# Main.net
KiCad netlist of a schematic drawn in EAGLE
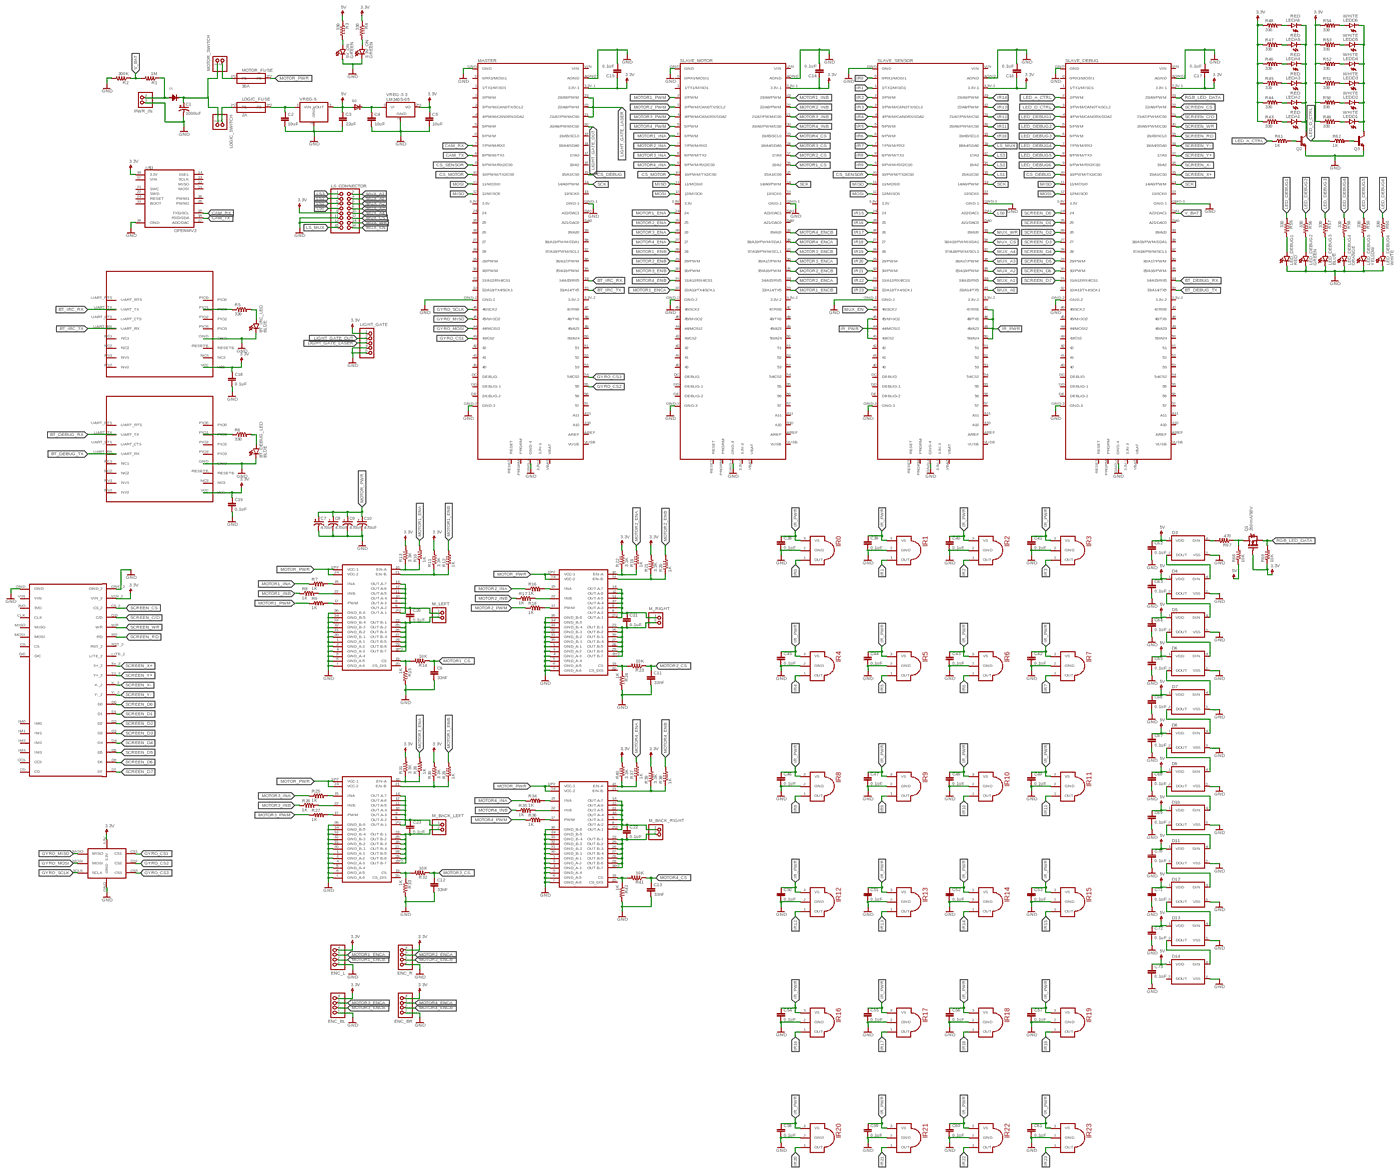
[diagram p0: schematic, sheet 1, overview]
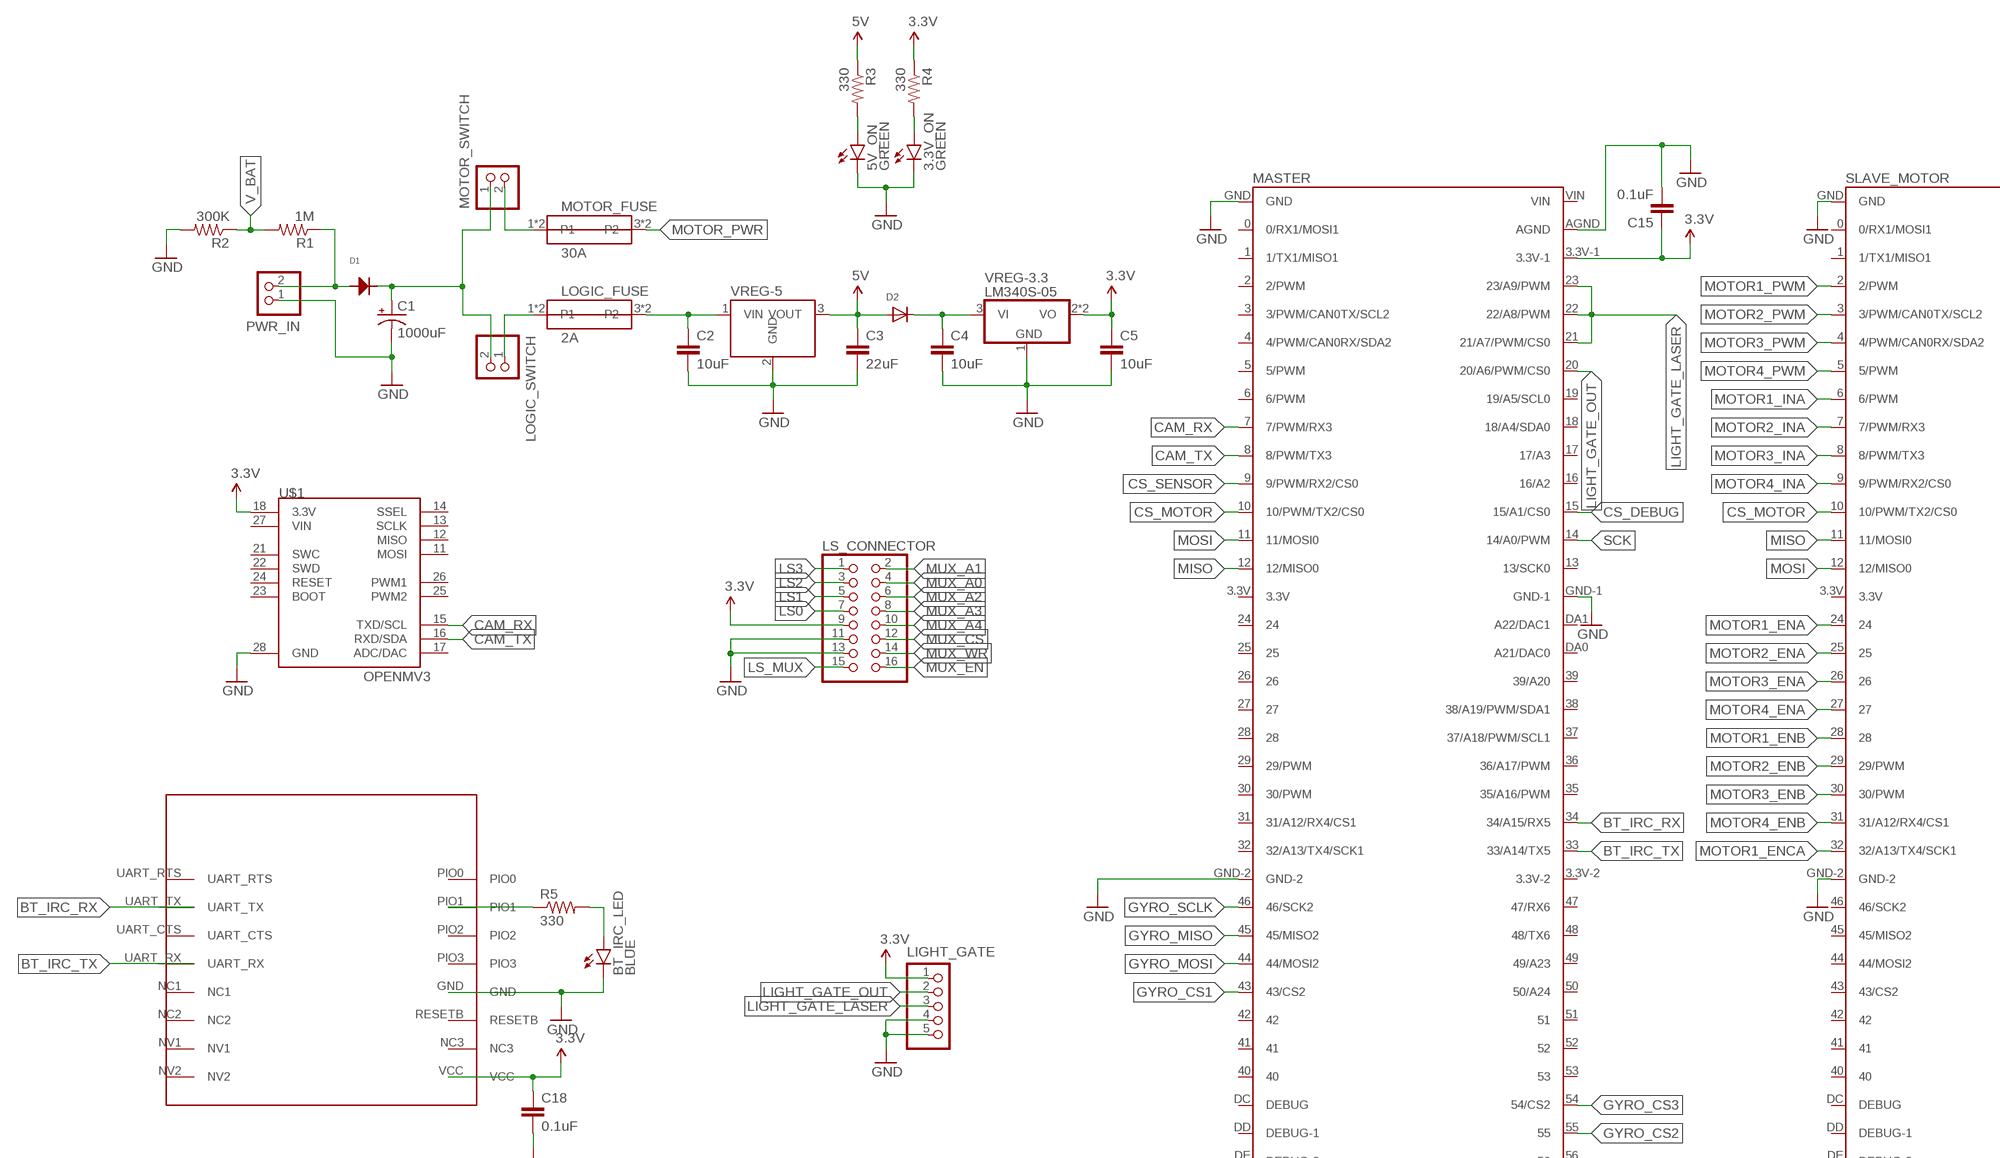
[diagram p1: schematic, sheet 1, part 1 of 4]
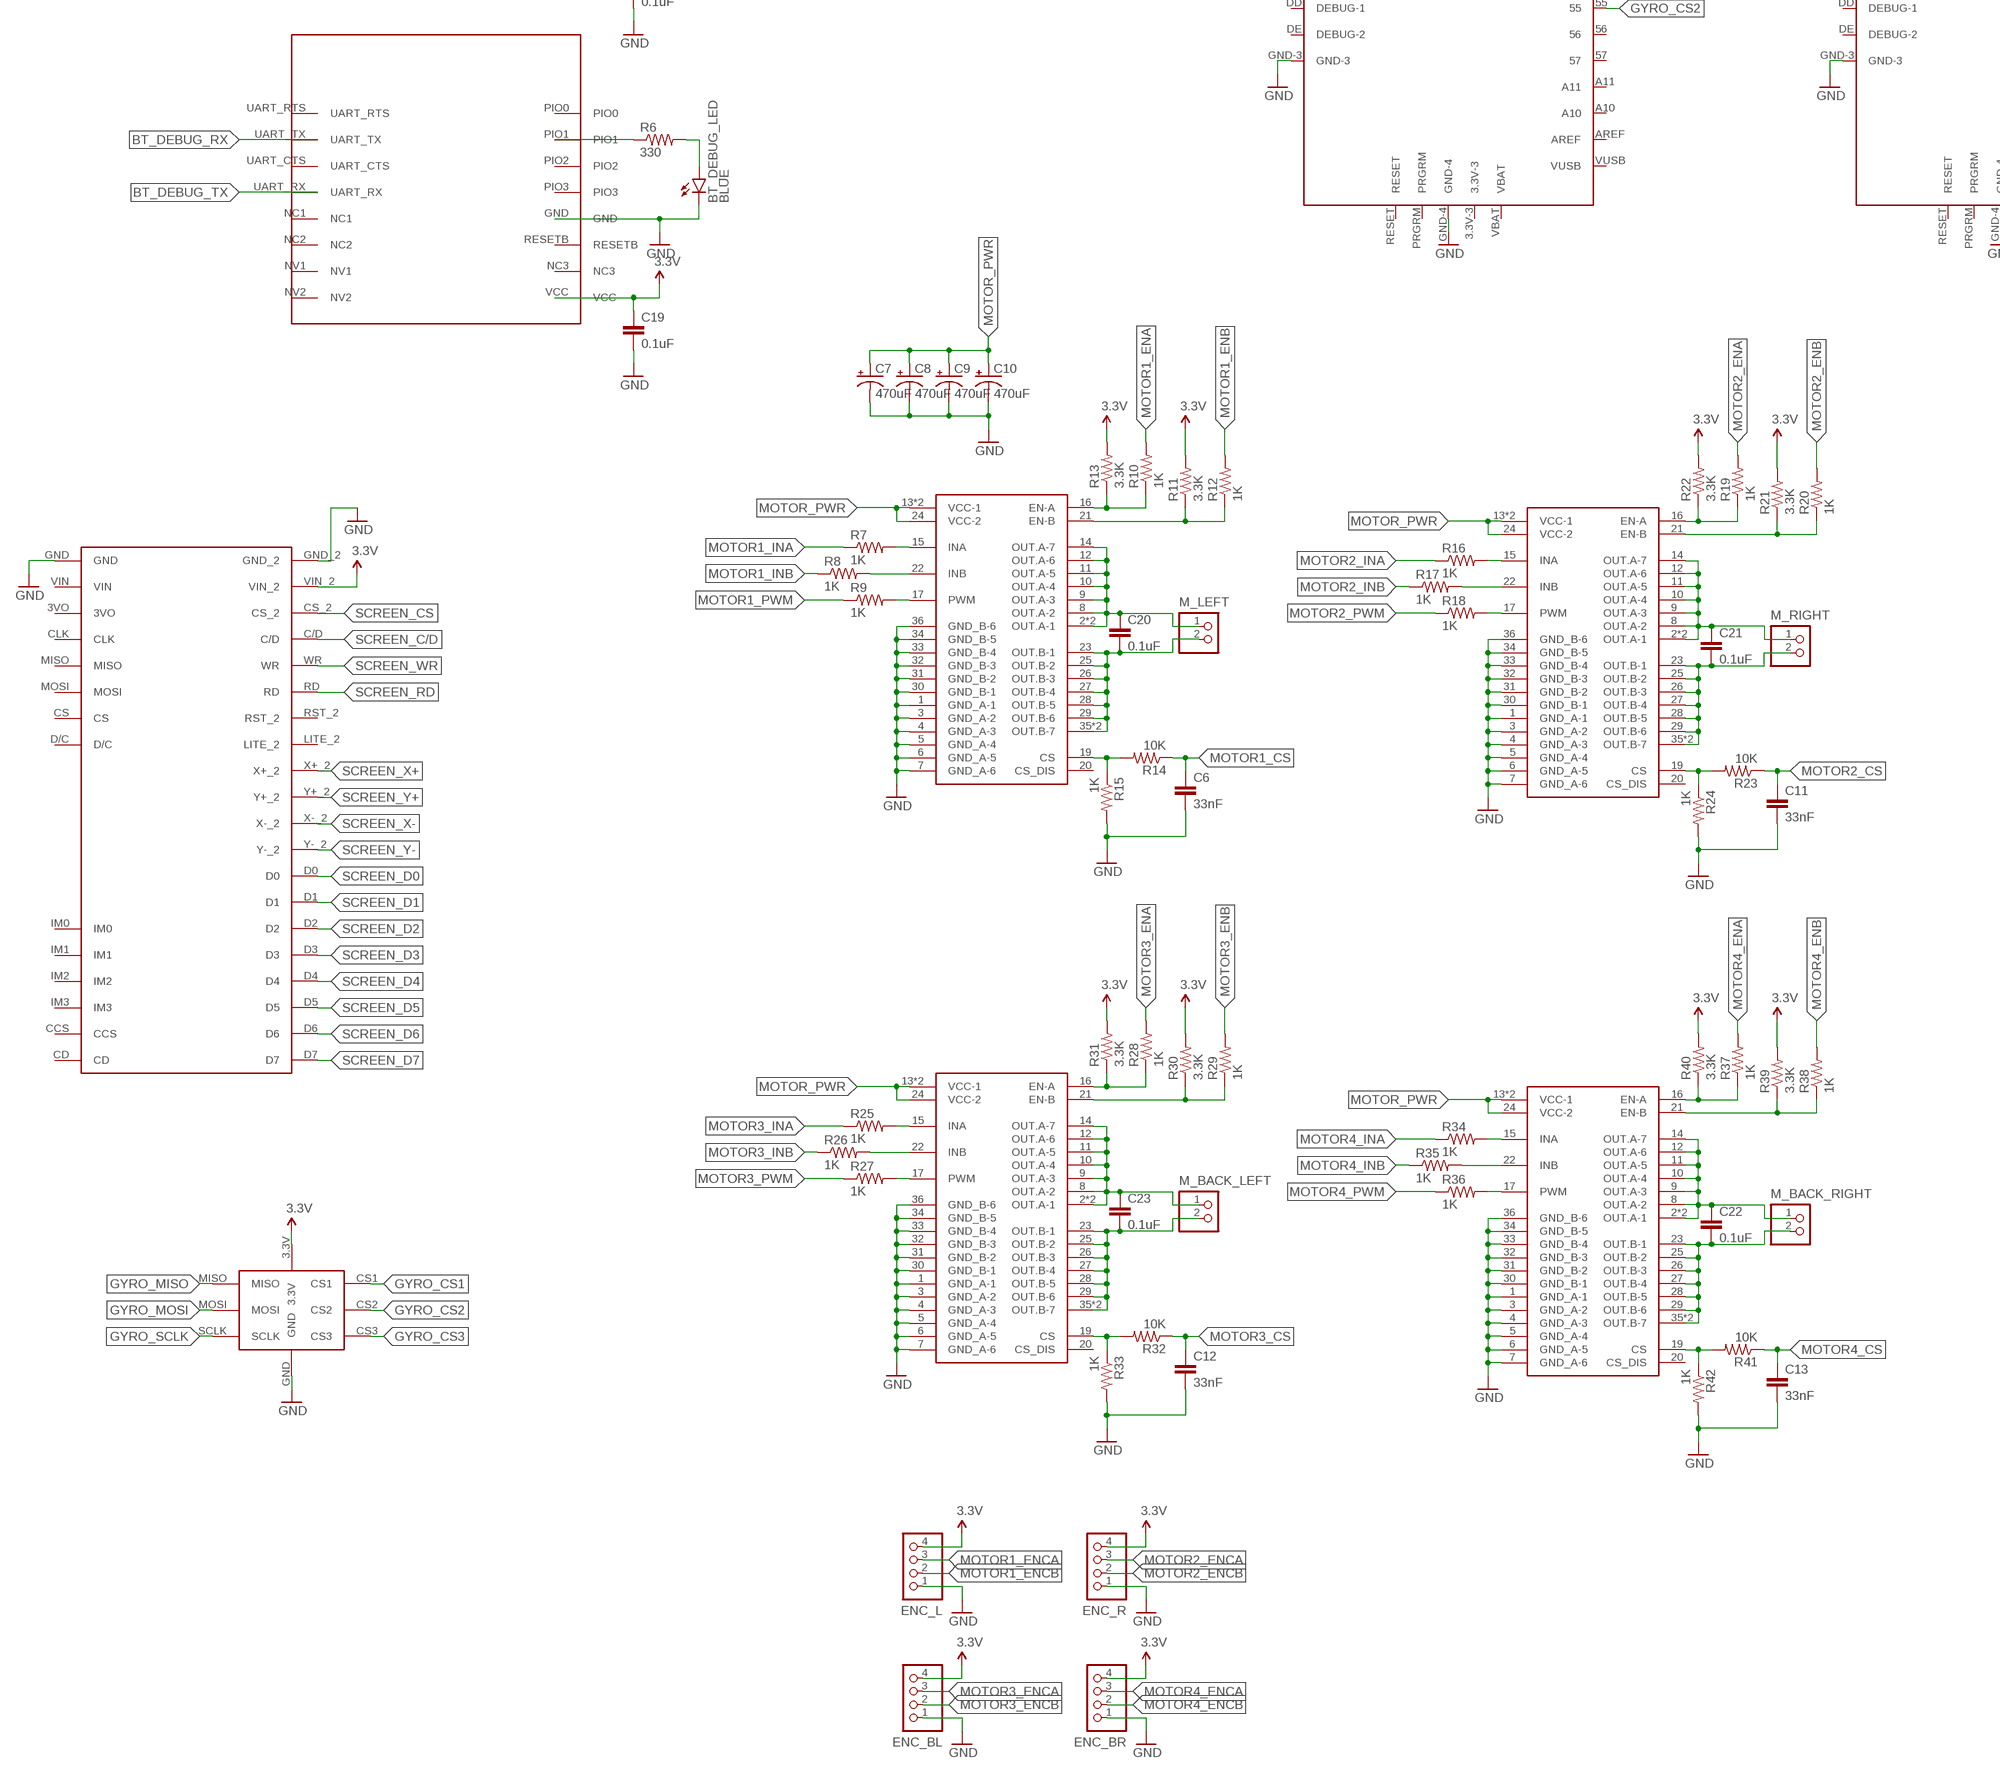
[diagram p2: schematic, sheet 1, part 2 of 4]
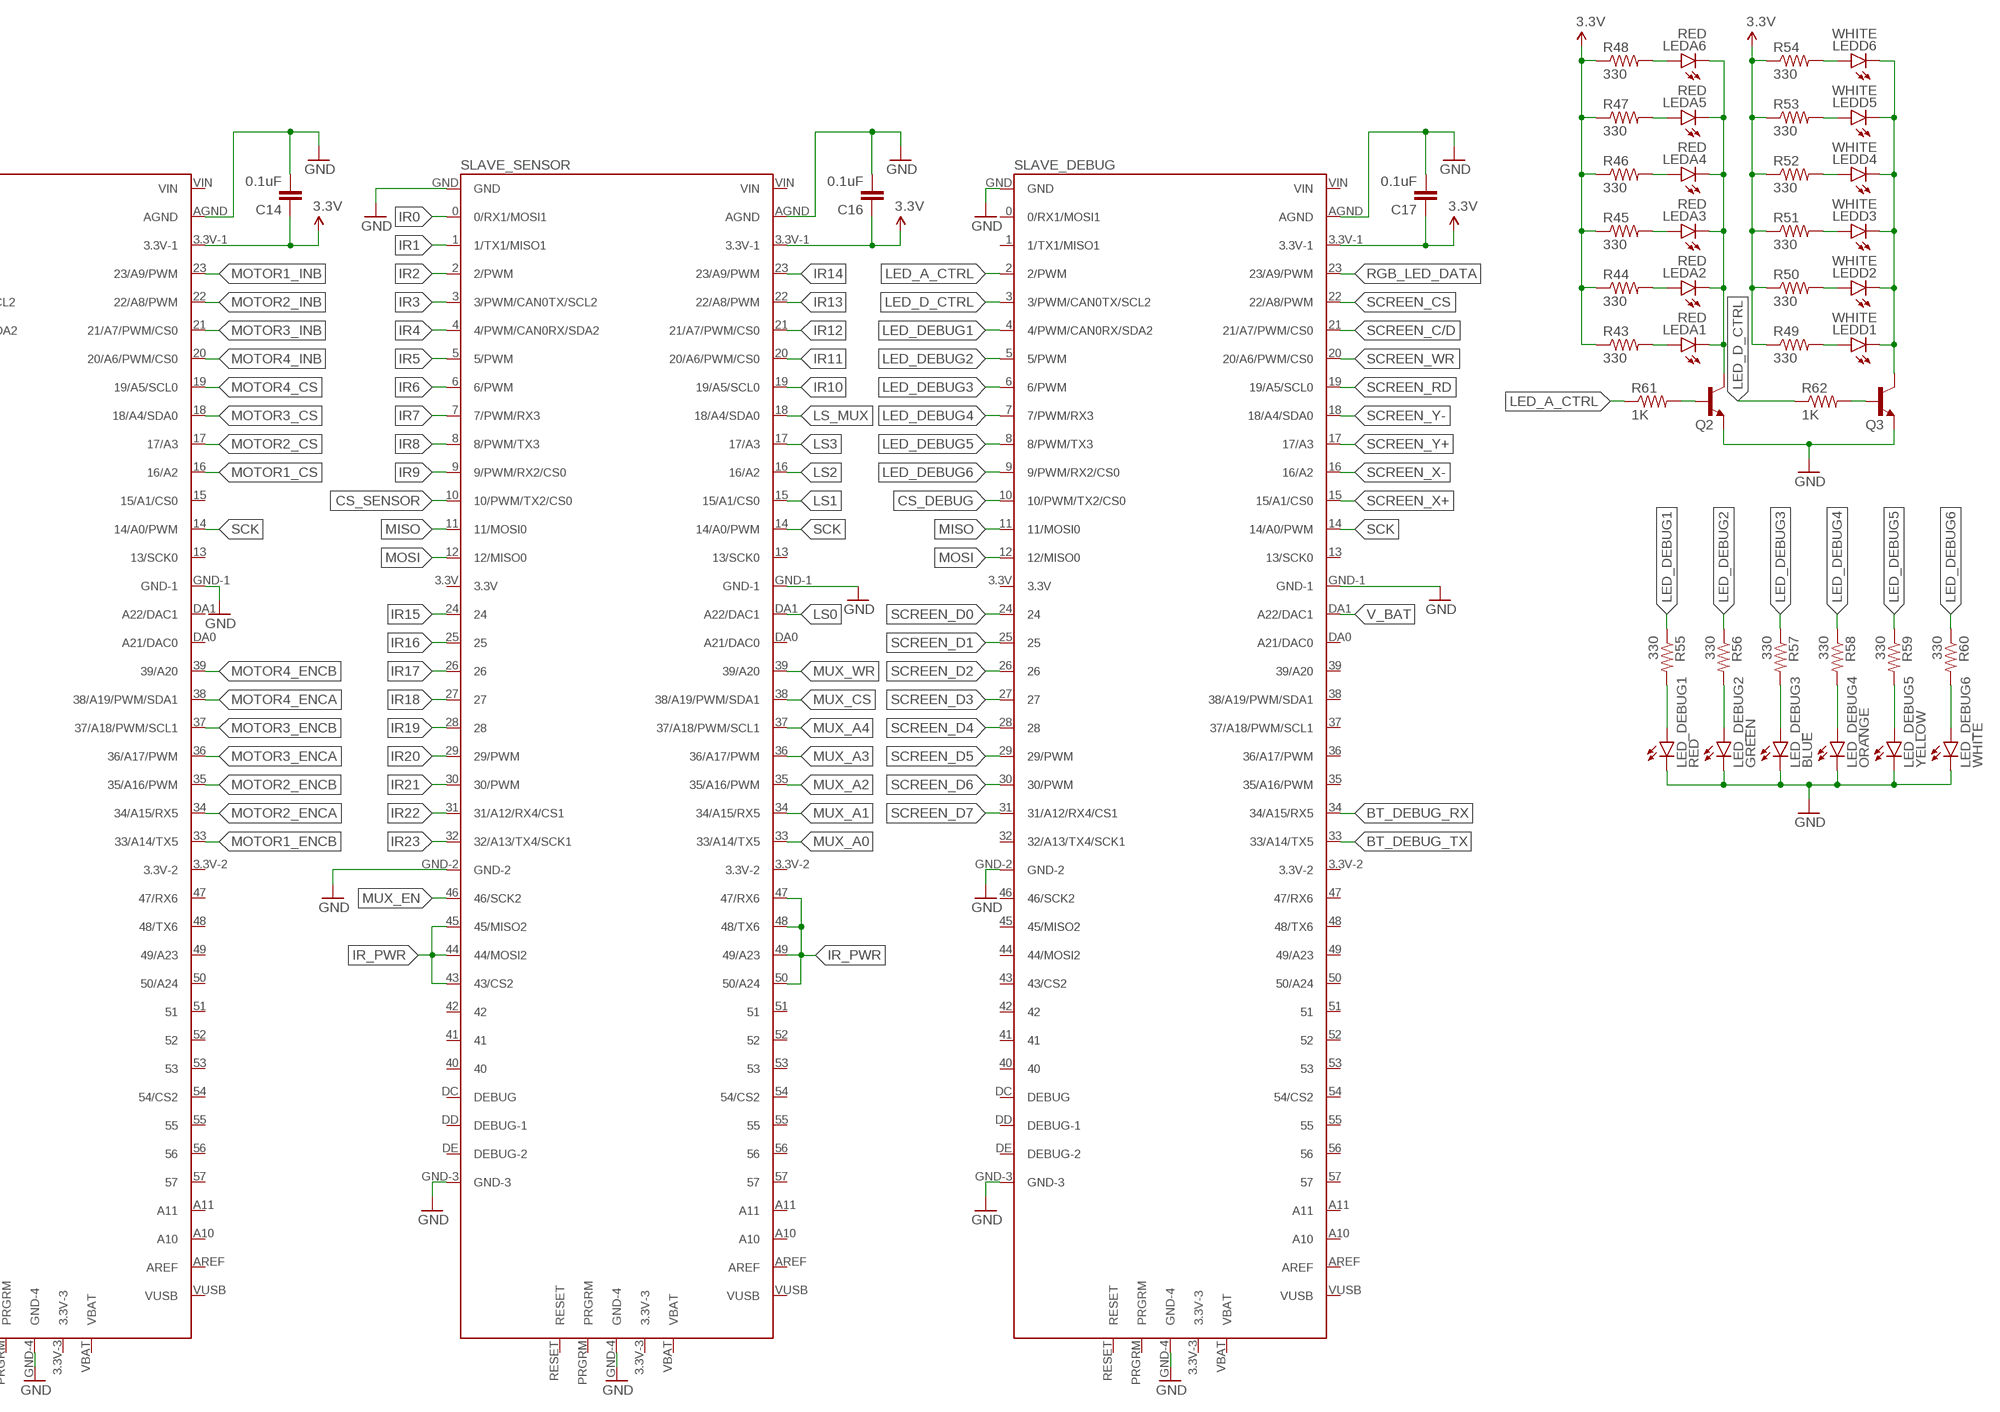
[diagram p3: schematic, sheet 1, part 3 of 4]
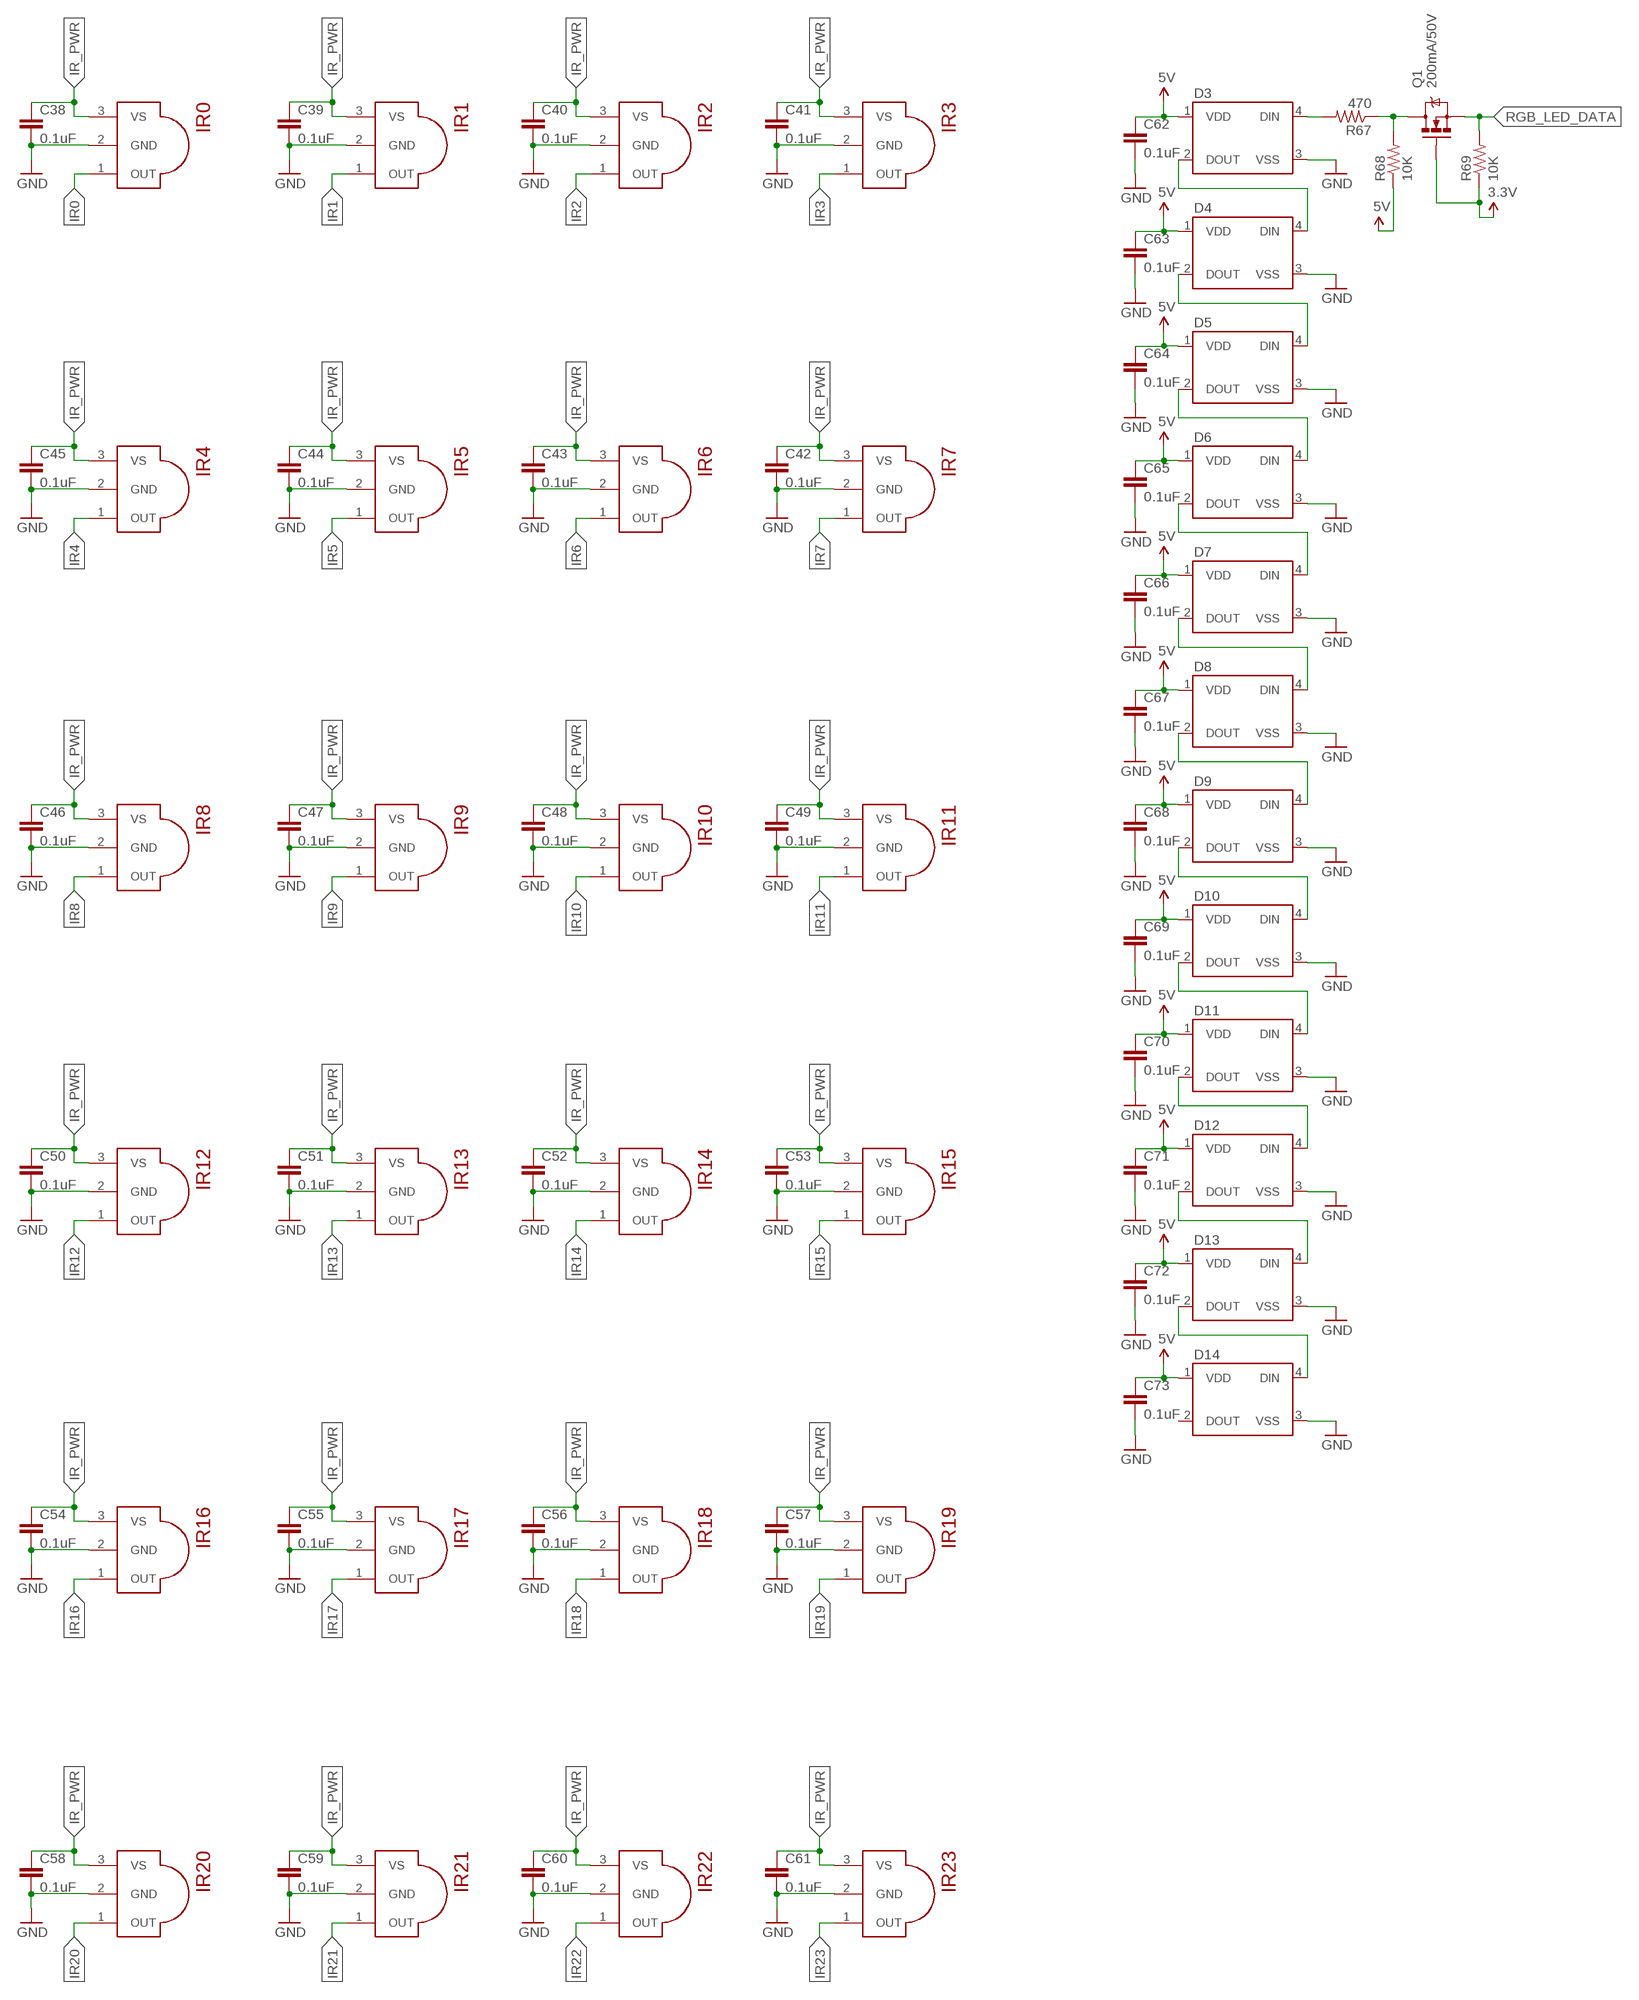
[diagram p4: schematic, sheet 1, part 4 of 4]

(export (version "E")
  (design (tool "Eeschema 10.0.6"))
  (components
    (comp (ref "3.3V_ON")
      (value "GREEN")
      (footprint "eagle-import:LED-0603")
      (libsource (lib "eagle-import") (part "LED0603"))
    )
    (comp (ref "5V_ON")
      (value "GREEN")
      (footprint "eagle-import:LED-0603")
      (libsource (lib "eagle-import") (part "LED0603"))
    )
    (comp (ref "BT_DEBUG")
      (value "HM-11")
      (footprint "eagle-import:HM-11")
      (libsource (lib "eagle-import") (part "HM-11"))
    )
    (comp (ref "BT_DEBUG_LED")
      (value "BLUE")
      (footprint "eagle-import:LED-0603")
      (libsource (lib "eagle-import") (part "LED0603"))
    )
    (comp (ref "BT_IRC")
      (value "HM-11")
      (footprint "eagle-import:HM-11")
      (libsource (lib "eagle-import") (part "HM-11"))
    )
    (comp (ref "BT_IRC_LED")
      (value "BLUE")
      (footprint "eagle-import:LED-0603")
      (libsource (lib "eagle-import") (part "LED0603"))
    )
    (comp (ref "C1")
      (value "1000uF")
      (footprint "eagle-import:CPOL-RADIAL-1000UF-25V")
      (libsource (lib "eagle-import") (part "1000UF-25V(PTH)"))
    )
    (comp (ref "C2")
      (value "10uF")
      (footprint "eagle-import:0805")
      (libsource (lib "eagle-import") (part "CAP0805"))
    )
    (comp (ref "C3")
      (value "22uF")
      (footprint "eagle-import:1206")
      (libsource (lib "eagle-import") (part "CAP1206"))
    )
    (comp (ref "C4")
      (value "10uF")
      (footprint "eagle-import:0805")
      (libsource (lib "eagle-import") (part "CAP0805"))
    )
    (comp (ref "C5")
      (value "10uF")
      (footprint "eagle-import:0805")
      (libsource (lib "eagle-import") (part "CAP0805"))
    )
    (comp (ref "C6")
      (value "33nF")
      (footprint "eagle-import:0603-CAP")
      (libsource (lib "eagle-import") (part "CAP0603-CAP"))
    )
    (comp (ref "C7")
      (value "470uF")
      (footprint "eagle-import:E3,5-8")
      (libsource (lib "eagle-import") (part "CPOL-USE3.5-8"))
    )
    (comp (ref "C8")
      (value "470uF")
      (footprint "eagle-import:E3,5-8")
      (libsource (lib "eagle-import") (part "CPOL-USE3.5-8"))
    )
    (comp (ref "C9")
      (value "470uF")
      (footprint "eagle-import:E3,5-8")
      (libsource (lib "eagle-import") (part "CPOL-USE3.5-8"))
    )
    (comp (ref "C10")
      (value "470uF")
      (footprint "eagle-import:E3,5-8")
      (libsource (lib "eagle-import") (part "CPOL-USE3.5-8"))
    )
    (comp (ref "C11")
      (value "33nF")
      (footprint "eagle-import:0603-CAP")
      (libsource (lib "eagle-import") (part "CAP0603-CAP"))
    )
    (comp (ref "C12")
      (value "33nF")
      (footprint "eagle-import:0603-CAP")
      (libsource (lib "eagle-import") (part "CAP0603-CAP"))
    )
    (comp (ref "C13")
      (value "33nF")
      (footprint "eagle-import:0603-CAP")
      (libsource (lib "eagle-import") (part "CAP0603-CAP"))
    )
    (comp (ref "C14")
      (value "0.1uF")
      (footprint "eagle-import:0603-CAP")
      (libsource (lib "eagle-import") (part "CAP0603-CAP"))
    )
    (comp (ref "C15")
      (value "0.1uF")
      (footprint "eagle-import:0603-CAP")
      (libsource (lib "eagle-import") (part "CAP0603-CAP"))
    )
    (comp (ref "C16")
      (value "0.1uF")
      (footprint "eagle-import:0603-CAP")
      (libsource (lib "eagle-import") (part "CAP0603-CAP"))
    )
    (comp (ref "C17")
      (value "0.1uF")
      (footprint "eagle-import:0603-CAP")
      (libsource (lib "eagle-import") (part "CAP0603-CAP"))
    )
    (comp (ref "C18")
      (value "0.1uF")
      (footprint "eagle-import:0603-CAP")
      (libsource (lib "eagle-import") (part "CAP0603-CAP"))
    )
    (comp (ref "C19")
      (value "0.1uF")
      (footprint "eagle-import:0603-CAP")
      (libsource (lib "eagle-import") (part "CAP0603-CAP"))
    )
    (comp (ref "C20")
      (value "0.1uF")
      (footprint "eagle-import:0603-CAP")
      (libsource (lib "eagle-import") (part "CAP0603-CAP"))
    )
    (comp (ref "C21")
      (value "0.1uF")
      (footprint "eagle-import:0603-CAP")
      (libsource (lib "eagle-import") (part "CAP0603-CAP"))
    )
    (comp (ref "C22")
      (value "0.1uF")
      (footprint "eagle-import:0603-CAP")
      (libsource (lib "eagle-import") (part "CAP0603-CAP"))
    )
    (comp (ref "C23")
      (value "0.1uF")
      (footprint "eagle-import:0603-CAP")
      (libsource (lib "eagle-import") (part "CAP0603-CAP"))
    )
    (comp (ref "C38")
      (value "0.1uF")
      (footprint "eagle-import:0603-CAP")
      (libsource (lib "eagle-import") (part "CAP0603-CAP"))
    )
    (comp (ref "C39")
      (value "0.1uF")
      (footprint "eagle-import:0603-CAP")
      (libsource (lib "eagle-import") (part "CAP0603-CAP"))
    )
    (comp (ref "C40")
      (value "0.1uF")
      (footprint "eagle-import:0603-CAP")
      (libsource (lib "eagle-import") (part "CAP0603-CAP"))
    )
    (comp (ref "C41")
      (value "0.1uF")
      (footprint "eagle-import:0603-CAP")
      (libsource (lib "eagle-import") (part "CAP0603-CAP"))
    )
    (comp (ref "C42")
      (value "0.1uF")
      (footprint "eagle-import:0603-CAP")
      (libsource (lib "eagle-import") (part "CAP0603-CAP"))
    )
    (comp (ref "C43")
      (value "0.1uF")
      (footprint "eagle-import:0603-CAP")
      (libsource (lib "eagle-import") (part "CAP0603-CAP"))
    )
    (comp (ref "C44")
      (value "0.1uF")
      (footprint "eagle-import:0603-CAP")
      (libsource (lib "eagle-import") (part "CAP0603-CAP"))
    )
    (comp (ref "C45")
      (value "0.1uF")
      (footprint "eagle-import:0603-CAP")
      (libsource (lib "eagle-import") (part "CAP0603-CAP"))
    )
    (comp (ref "C46")
      (value "0.1uF")
      (footprint "eagle-import:0603-CAP")
      (libsource (lib "eagle-import") (part "CAP0603-CAP"))
    )
    (comp (ref "C47")
      (value "0.1uF")
      (footprint "eagle-import:0603-CAP")
      (libsource (lib "eagle-import") (part "CAP0603-CAP"))
    )
    (comp (ref "C48")
      (value "0.1uF")
      (footprint "eagle-import:0603-CAP")
      (libsource (lib "eagle-import") (part "CAP0603-CAP"))
    )
    (comp (ref "C49")
      (value "0.1uF")
      (footprint "eagle-import:0603-CAP")
      (libsource (lib "eagle-import") (part "CAP0603-CAP"))
    )
    (comp (ref "C50")
      (value "0.1uF")
      (footprint "eagle-import:0603-CAP")
      (libsource (lib "eagle-import") (part "CAP0603-CAP"))
    )
    (comp (ref "C51")
      (value "0.1uF")
      (footprint "eagle-import:0603-CAP")
      (libsource (lib "eagle-import") (part "CAP0603-CAP"))
    )
    (comp (ref "C52")
      (value "0.1uF")
      (footprint "eagle-import:0603-CAP")
      (libsource (lib "eagle-import") (part "CAP0603-CAP"))
    )
    (comp (ref "C53")
      (value "0.1uF")
      (footprint "eagle-import:0603-CAP")
      (libsource (lib "eagle-import") (part "CAP0603-CAP"))
    )
    (comp (ref "C54")
      (value "0.1uF")
      (footprint "eagle-import:0603-CAP")
      (libsource (lib "eagle-import") (part "CAP0603-CAP"))
    )
    (comp (ref "C55")
      (value "0.1uF")
      (footprint "eagle-import:0603-CAP")
      (libsource (lib "eagle-import") (part "CAP0603-CAP"))
    )
    (comp (ref "C56")
      (value "0.1uF")
      (footprint "eagle-import:0603-CAP")
      (libsource (lib "eagle-import") (part "CAP0603-CAP"))
    )
    (comp (ref "C57")
      (value "0.1uF")
      (footprint "eagle-import:0603-CAP")
      (libsource (lib "eagle-import") (part "CAP0603-CAP"))
    )
    (comp (ref "C58")
      (value "0.1uF")
      (footprint "eagle-import:0603-CAP")
      (libsource (lib "eagle-import") (part "CAP0603-CAP"))
    )
    (comp (ref "C59")
      (value "0.1uF")
      (footprint "eagle-import:0603-CAP")
      (libsource (lib "eagle-import") (part "CAP0603-CAP"))
    )
    (comp (ref "C60")
      (value "0.1uF")
      (footprint "eagle-import:0603-CAP")
      (libsource (lib "eagle-import") (part "CAP0603-CAP"))
    )
    (comp (ref "C61")
      (value "0.1uF")
      (footprint "eagle-import:0603-CAP")
      (libsource (lib "eagle-import") (part "CAP0603-CAP"))
    )
    (comp (ref "C62")
      (value "0.1uF")
      (footprint "eagle-import:0603-CAP")
      (libsource (lib "eagle-import") (part "CAP0603-CAP"))
    )
    (comp (ref "C63")
      (value "0.1uF")
      (footprint "eagle-import:0603-CAP")
      (libsource (lib "eagle-import") (part "CAP0603-CAP"))
    )
    (comp (ref "C64")
      (value "0.1uF")
      (footprint "eagle-import:0603-CAP")
      (libsource (lib "eagle-import") (part "CAP0603-CAP"))
    )
    (comp (ref "C65")
      (value "0.1uF")
      (footprint "eagle-import:0603-CAP")
      (libsource (lib "eagle-import") (part "CAP0603-CAP"))
    )
    (comp (ref "C66")
      (value "0.1uF")
      (footprint "eagle-import:0603-CAP")
      (libsource (lib "eagle-import") (part "CAP0603-CAP"))
    )
    (comp (ref "C67")
      (value "0.1uF")
      (footprint "eagle-import:0603-CAP")
      (libsource (lib "eagle-import") (part "CAP0603-CAP"))
    )
    (comp (ref "C68")
      (value "0.1uF")
      (footprint "eagle-import:0603-CAP")
      (libsource (lib "eagle-import") (part "CAP0603-CAP"))
    )
    (comp (ref "C69")
      (value "0.1uF")
      (footprint "eagle-import:0603-CAP")
      (libsource (lib "eagle-import") (part "CAP0603-CAP"))
    )
    (comp (ref "C70")
      (value "0.1uF")
      (footprint "eagle-import:0603-CAP")
      (libsource (lib "eagle-import") (part "CAP0603-CAP"))
    )
    (comp (ref "C71")
      (value "0.1uF")
      (footprint "eagle-import:0603-CAP")
      (libsource (lib "eagle-import") (part "CAP0603-CAP"))
    )
    (comp (ref "C72")
      (value "0.1uF")
      (footprint "eagle-import:0603-CAP")
      (libsource (lib "eagle-import") (part "CAP0603-CAP"))
    )
    (comp (ref "C73")
      (value "0.1uF")
      (footprint "eagle-import:0603-CAP")
      (libsource (lib "eagle-import") (part "CAP0603-CAP"))
    )
    (comp (ref "D1")
      (value "DIODE_D2PAK(TO-263AB)")
      (footprint "eagle-import:D2PAK(TO-263AB)")
      (libsource (lib "eagle-import") (part "DIODE_D2PAK(TO-263AB)"))
    )
    (comp (ref "D2")
      (value "DIODE_SOD-123FL")
      (footprint "eagle-import:SOD-123FL")
      (libsource (lib "eagle-import") (part "DIODE_SOD-123FL"))
    )
    (comp (ref "D3")
      (value "WS2812B")
      (footprint "eagle-import:WS2812B")
      (libsource (lib "eagle-import") (part "WS2812B"))
    )
    (comp (ref "D4")
      (value "WS2812B")
      (footprint "eagle-import:WS2812B")
      (libsource (lib "eagle-import") (part "WS2812B"))
    )
    (comp (ref "D5")
      (value "WS2812B")
      (footprint "eagle-import:WS2812B")
      (libsource (lib "eagle-import") (part "WS2812B"))
    )
    (comp (ref "D6")
      (value "WS2812B")
      (footprint "eagle-import:WS2812B")
      (libsource (lib "eagle-import") (part "WS2812B"))
    )
    (comp (ref "D7")
      (value "WS2812B")
      (footprint "eagle-import:WS2812B")
      (libsource (lib "eagle-import") (part "WS2812B"))
    )
    (comp (ref "D8")
      (value "WS2812B")
      (footprint "eagle-import:WS2812B")
      (libsource (lib "eagle-import") (part "WS2812B"))
    )
    (comp (ref "D9")
      (value "WS2812B")
      (footprint "eagle-import:WS2812B")
      (libsource (lib "eagle-import") (part "WS2812B"))
    )
    (comp (ref "D10")
      (value "WS2812B")
      (footprint "eagle-import:WS2812B")
      (libsource (lib "eagle-import") (part "WS2812B"))
    )
    (comp (ref "D11")
      (value "WS2812B")
      (footprint "eagle-import:WS2812B")
      (libsource (lib "eagle-import") (part "WS2812B"))
    )
    (comp (ref "D12")
      (value "WS2812B")
      (footprint "eagle-import:WS2812B")
      (libsource (lib "eagle-import") (part "WS2812B"))
    )
    (comp (ref "D13")
      (value "WS2812B")
      (footprint "eagle-import:WS2812B")
      (libsource (lib "eagle-import") (part "WS2812B"))
    )
    (comp (ref "D14")
      (value "WS2812B")
      (footprint "eagle-import:WS2812B")
      (libsource (lib "eagle-import") (part "WS2812B"))
    )
    (comp (ref "ENC_BL")
      (value "B4B-PH-K-S")
      (footprint "eagle-import:B4B-PH-K-S")
      (libsource (lib "eagle-import") (part "B4B-PH-K-S"))
    )
    (comp (ref "ENC_BR")
      (value "B4B-PH-K-S")
      (footprint "eagle-import:B4B-PH-K-S")
      (libsource (lib "eagle-import") (part "B4B-PH-K-S"))
    )
    (comp (ref "ENC_L")
      (value "B4B-PH-K-S")
      (footprint "eagle-import:B4B-PH-K-S")
      (libsource (lib "eagle-import") (part "B4B-PH-K-S"))
    )
    (comp (ref "ENC_R")
      (value "B4B-PH-K-S")
      (footprint "eagle-import:B4B-PH-K-S")
      (libsource (lib "eagle-import") (part "B4B-PH-K-S"))
    )
    (comp (ref "IR0")
      (value "TSSP58038")
      (footprint "eagle-import:TSSP58038")
      (libsource (lib "eagle-import") (part "TSSP58038"))
    )
    (comp (ref "IR1")
      (value "TSSP58038")
      (footprint "eagle-import:TSSP58038")
      (libsource (lib "eagle-import") (part "TSSP58038"))
    )
    (comp (ref "IR2")
      (value "TSSP58038")
      (footprint "eagle-import:TSSP58038")
      (libsource (lib "eagle-import") (part "TSSP58038"))
    )
    (comp (ref "IR3")
      (value "TSSP58038")
      (footprint "eagle-import:TSSP58038")
      (libsource (lib "eagle-import") (part "TSSP58038"))
    )
    (comp (ref "IR4")
      (value "TSSP58038")
      (footprint "eagle-import:TSSP58038")
      (libsource (lib "eagle-import") (part "TSSP58038"))
    )
    (comp (ref "IR5")
      (value "TSSP58038")
      (footprint "eagle-import:TSSP58038")
      (libsource (lib "eagle-import") (part "TSSP58038"))
    )
    (comp (ref "IR6")
      (value "TSSP58038")
      (footprint "eagle-import:TSSP58038")
      (libsource (lib "eagle-import") (part "TSSP58038"))
    )
    (comp (ref "IR7")
      (value "TSSP58038")
      (footprint "eagle-import:TSSP58038")
      (libsource (lib "eagle-import") (part "TSSP58038"))
    )
    (comp (ref "IR8")
      (value "TSSP58038")
      (footprint "eagle-import:TSSP58038")
      (libsource (lib "eagle-import") (part "TSSP58038"))
    )
    (comp (ref "IR9")
      (value "TSSP58038")
      (footprint "eagle-import:TSSP58038")
      (libsource (lib "eagle-import") (part "TSSP58038"))
    )
    (comp (ref "IR10")
      (value "TSSP58038")
      (footprint "eagle-import:TSSP58038")
      (libsource (lib "eagle-import") (part "TSSP58038"))
    )
    (comp (ref "IR11")
      (value "TSSP58038")
      (footprint "eagle-import:TSSP58038")
      (libsource (lib "eagle-import") (part "TSSP58038"))
    )
    (comp (ref "IR12")
      (value "TSSP58038")
      (footprint "eagle-import:TSSP58038")
      (libsource (lib "eagle-import") (part "TSSP58038"))
    )
    (comp (ref "IR13")
      (value "TSSP58038")
      (footprint "eagle-import:TSSP58038")
      (libsource (lib "eagle-import") (part "TSSP58038"))
    )
    (comp (ref "IR14")
      (value "TSSP58038")
      (footprint "eagle-import:TSSP58038")
      (libsource (lib "eagle-import") (part "TSSP58038"))
    )
    (comp (ref "IR15")
      (value "TSSP58038")
      (footprint "eagle-import:TSSP58038")
      (libsource (lib "eagle-import") (part "TSSP58038"))
    )
    (comp (ref "IR16")
      (value "TSSP58038")
      (footprint "eagle-import:TSSP58038")
      (libsource (lib "eagle-import") (part "TSSP58038"))
    )
    (comp (ref "IR17")
      (value "TSSP58038")
      (footprint "eagle-import:TSSP58038")
      (libsource (lib "eagle-import") (part "TSSP58038"))
    )
    (comp (ref "IR18")
      (value "TSSP58038")
      (footprint "eagle-import:TSSP58038")
      (libsource (lib "eagle-import") (part "TSSP58038"))
    )
    (comp (ref "IR19")
      (value "TSSP58038")
      (footprint "eagle-import:TSSP58038")
      (libsource (lib "eagle-import") (part "TSSP58038"))
    )
    (comp (ref "IR20")
      (value "TSSP58038")
      (footprint "eagle-import:TSSP58038")
      (libsource (lib "eagle-import") (part "TSSP58038"))
    )
    (comp (ref "IR21")
      (value "TSSP58038")
      (footprint "eagle-import:TSSP58038")
      (libsource (lib "eagle-import") (part "TSSP58038"))
    )
    (comp (ref "IR22")
      (value "TSSP58038")
      (footprint "eagle-import:TSSP58038")
      (libsource (lib "eagle-import") (part "TSSP58038"))
    )
    (comp (ref "IR23")
      (value "TSSP58038")
      (footprint "eagle-import:TSSP58038")
      (libsource (lib "eagle-import") (part "TSSP58038"))
    )
    (comp (ref "LEDA1")
      (value "RED")
      (footprint "eagle-import:LED-0603")
      (libsource (lib "eagle-import") (part "LED0603"))
    )
    (comp (ref "LEDA2")
      (value "RED")
      (footprint "eagle-import:LED-0603")
      (libsource (lib "eagle-import") (part "LED0603"))
    )
    (comp (ref "LEDA3")
      (value "RED")
      (footprint "eagle-import:LED-0603")
      (libsource (lib "eagle-import") (part "LED0603"))
    )
    (comp (ref "LEDA4")
      (value "RED")
      (footprint "eagle-import:LED-0603")
      (libsource (lib "eagle-import") (part "LED0603"))
    )
    (comp (ref "LEDA5")
      (value "RED")
      (footprint "eagle-import:LED-0603")
      (libsource (lib "eagle-import") (part "LED0603"))
    )
    (comp (ref "LEDA6")
      (value "RED")
      (footprint "eagle-import:LED-0603")
      (libsource (lib "eagle-import") (part "LED0603"))
    )
    (comp (ref "LEDD1")
      (value "WHITE")
      (footprint "eagle-import:LED-0603")
      (libsource (lib "eagle-import") (part "LED0603"))
    )
    (comp (ref "LEDD2")
      (value "WHITE")
      (footprint "eagle-import:LED-0603")
      (libsource (lib "eagle-import") (part "LED0603"))
    )
    (comp (ref "LEDD3")
      (value "WHITE")
      (footprint "eagle-import:LED-0603")
      (libsource (lib "eagle-import") (part "LED0603"))
    )
    (comp (ref "LEDD4")
      (value "WHITE")
      (footprint "eagle-import:LED-0603")
      (libsource (lib "eagle-import") (part "LED0603"))
    )
    (comp (ref "LEDD5")
      (value "WHITE")
      (footprint "eagle-import:LED-0603")
      (libsource (lib "eagle-import") (part "LED0603"))
    )
    (comp (ref "LEDD6")
      (value "WHITE")
      (footprint "eagle-import:LED-0603")
      (libsource (lib "eagle-import") (part "LED0603"))
    )
    (comp (ref "LED_DEBUG1")
      (value "RED")
      (footprint "eagle-import:LED-0603")
      (libsource (lib "eagle-import") (part "LED0603"))
    )
    (comp (ref "LED_DEBUG2")
      (value "GREEN")
      (footprint "eagle-import:LED-0603")
      (libsource (lib "eagle-import") (part "LED0603"))
    )
    (comp (ref "LED_DEBUG3")
      (value "BLUE")
      (footprint "eagle-import:LED-0603")
      (libsource (lib "eagle-import") (part "LED0603"))
    )
    (comp (ref "LED_DEBUG4")
      (value "ORANGE")
      (footprint "eagle-import:LED-0603")
      (libsource (lib "eagle-import") (part "LED0603"))
    )
    (comp (ref "LED_DEBUG5")
      (value "YELLOW")
      (footprint "eagle-import:LED-0603")
      (libsource (lib "eagle-import") (part "LED0603"))
    )
    (comp (ref "LED_DEBUG6")
      (value "WHITE")
      (footprint "eagle-import:LED-0603")
      (libsource (lib "eagle-import") (part "LED0603"))
    )
    (comp (ref "LIGHT_GATE")
      (value "B5B-PH-K-S")
      (footprint "eagle-import:B5B-PH-K-S")
      (libsource (lib "eagle-import") (part "B5B-PH-K-S"))
    )
    (comp (ref "LOGIC_FUSE")
      (value "2A")
      (footprint "eagle-import:3568-FUSEHOLDER")
      (libsource (lib "eagle-import") (part "3568-FUSEHOLDER"))
    )
    (comp (ref "LOGIC_SWITCH")
      (value "B2P-VH")
      (footprint "eagle-import:B2P-VH")
      (libsource (lib "eagle-import") (part "B2P-VH"))
    )
    (comp (ref "LS_CONNECTOR")
      (value "PINHD-2X8SMT")
      (footprint "eagle-import:2X08_SMT")
      (libsource (lib "eagle-import") (part "PINHD-2X8SMT"))
    )
    (comp (ref "MASTER")
      (value "TEENSY-3.5")
      (footprint "eagle-import:TEENSY-3.5")
      (libsource (lib "eagle-import") (part "TEENSY-3.5"))
    )
    (comp (ref "MOTOR_FUSE")
      (value "30A")
      (footprint "eagle-import:3568-FUSEHOLDER")
      (libsource (lib "eagle-import") (part "3568-FUSEHOLDER"))
    )
    (comp (ref "MOTOR_SWITCH")
      (value "B2P-VH")
      (footprint "eagle-import:B2P-VH")
      (libsource (lib "eagle-import") (part "B2P-VH"))
    )
    (comp (ref "M_BACK_LEFT")
      (value "B2P-VH")
      (footprint "eagle-import:B2P-VH")
      (libsource (lib "eagle-import") (part "B2P-VH"))
    )
    (comp (ref "M_BACK_RIGHT")
      (value "B2P-VH")
      (footprint "eagle-import:B2P-VH")
      (libsource (lib "eagle-import") (part "B2P-VH"))
    )
    (comp (ref "M_LEFT")
      (value "B2P-VH")
      (footprint "eagle-import:B2P-VH")
      (libsource (lib "eagle-import") (part "B2P-VH"))
    )
    (comp (ref "M_RIGHT")
      (value "B2P-VH")
      (footprint "eagle-import:B2P-VH")
      (libsource (lib "eagle-import") (part "B2P-VH"))
    )
    (comp (ref "P1")
      (value "SOP50P1030X247-36N")
      (footprint "eagle-import:SOP50P1030X247-36N")
      (fields (field (name "MANUFACTURER") "STMicroelectronics"))
      (libsource (lib "eagle-import") (part "SOP50P1030X247-36N"))
    )
    (comp (ref "P2")
      (value "SOP50P1030X247-36N")
      (footprint "eagle-import:SOP50P1030X247-36N")
      (fields (field (name "MANUFACTURER") "STMicroelectronics"))
      (libsource (lib "eagle-import") (part "SOP50P1030X247-36N"))
    )
    (comp (ref "P3")
      (value "SOP50P1030X247-36N")
      (footprint "eagle-import:SOP50P1030X247-36N")
      (fields (field (name "MANUFACTURER") "STMicroelectronics"))
      (libsource (lib "eagle-import") (part "SOP50P1030X247-36N"))
    )
    (comp (ref "P4")
      (value "SOP50P1030X247-36N")
      (footprint "eagle-import:SOP50P1030X247-36N")
      (fields (field (name "MANUFACTURER") "STMicroelectronics"))
      (libsource (lib "eagle-import") (part "SOP50P1030X247-36N"))
    )
    (comp (ref "PWR_IN")
      (value "B2P-VH")
      (footprint "eagle-import:B2P-VH")
      (libsource (lib "eagle-import") (part "B2P-VH"))
    )
    (comp (ref "Q1")
      (value "200mA/50V")
      (footprint "eagle-import:SOT23-3")
      (libsource (lib "eagle-import") (part "MOSFET-NCHANNELBSS138"))
    )
    (comp (ref "Q2")
      (value "TRANSISTOR_NPNSOT23-3")
      (footprint "eagle-import:SOT23-3")
      (libsource (lib "eagle-import") (part "TRANSISTOR_NPNSOT23-3"))
    )
    (comp (ref "Q3")
      (value "TRANSISTOR_NPNSOT23-3")
      (footprint "eagle-import:SOT23-3")
      (libsource (lib "eagle-import") (part "TRANSISTOR_NPNSOT23-3"))
    )
    (comp (ref "R1")
      (value "1M")
      (footprint "eagle-import:0603-RES")
      (libsource (lib "eagle-import") (part "RESISTOR0603-RES"))
    )
    (comp (ref "R2")
      (value "300K")
      (footprint "eagle-import:0603-RES")
      (libsource (lib "eagle-import") (part "RESISTOR0603-RES"))
    )
    (comp (ref "R3")
      (value "330")
      (footprint "eagle-import:0603-RES")
      (libsource (lib "eagle-import") (part "RESISTOR0603-RES"))
    )
    (comp (ref "R4")
      (value "330")
      (footprint "eagle-import:0603-RES")
      (libsource (lib "eagle-import") (part "RESISTOR0603-RES"))
    )
    (comp (ref "R5")
      (value "330")
      (footprint "eagle-import:0603-RES")
      (libsource (lib "eagle-import") (part "RESISTOR0603-RES"))
    )
    (comp (ref "R6")
      (value "330")
      (footprint "eagle-import:0603-RES")
      (libsource (lib "eagle-import") (part "RESISTOR0603-RES"))
    )
    (comp (ref "R7")
      (value "1K")
      (footprint "eagle-import:0603-RES")
      (libsource (lib "eagle-import") (part "RESISTOR0603-RES"))
    )
    (comp (ref "R8")
      (value "1K")
      (footprint "eagle-import:0603-RES")
      (libsource (lib "eagle-import") (part "RESISTOR0603-RES"))
    )
    (comp (ref "R9")
      (value "1K")
      (footprint "eagle-import:0603-RES")
      (libsource (lib "eagle-import") (part "RESISTOR0603-RES"))
    )
    (comp (ref "R10")
      (value "1K")
      (footprint "eagle-import:0603-RES")
      (libsource (lib "eagle-import") (part "RESISTOR0603-RES"))
    )
    (comp (ref "R11")
      (value "3.3K")
      (footprint "eagle-import:0603-RES")
      (libsource (lib "eagle-import") (part "RESISTOR0603-RES"))
    )
    (comp (ref "R12")
      (value "1K")
      (footprint "eagle-import:0603-RES")
      (libsource (lib "eagle-import") (part "RESISTOR0603-RES"))
    )
    (comp (ref "R13")
      (value "3.3K")
      (footprint "eagle-import:0603-RES")
      (libsource (lib "eagle-import") (part "RESISTOR0603-RES"))
    )
    (comp (ref "R14")
      (value "10K")
      (footprint "eagle-import:0603-RES")
      (libsource (lib "eagle-import") (part "RESISTOR0603-RES"))
    )
    (comp (ref "R15")
      (value "1K")
      (footprint "eagle-import:0603-RES")
      (libsource (lib "eagle-import") (part "RESISTOR0603-RES"))
    )
    (comp (ref "R16")
      (value "1K")
      (footprint "eagle-import:0603-RES")
      (libsource (lib "eagle-import") (part "RESISTOR0603-RES"))
    )
    (comp (ref "R17")
      (value "1K")
      (footprint "eagle-import:0603-RES")
      (libsource (lib "eagle-import") (part "RESISTOR0603-RES"))
    )
    (comp (ref "R18")
      (value "1K")
      (footprint "eagle-import:0603-RES")
      (libsource (lib "eagle-import") (part "RESISTOR0603-RES"))
    )
    (comp (ref "R19")
      (value "1K")
      (footprint "eagle-import:0603-RES")
      (libsource (lib "eagle-import") (part "RESISTOR0603-RES"))
    )
    (comp (ref "R20")
      (value "1K")
      (footprint "eagle-import:0603-RES")
      (libsource (lib "eagle-import") (part "RESISTOR0603-RES"))
    )
    (comp (ref "R21")
      (value "3.3K")
      (footprint "eagle-import:0603-RES")
      (libsource (lib "eagle-import") (part "RESISTOR0603-RES"))
    )
    (comp (ref "R22")
      (value "3.3K")
      (footprint "eagle-import:0603-RES")
      (libsource (lib "eagle-import") (part "RESISTOR0603-RES"))
    )
    (comp (ref "R23")
      (value "10K")
      (footprint "eagle-import:0603-RES")
      (libsource (lib "eagle-import") (part "RESISTOR0603-RES"))
    )
    (comp (ref "R24")
      (value "1K")
      (footprint "eagle-import:0603-RES")
      (libsource (lib "eagle-import") (part "RESISTOR0603-RES"))
    )
    (comp (ref "R25")
      (value "1K")
      (footprint "eagle-import:0603-RES")
      (libsource (lib "eagle-import") (part "RESISTOR0603-RES"))
    )
    (comp (ref "R26")
      (value "1K")
      (footprint "eagle-import:0603-RES")
      (libsource (lib "eagle-import") (part "RESISTOR0603-RES"))
    )
    (comp (ref "R27")
      (value "1K")
      (footprint "eagle-import:0603-RES")
      (libsource (lib "eagle-import") (part "RESISTOR0603-RES"))
    )
    (comp (ref "R28")
      (value "1K")
      (footprint "eagle-import:0603-RES")
      (libsource (lib "eagle-import") (part "RESISTOR0603-RES"))
    )
    (comp (ref "R29")
      (value "1K")
      (footprint "eagle-import:0603-RES")
      (libsource (lib "eagle-import") (part "RESISTOR0603-RES"))
    )
    (comp (ref "R30")
      (value "3.3K")
      (footprint "eagle-import:0603-RES")
      (libsource (lib "eagle-import") (part "RESISTOR0603-RES"))
    )
    (comp (ref "R31")
      (value "3.3K")
      (footprint "eagle-import:0603-RES")
      (libsource (lib "eagle-import") (part "RESISTOR0603-RES"))
    )
    (comp (ref "R32")
      (value "10K")
      (footprint "eagle-import:0603-RES")
      (libsource (lib "eagle-import") (part "RESISTOR0603-RES"))
    )
    (comp (ref "R33")
      (value "1K")
      (footprint "eagle-import:0603-RES")
      (libsource (lib "eagle-import") (part "RESISTOR0603-RES"))
    )
    (comp (ref "R34")
      (value "1K")
      (footprint "eagle-import:0603-RES")
      (libsource (lib "eagle-import") (part "RESISTOR0603-RES"))
    )
    (comp (ref "R35")
      (value "1K")
      (footprint "eagle-import:0603-RES")
      (libsource (lib "eagle-import") (part "RESISTOR0603-RES"))
    )
    (comp (ref "R36")
      (value "1K")
      (footprint "eagle-import:0603-RES")
      (libsource (lib "eagle-import") (part "RESISTOR0603-RES"))
    )
    (comp (ref "R37")
      (value "1K")
      (footprint "eagle-import:0603-RES")
      (libsource (lib "eagle-import") (part "RESISTOR0603-RES"))
    )
    (comp (ref "R38")
      (value "1K")
      (footprint "eagle-import:0603-RES")
      (libsource (lib "eagle-import") (part "RESISTOR0603-RES"))
    )
    (comp (ref "R39")
      (value "3.3K")
      (footprint "eagle-import:0603-RES")
      (libsource (lib "eagle-import") (part "RESISTOR0603-RES"))
    )
    (comp (ref "R40")
      (value "3.3K")
      (footprint "eagle-import:0603-RES")
      (libsource (lib "eagle-import") (part "RESISTOR0603-RES"))
    )
    (comp (ref "R41")
      (value "10K")
      (footprint "eagle-import:0603-RES")
      (libsource (lib "eagle-import") (part "RESISTOR0603-RES"))
    )
    (comp (ref "R42")
      (value "1K")
      (footprint "eagle-import:0603-RES")
      (libsource (lib "eagle-import") (part "RESISTOR0603-RES"))
    )
    (comp (ref "R43")
      (value "330")
      (footprint "eagle-import:0603-RES")
      (libsource (lib "eagle-import") (part "RESISTOR0603-RES"))
    )
    (comp (ref "R44")
      (value "330")
      (footprint "eagle-import:0603-RES")
      (libsource (lib "eagle-import") (part "RESISTOR0603-RES"))
    )
    (comp (ref "R45")
      (value "330")
      (footprint "eagle-import:0603-RES")
      (libsource (lib "eagle-import") (part "RESISTOR0603-RES"))
    )
    (comp (ref "R46")
      (value "330")
      (footprint "eagle-import:0603-RES")
      (libsource (lib "eagle-import") (part "RESISTOR0603-RES"))
    )
    (comp (ref "R47")
      (value "330")
      (footprint "eagle-import:0603-RES")
      (libsource (lib "eagle-import") (part "RESISTOR0603-RES"))
    )
    (comp (ref "R48")
      (value "330")
      (footprint "eagle-import:0603-RES")
      (libsource (lib "eagle-import") (part "RESISTOR0603-RES"))
    )
    (comp (ref "R49")
      (value "330")
      (footprint "eagle-import:0603-RES")
      (libsource (lib "eagle-import") (part "RESISTOR0603-RES"))
    )
    (comp (ref "R50")
      (value "330")
      (footprint "eagle-import:0603-RES")
      (libsource (lib "eagle-import") (part "RESISTOR0603-RES"))
    )
    (comp (ref "R51")
      (value "330")
      (footprint "eagle-import:0603-RES")
      (libsource (lib "eagle-import") (part "RESISTOR0603-RES"))
    )
    (comp (ref "R52")
      (value "330")
      (footprint "eagle-import:0603-RES")
      (libsource (lib "eagle-import") (part "RESISTOR0603-RES"))
    )
    (comp (ref "R53")
      (value "330")
      (footprint "eagle-import:0603-RES")
      (libsource (lib "eagle-import") (part "RESISTOR0603-RES"))
    )
    (comp (ref "R54")
      (value "330")
      (footprint "eagle-import:0603-RES")
      (libsource (lib "eagle-import") (part "RESISTOR0603-RES"))
    )
    (comp (ref "R55")
      (value "330")
      (footprint "eagle-import:0603-RES")
      (libsource (lib "eagle-import") (part "RESISTOR0603-RES"))
    )
    (comp (ref "R56")
      (value "330")
      (footprint "eagle-import:0603-RES")
      (libsource (lib "eagle-import") (part "RESISTOR0603-RES"))
    )
    (comp (ref "R57")
      (value "330")
      (footprint "eagle-import:0603-RES")
      (libsource (lib "eagle-import") (part "RESISTOR0603-RES"))
    )
    (comp (ref "R58")
      (value "330")
      (footprint "eagle-import:0603-RES")
      (libsource (lib "eagle-import") (part "RESISTOR0603-RES"))
    )
    (comp (ref "R59")
      (value "330")
      (footprint "eagle-import:0603-RES")
      (libsource (lib "eagle-import") (part "RESISTOR0603-RES"))
    )
    (comp (ref "R60")
      (value "330")
      (footprint "eagle-import:0603-RES")
      (libsource (lib "eagle-import") (part "RESISTOR0603-RES"))
    )
    (comp (ref "R61")
      (value "1K")
      (footprint "eagle-import:0603-RES")
      (libsource (lib "eagle-import") (part "RESISTOR0603-RES"))
    )
    (comp (ref "R62")
      (value "1K")
      (footprint "eagle-import:0603-RES")
      (libsource (lib "eagle-import") (part "RESISTOR0603-RES"))
    )
    (comp (ref "R67")
      (value "470")
      (footprint "eagle-import:0603-RES")
      (libsource (lib "eagle-import") (part "RESISTOR0603-RES"))
    )
    (comp (ref "R68")
      (value "10K")
      (footprint "eagle-import:0603-RES")
      (libsource (lib "eagle-import") (part "RESISTOR0603-RES"))
    )
    (comp (ref "R69")
      (value "10K")
      (footprint "eagle-import:0603-RES")
      (libsource (lib "eagle-import") (part "RESISTOR0603-RES"))
    )
    (comp (ref "SCREEN")
      (value "ADAFRUIT-2.4-TFT")
      (footprint "eagle-import:ADAFRUIT-2.4-TFT")
      (libsource (lib "eagle-import") (part "ADAFRUIT-2.4-TFT"))
    )
    (comp (ref "SLAVE_DEBUG")
      (value "TEENSY-3.5")
      (footprint "eagle-import:TEENSY-3.5")
      (libsource (lib "eagle-import") (part "TEENSY-3.5"))
    )
    (comp (ref "SLAVE_MOTOR")
      (value "TEENSY-3.5")
      (footprint "eagle-import:TEENSY-3.5")
      (libsource (lib "eagle-import") (part "TEENSY-3.5"))
    )
    (comp (ref "SLAVE_SENSOR")
      (value "TEENSY-3.5")
      (footprint "eagle-import:TEENSY-3.5")
      (libsource (lib "eagle-import") (part "TEENSY-3.5"))
    )
    (comp (ref "U$1")
      (value "OPENMV3")
      (footprint "eagle-import:OPENMV3")
      (libsource (lib "eagle-import") (part "OPENMV3"))
    )
    (comp (ref "U$2")
      (value "GYRO")
      (footprint "eagle-import:GYRO")
      (libsource (lib "eagle-import") (part "GYRO"))
    )
    (comp (ref "VREG-3.3")
      (value "LM340S-05")
      (footprint "eagle-import:TO263-3")
      (libsource (lib "eagle-import") (part "LM340?-S05"))
    )
    (comp (ref "VREG-5")
      (value "V78-2000")
      (footprint "eagle-import:V78-2000")
      (libsource (lib "eagle-import") (part "V78-2000"))
    )
  )
  (nets
    (net (code "1") (name "/VIN") (class "Default")
      (node (ref "U$1") (pin "27") (pinfunction "VIN_27") (pintype "power_in"))
    )
    (net (code "2") (name "3.3V") (class "Default")
      (node (ref "BT_DEBUG") (pin "VCC") (pinfunction "VCC_VCC") (pintype "bidirectional"))
      (node (ref "BT_IRC") (pin "VCC") (pinfunction "VCC_VCC") (pintype "bidirectional"))
      (node (ref "C14") (pin "1") (pinfunction "1_1") (pintype "passive"))
      (node (ref "C15") (pin "1") (pinfunction "1_1") (pintype "passive"))
      (node (ref "C16") (pin "1") (pinfunction "1_1") (pintype "passive"))
      (node (ref "C17") (pin "1") (pinfunction "1_1") (pintype "passive"))
      (node (ref "C18") (pin "1") (pinfunction "1_1") (pintype "passive"))
      (node (ref "C19") (pin "1") (pinfunction "1_1") (pintype "passive"))
      (node (ref "C5") (pin "1") (pinfunction "1_1") (pintype "passive"))
      (node (ref "ENC_BL") (pin "4") (pinfunction "4_4") (pintype "passive"))
      (node (ref "ENC_BR") (pin "4") (pinfunction "4_4") (pintype "passive"))
      (node (ref "ENC_L") (pin "4") (pinfunction "4_4") (pintype "passive"))
      (node (ref "ENC_R") (pin "4") (pinfunction "4_4") (pintype "passive"))
      (node (ref "LIGHT_GATE") (pin "1") (pinfunction "1_1") (pintype "passive"))
      (node (ref "LS_CONNECTOR") (pin "9") (pinfunction "9_9") (pintype "passive"))
      (node (ref "MASTER") (pin "3.3V-1") (pinfunction "3.3V-1_3.3V-1") (pintype "bidirectional"))
      (node (ref "Q1") (pin "1") (pinfunction "G_1") (pintype "passive"))
      (node (ref "R11") (pin "2") (pinfunction "2_2") (pintype "passive"))
      (node (ref "R13") (pin "2") (pinfunction "2_2") (pintype "passive"))
      (node (ref "R21") (pin "2") (pinfunction "2_2") (pintype "passive"))
      (node (ref "R22") (pin "2") (pinfunction "2_2") (pintype "passive"))
      (node (ref "R30") (pin "2") (pinfunction "2_2") (pintype "passive"))
      (node (ref "R31") (pin "2") (pinfunction "2_2") (pintype "passive"))
      (node (ref "R39") (pin "2") (pinfunction "2_2") (pintype "passive"))
      (node (ref "R4") (pin "1") (pinfunction "1_1") (pintype "passive"))
      (node (ref "R40") (pin "2") (pinfunction "2_2") (pintype "passive"))
      (node (ref "R43") (pin "1") (pinfunction "1_1") (pintype "passive"))
      (node (ref "R44") (pin "1") (pinfunction "1_1") (pintype "passive"))
      (node (ref "R45") (pin "1") (pinfunction "1_1") (pintype "passive"))
      (node (ref "R46") (pin "1") (pinfunction "1_1") (pintype "passive"))
      (node (ref "R47") (pin "1") (pinfunction "1_1") (pintype "passive"))
      (node (ref "R48") (pin "1") (pinfunction "1_1") (pintype "passive"))
      (node (ref "R49") (pin "1") (pinfunction "1_1") (pintype "passive"))
      (node (ref "R50") (pin "1") (pinfunction "1_1") (pintype "passive"))
      (node (ref "R51") (pin "1") (pinfunction "1_1") (pintype "passive"))
      (node (ref "R52") (pin "1") (pinfunction "1_1") (pintype "passive"))
      (node (ref "R53") (pin "1") (pinfunction "1_1") (pintype "passive"))
      (node (ref "R54") (pin "1") (pinfunction "1_1") (pintype "passive"))
      (node (ref "R69") (pin "1") (pinfunction "1_1") (pintype "passive"))
      (node (ref "SCREEN") (pin "VIN_2") (pinfunction "VIN_2_VIN_2") (pintype "bidirectional"))
      (node (ref "SLAVE_DEBUG") (pin "3.3V-1") (pinfunction "3.3V-1_3.3V-1") (pintype "bidirectional"))
      (node (ref "SLAVE_MOTOR") (pin "3.3V-1") (pinfunction "3.3V-1_3.3V-1") (pintype "bidirectional"))
      (node (ref "SLAVE_SENSOR") (pin "3.3V-1") (pinfunction "3.3V-1_3.3V-1") (pintype "bidirectional"))
      (node (ref "U$1") (pin "18") (pinfunction "3.3V_18") (pintype "power_in"))
      (node (ref "U$2") (pin "3.3V") (pinfunction "3.3V_3.3V") (pintype "bidirectional"))
      (node (ref "VREG-3.3") (pin "2") (pinfunction "VO_2") (pintype "passive"))
      (node (ref "VREG-3.3") (pin "TAB") (pinfunction "VO_TAB") (pintype "passive"))
    )
    (net (code "3") (name "5V") (class "Default")
      (node (ref "C3") (pin "1") (pinfunction "1_1") (pintype "passive"))
      (node (ref "C62") (pin "1") (pinfunction "1_1") (pintype "passive"))
      (node (ref "C63") (pin "1") (pinfunction "1_1") (pintype "passive"))
      (node (ref "C64") (pin "1") (pinfunction "1_1") (pintype "passive"))
      (node (ref "C65") (pin "1") (pinfunction "1_1") (pintype "passive"))
      (node (ref "C66") (pin "1") (pinfunction "1_1") (pintype "passive"))
      (node (ref "C67") (pin "1") (pinfunction "1_1") (pintype "passive"))
      (node (ref "C68") (pin "1") (pinfunction "1_1") (pintype "passive"))
      (node (ref "C69") (pin "1") (pinfunction "1_1") (pintype "passive"))
      (node (ref "C70") (pin "1") (pinfunction "1_1") (pintype "passive"))
      (node (ref "C71") (pin "1") (pinfunction "1_1") (pintype "passive"))
      (node (ref "C72") (pin "1") (pinfunction "1_1") (pintype "passive"))
      (node (ref "C73") (pin "1") (pinfunction "1_1") (pintype "passive"))
      (node (ref "D10") (pin "1") (pinfunction "VDD_1") (pintype "power_in"))
      (node (ref "D11") (pin "1") (pinfunction "VDD_1") (pintype "power_in"))
      (node (ref "D12") (pin "1") (pinfunction "VDD_1") (pintype "power_in"))
      (node (ref "D13") (pin "1") (pinfunction "VDD_1") (pintype "power_in"))
      (node (ref "D14") (pin "1") (pinfunction "VDD_1") (pintype "power_in"))
      (node (ref "D2") (pin "A") (pinfunction "A_A") (pintype "passive"))
      (node (ref "D3") (pin "1") (pinfunction "VDD_1") (pintype "power_in"))
      (node (ref "D4") (pin "1") (pinfunction "VDD_1") (pintype "power_in"))
      (node (ref "D5") (pin "1") (pinfunction "VDD_1") (pintype "power_in"))
      (node (ref "D6") (pin "1") (pinfunction "VDD_1") (pintype "power_in"))
      (node (ref "D7") (pin "1") (pinfunction "VDD_1") (pintype "power_in"))
      (node (ref "D8") (pin "1") (pinfunction "VDD_1") (pintype "power_in"))
      (node (ref "D9") (pin "1") (pinfunction "VDD_1") (pintype "power_in"))
      (node (ref "R3") (pin "1") (pinfunction "1_1") (pintype "passive"))
      (node (ref "R68") (pin "1") (pinfunction "1_1") (pintype "passive"))
      (node (ref "VREG-5") (pin "3") (pinfunction "VOUT_3") (pintype "bidirectional"))
    )
    (net (code "4") (name "BT_DEBUG_RX") (class "Default")
      (node (ref "BT_DEBUG") (pin "UART_TX") (pinfunction "UART_TX_UART_TX") (pintype "bidirectional"))
      (node (ref "SLAVE_DEBUG") (pin "34") (pinfunction "34/A15/RX5_34") (pintype "bidirectional"))
    )
    (net (code "5") (name "BT_DEBUG_TX") (class "Default")
      (node (ref "BT_DEBUG") (pin "UART_RX") (pinfunction "UART_RX_UART_RX") (pintype "bidirectional"))
      (node (ref "SLAVE_DEBUG") (pin "33") (pinfunction "33/A14/TX5_33") (pintype "bidirectional"))
    )
    (net (code "6") (name "BT_IRC_RX") (class "Default")
      (node (ref "BT_IRC") (pin "UART_TX") (pinfunction "UART_TX_UART_TX") (pintype "bidirectional"))
      (node (ref "MASTER") (pin "34") (pinfunction "34/A15/RX5_34") (pintype "bidirectional"))
    )
    (net (code "7") (name "BT_IRC_TX") (class "Default")
      (node (ref "BT_IRC") (pin "UART_RX") (pinfunction "UART_RX_UART_RX") (pintype "bidirectional"))
      (node (ref "MASTER") (pin "33") (pinfunction "33/A14/TX5_33") (pintype "bidirectional"))
    )
    (net (code "8") (name "CAM_RX") (class "Default")
      (node (ref "MASTER") (pin "7") (pinfunction "7/PWM/RX3_7") (pintype "bidirectional"))
      (node (ref "U$1") (pin "15") (pinfunction "TXD/SCL_15") (pintype "bidirectional"))
    )
    (net (code "9") (name "CAM_TX") (class "Default")
      (node (ref "MASTER") (pin "8") (pinfunction "8/PWM/TX3_8") (pintype "bidirectional"))
      (node (ref "U$1") (pin "16") (pinfunction "RXD/SDA_16") (pintype "bidirectional"))
    )
    (net (code "10") (name "CS_DEBUG") (class "Default")
      (node (ref "MASTER") (pin "15") (pinfunction "15/A1/CS0_15") (pintype "bidirectional"))
      (node (ref "SLAVE_DEBUG") (pin "10") (pinfunction "10/PWM/TX2/CS0_10") (pintype "bidirectional"))
    )
    (net (code "11") (name "CS_MOTOR") (class "Default")
      (node (ref "MASTER") (pin "10") (pinfunction "10/PWM/TX2/CS0_10") (pintype "bidirectional"))
      (node (ref "SLAVE_MOTOR") (pin "10") (pinfunction "10/PWM/TX2/CS0_10") (pintype "bidirectional"))
    )
    (net (code "12") (name "CS_SENSOR") (class "Default")
      (node (ref "MASTER") (pin "9") (pinfunction "9/PWM/RX2/CS0_9") (pintype "bidirectional"))
      (node (ref "SLAVE_SENSOR") (pin "10") (pinfunction "10/PWM/TX2/CS0_10") (pintype "bidirectional"))
    )
    (net (code "13") (name "GND") (class "Default")
      (node (ref "3.3V_ON") (pin "C") (pinfunction "C_C") (pintype "passive"))
      (node (ref "5V_ON") (pin "C") (pinfunction "C_C") (pintype "passive"))
      (node (ref "BT_DEBUG") (pin "GND") (pinfunction "GND_GND") (pintype "bidirectional"))
      (node (ref "BT_DEBUG_LED") (pin "C") (pinfunction "C_C") (pintype "passive"))
      (node (ref "BT_IRC") (pin "GND") (pinfunction "GND_GND") (pintype "bidirectional"))
      (node (ref "BT_IRC_LED") (pin "C") (pinfunction "C_C") (pintype "passive"))
      (node (ref "C1") (pin "-") (pinfunction "-_-") (pintype "passive"))
      (node (ref "C10") (pin "-") (pinfunction "-_-") (pintype "passive"))
      (node (ref "C11") (pin "2") (pinfunction "2_2") (pintype "passive"))
      (node (ref "C12") (pin "2") (pinfunction "2_2") (pintype "passive"))
      (node (ref "C13") (pin "2") (pinfunction "2_2") (pintype "passive"))
      (node (ref "C14") (pin "2") (pinfunction "2_2") (pintype "passive"))
      (node (ref "C15") (pin "2") (pinfunction "2_2") (pintype "passive"))
      (node (ref "C16") (pin "2") (pinfunction "2_2") (pintype "passive"))
      (node (ref "C17") (pin "2") (pinfunction "2_2") (pintype "passive"))
      (node (ref "C18") (pin "2") (pinfunction "2_2") (pintype "passive"))
      (node (ref "C19") (pin "2") (pinfunction "2_2") (pintype "passive"))
      (node (ref "C2") (pin "2") (pinfunction "2_2") (pintype "passive"))
      (node (ref "C3") (pin "2") (pinfunction "2_2") (pintype "passive"))
      (node (ref "C38") (pin "2") (pinfunction "2_2") (pintype "passive"))
      (node (ref "C39") (pin "2") (pinfunction "2_2") (pintype "passive"))
      (node (ref "C4") (pin "2") (pinfunction "2_2") (pintype "passive"))
      (node (ref "C40") (pin "2") (pinfunction "2_2") (pintype "passive"))
      (node (ref "C41") (pin "2") (pinfunction "2_2") (pintype "passive"))
      (node (ref "C42") (pin "2") (pinfunction "2_2") (pintype "passive"))
      (node (ref "C43") (pin "2") (pinfunction "2_2") (pintype "passive"))
      (node (ref "C44") (pin "2") (pinfunction "2_2") (pintype "passive"))
      (node (ref "C45") (pin "2") (pinfunction "2_2") (pintype "passive"))
      (node (ref "C46") (pin "2") (pinfunction "2_2") (pintype "passive"))
      (node (ref "C47") (pin "2") (pinfunction "2_2") (pintype "passive"))
      (node (ref "C48") (pin "2") (pinfunction "2_2") (pintype "passive"))
      (node (ref "C49") (pin "2") (pinfunction "2_2") (pintype "passive"))
      (node (ref "C5") (pin "2") (pinfunction "2_2") (pintype "passive"))
      (node (ref "C50") (pin "2") (pinfunction "2_2") (pintype "passive"))
      (node (ref "C51") (pin "2") (pinfunction "2_2") (pintype "passive"))
      (node (ref "C52") (pin "2") (pinfunction "2_2") (pintype "passive"))
      (node (ref "C53") (pin "2") (pinfunction "2_2") (pintype "passive"))
      (node (ref "C54") (pin "2") (pinfunction "2_2") (pintype "passive"))
      (node (ref "C55") (pin "2") (pinfunction "2_2") (pintype "passive"))
      (node (ref "C56") (pin "2") (pinfunction "2_2") (pintype "passive"))
      (node (ref "C57") (pin "2") (pinfunction "2_2") (pintype "passive"))
      (node (ref "C58") (pin "2") (pinfunction "2_2") (pintype "passive"))
      (node (ref "C59") (pin "2") (pinfunction "2_2") (pintype "passive"))
      (node (ref "C6") (pin "2") (pinfunction "2_2") (pintype "passive"))
      (node (ref "C60") (pin "2") (pinfunction "2_2") (pintype "passive"))
      (node (ref "C61") (pin "2") (pinfunction "2_2") (pintype "passive"))
      (node (ref "C62") (pin "2") (pinfunction "2_2") (pintype "passive"))
      (node (ref "C63") (pin "2") (pinfunction "2_2") (pintype "passive"))
      (node (ref "C64") (pin "2") (pinfunction "2_2") (pintype "passive"))
      (node (ref "C65") (pin "2") (pinfunction "2_2") (pintype "passive"))
      (node (ref "C66") (pin "2") (pinfunction "2_2") (pintype "passive"))
      (node (ref "C67") (pin "2") (pinfunction "2_2") (pintype "passive"))
      (node (ref "C68") (pin "2") (pinfunction "2_2") (pintype "passive"))
      (node (ref "C69") (pin "2") (pinfunction "2_2") (pintype "passive"))
      (node (ref "C7") (pin "-") (pinfunction "-_-") (pintype "passive"))
      (node (ref "C70") (pin "2") (pinfunction "2_2") (pintype "passive"))
      (node (ref "C71") (pin "2") (pinfunction "2_2") (pintype "passive"))
      (node (ref "C72") (pin "2") (pinfunction "2_2") (pintype "passive"))
      (node (ref "C73") (pin "2") (pinfunction "2_2") (pintype "passive"))
      (node (ref "C8") (pin "-") (pinfunction "-_-") (pintype "passive"))
      (node (ref "C9") (pin "-") (pinfunction "-_-") (pintype "passive"))
      (node (ref "D10") (pin "3") (pinfunction "VSS_3") (pintype "power_in"))
      (node (ref "D11") (pin "3") (pinfunction "VSS_3") (pintype "power_in"))
      (node (ref "D12") (pin "3") (pinfunction "VSS_3") (pintype "power_in"))
      (node (ref "D13") (pin "3") (pinfunction "VSS_3") (pintype "power_in"))
      (node (ref "D14") (pin "3") (pinfunction "VSS_3") (pintype "power_in"))
      (node (ref "D3") (pin "3") (pinfunction "VSS_3") (pintype "power_in"))
      (node (ref "D4") (pin "3") (pinfunction "VSS_3") (pintype "power_in"))
      (node (ref "D5") (pin "3") (pinfunction "VSS_3") (pintype "power_in"))
      (node (ref "D6") (pin "3") (pinfunction "VSS_3") (pintype "power_in"))
      (node (ref "D7") (pin "3") (pinfunction "VSS_3") (pintype "power_in"))
      (node (ref "D8") (pin "3") (pinfunction "VSS_3") (pintype "power_in"))
      (node (ref "D9") (pin "3") (pinfunction "VSS_3") (pintype "power_in"))
      (node (ref "ENC_BL") (pin "1") (pinfunction "1_1") (pintype "passive"))
      (node (ref "ENC_BR") (pin "1") (pinfunction "1_1") (pintype "passive"))
      (node (ref "ENC_L") (pin "1") (pinfunction "1_1") (pintype "passive"))
      (node (ref "ENC_R") (pin "1") (pinfunction "1_1") (pintype "passive"))
      (node (ref "IR0") (pin "2") (pinfunction "GND_2") (pintype "bidirectional"))
      (node (ref "IR1") (pin "2") (pinfunction "GND_2") (pintype "bidirectional"))
      (node (ref "IR10") (pin "2") (pinfunction "GND_2") (pintype "bidirectional"))
      (node (ref "IR11") (pin "2") (pinfunction "GND_2") (pintype "bidirectional"))
      (node (ref "IR12") (pin "2") (pinfunction "GND_2") (pintype "bidirectional"))
      (node (ref "IR13") (pin "2") (pinfunction "GND_2") (pintype "bidirectional"))
      (node (ref "IR14") (pin "2") (pinfunction "GND_2") (pintype "bidirectional"))
      (node (ref "IR15") (pin "2") (pinfunction "GND_2") (pintype "bidirectional"))
      (node (ref "IR16") (pin "2") (pinfunction "GND_2") (pintype "bidirectional"))
      (node (ref "IR17") (pin "2") (pinfunction "GND_2") (pintype "bidirectional"))
      (node (ref "IR18") (pin "2") (pinfunction "GND_2") (pintype "bidirectional"))
      (node (ref "IR19") (pin "2") (pinfunction "GND_2") (pintype "bidirectional"))
      (node (ref "IR2") (pin "2") (pinfunction "GND_2") (pintype "bidirectional"))
      (node (ref "IR20") (pin "2") (pinfunction "GND_2") (pintype "bidirectional"))
      (node (ref "IR21") (pin "2") (pinfunction "GND_2") (pintype "bidirectional"))
      (node (ref "IR22") (pin "2") (pinfunction "GND_2") (pintype "bidirectional"))
      (node (ref "IR23") (pin "2") (pinfunction "GND_2") (pintype "bidirectional"))
      (node (ref "IR3") (pin "2") (pinfunction "GND_2") (pintype "bidirectional"))
      (node (ref "IR4") (pin "2") (pinfunction "GND_2") (pintype "bidirectional"))
      (node (ref "IR5") (pin "2") (pinfunction "GND_2") (pintype "bidirectional"))
      (node (ref "IR6") (pin "2") (pinfunction "GND_2") (pintype "bidirectional"))
      (node (ref "IR7") (pin "2") (pinfunction "GND_2") (pintype "bidirectional"))
      (node (ref "IR8") (pin "2") (pinfunction "GND_2") (pintype "bidirectional"))
      (node (ref "IR9") (pin "2") (pinfunction "GND_2") (pintype "bidirectional"))
      (node (ref "LED_DEBUG1") (pin "C") (pinfunction "C_C") (pintype "passive"))
      (node (ref "LED_DEBUG2") (pin "C") (pinfunction "C_C") (pintype "passive"))
      (node (ref "LED_DEBUG3") (pin "C") (pinfunction "C_C") (pintype "passive"))
      (node (ref "LED_DEBUG4") (pin "C") (pinfunction "C_C") (pintype "passive"))
      (node (ref "LED_DEBUG5") (pin "C") (pinfunction "C_C") (pintype "passive"))
      (node (ref "LED_DEBUG6") (pin "C") (pinfunction "C_C") (pintype "passive"))
      (node (ref "LIGHT_GATE") (pin "4") (pinfunction "4_4") (pintype "passive"))
      (node (ref "LIGHT_GATE") (pin "5") (pinfunction "5_5") (pintype "passive"))
      (node (ref "LS_CONNECTOR") (pin "11") (pinfunction "11_11") (pintype "passive"))
      (node (ref "LS_CONNECTOR") (pin "13") (pinfunction "13_13") (pintype "passive"))
      (node (ref "MASTER") (pin "AGND") (pinfunction "AGND_AGND") (pintype "bidirectional"))
      (node (ref "MASTER") (pin "GND") (pinfunction "GND_GND") (pintype "bidirectional"))
      (node (ref "MASTER") (pin "GND-1") (pinfunction "GND-1_GND-1") (pintype "bidirectional"))
      (node (ref "MASTER") (pin "GND-2") (pinfunction "GND-2_GND-2") (pintype "bidirectional"))
      (node (ref "MASTER") (pin "GND-3") (pinfunction "GND-3_GND-3") (pintype "bidirectional"))
      (node (ref "MASTER") (pin "GND-4") (pinfunction "GND-4_GND-4") (pintype "bidirectional"))
      (node (ref "P1") (pin "1") (pinfunction "GND_A-1_1") (pintype "bidirectional"))
      (node (ref "P1") (pin "3") (pinfunction "GND_A-2_3") (pintype "bidirectional"))
      (node (ref "P1") (pin "30") (pinfunction "GND_B-1_30") (pintype "bidirectional"))
      (node (ref "P1") (pin "31") (pinfunction "GND_B-2_31") (pintype "bidirectional"))
      (node (ref "P1") (pin "32") (pinfunction "GND_B-3_32") (pintype "bidirectional"))
      (node (ref "P1") (pin "33") (pinfunction "GND_B-4_33") (pintype "bidirectional"))
      (node (ref "P1") (pin "34") (pinfunction "GND_B-5_34") (pintype "bidirectional"))
      (node (ref "P1") (pin "36") (pinfunction "GND_B-6_36") (pintype "bidirectional"))
      (node (ref "P1") (pin "4") (pinfunction "GND_A-3_4") (pintype "bidirectional"))
      (node (ref "P1") (pin "5") (pinfunction "GND_A-4_5") (pintype "bidirectional"))
      (node (ref "P1") (pin "6") (pinfunction "GND_A-5_6") (pintype "bidirectional"))
      (node (ref "P1") (pin "7") (pinfunction "GND_A-6_7") (pintype "bidirectional"))
      (node (ref "P2") (pin "1") (pinfunction "GND_A-1_1") (pintype "bidirectional"))
      (node (ref "P2") (pin "3") (pinfunction "GND_A-2_3") (pintype "bidirectional"))
      (node (ref "P2") (pin "30") (pinfunction "GND_B-1_30") (pintype "bidirectional"))
      (node (ref "P2") (pin "31") (pinfunction "GND_B-2_31") (pintype "bidirectional"))
      (node (ref "P2") (pin "32") (pinfunction "GND_B-3_32") (pintype "bidirectional"))
      (node (ref "P2") (pin "33") (pinfunction "GND_B-4_33") (pintype "bidirectional"))
      (node (ref "P2") (pin "34") (pinfunction "GND_B-5_34") (pintype "bidirectional"))
      (node (ref "P2") (pin "36") (pinfunction "GND_B-6_36") (pintype "bidirectional"))
      (node (ref "P2") (pin "4") (pinfunction "GND_A-3_4") (pintype "bidirectional"))
      (node (ref "P2") (pin "5") (pinfunction "GND_A-4_5") (pintype "bidirectional"))
      (node (ref "P2") (pin "6") (pinfunction "GND_A-5_6") (pintype "bidirectional"))
      (node (ref "P2") (pin "7") (pinfunction "GND_A-6_7") (pintype "bidirectional"))
      (node (ref "P3") (pin "1") (pinfunction "GND_A-1_1") (pintype "bidirectional"))
      (node (ref "P3") (pin "3") (pinfunction "GND_A-2_3") (pintype "bidirectional"))
      (node (ref "P3") (pin "30") (pinfunction "GND_B-1_30") (pintype "bidirectional"))
      (node (ref "P3") (pin "31") (pinfunction "GND_B-2_31") (pintype "bidirectional"))
      (node (ref "P3") (pin "32") (pinfunction "GND_B-3_32") (pintype "bidirectional"))
      (node (ref "P3") (pin "33") (pinfunction "GND_B-4_33") (pintype "bidirectional"))
      (node (ref "P3") (pin "34") (pinfunction "GND_B-5_34") (pintype "bidirectional"))
      (node (ref "P3") (pin "36") (pinfunction "GND_B-6_36") (pintype "bidirectional"))
      (node (ref "P3") (pin "4") (pinfunction "GND_A-3_4") (pintype "bidirectional"))
      (node (ref "P3") (pin "5") (pinfunction "GND_A-4_5") (pintype "bidirectional"))
      (node (ref "P3") (pin "6") (pinfunction "GND_A-5_6") (pintype "bidirectional"))
      (node (ref "P3") (pin "7") (pinfunction "GND_A-6_7") (pintype "bidirectional"))
      (node (ref "P4") (pin "1") (pinfunction "GND_A-1_1") (pintype "bidirectional"))
      (node (ref "P4") (pin "3") (pinfunction "GND_A-2_3") (pintype "bidirectional"))
      (node (ref "P4") (pin "30") (pinfunction "GND_B-1_30") (pintype "bidirectional"))
      (node (ref "P4") (pin "31") (pinfunction "GND_B-2_31") (pintype "bidirectional"))
      (node (ref "P4") (pin "32") (pinfunction "GND_B-3_32") (pintype "bidirectional"))
      (node (ref "P4") (pin "33") (pinfunction "GND_B-4_33") (pintype "bidirectional"))
      (node (ref "P4") (pin "34") (pinfunction "GND_B-5_34") (pintype "bidirectional"))
      (node (ref "P4") (pin "36") (pinfunction "GND_B-6_36") (pintype "bidirectional"))
      (node (ref "P4") (pin "4") (pinfunction "GND_A-3_4") (pintype "bidirectional"))
      (node (ref "P4") (pin "5") (pinfunction "GND_A-4_5") (pintype "bidirectional"))
      (node (ref "P4") (pin "6") (pinfunction "GND_A-5_6") (pintype "bidirectional"))
      (node (ref "P4") (pin "7") (pinfunction "GND_A-6_7") (pintype "bidirectional"))
      (node (ref "PWR_IN") (pin "1") (pinfunction "1_1") (pintype "passive"))
      (node (ref "Q2") (pin "2") (pinfunction "E_2") (pintype "passive"))
      (node (ref "Q3") (pin "2") (pinfunction "E_2") (pintype "passive"))
      (node (ref "R15") (pin "2") (pinfunction "2_2") (pintype "passive"))
      (node (ref "R2") (pin "2") (pinfunction "2_2") (pintype "passive"))
      (node (ref "R24") (pin "2") (pinfunction "2_2") (pintype "passive"))
      (node (ref "R33") (pin "2") (pinfunction "2_2") (pintype "passive"))
      (node (ref "R42") (pin "2") (pinfunction "2_2") (pintype "passive"))
      (node (ref "SCREEN") (pin "GND") (pinfunction "GND_GND") (pintype "bidirectional"))
      (node (ref "SCREEN") (pin "GND_2") (pinfunction "GND_2_GND_2") (pintype "bidirectional"))
      (node (ref "SLAVE_DEBUG") (pin "AGND") (pinfunction "AGND_AGND") (pintype "bidirectional"))
      (node (ref "SLAVE_DEBUG") (pin "GND") (pinfunction "GND_GND") (pintype "bidirectional"))
      (node (ref "SLAVE_DEBUG") (pin "GND-1") (pinfunction "GND-1_GND-1") (pintype "bidirectional"))
      (node (ref "SLAVE_DEBUG") (pin "GND-2") (pinfunction "GND-2_GND-2") (pintype "bidirectional"))
      (node (ref "SLAVE_DEBUG") (pin "GND-3") (pinfunction "GND-3_GND-3") (pintype "bidirectional"))
      (node (ref "SLAVE_DEBUG") (pin "GND-4") (pinfunction "GND-4_GND-4") (pintype "bidirectional"))
      (node (ref "SLAVE_MOTOR") (pin "AGND") (pinfunction "AGND_AGND") (pintype "bidirectional"))
      (node (ref "SLAVE_MOTOR") (pin "GND") (pinfunction "GND_GND") (pintype "bidirectional"))
      (node (ref "SLAVE_MOTOR") (pin "GND-1") (pinfunction "GND-1_GND-1") (pintype "bidirectional"))
      (node (ref "SLAVE_MOTOR") (pin "GND-2") (pinfunction "GND-2_GND-2") (pintype "bidirectional"))
      (node (ref "SLAVE_MOTOR") (pin "GND-3") (pinfunction "GND-3_GND-3") (pintype "bidirectional"))
      (node (ref "SLAVE_MOTOR") (pin "GND-4") (pinfunction "GND-4_GND-4") (pintype "bidirectional"))
      (node (ref "SLAVE_SENSOR") (pin "AGND") (pinfunction "AGND_AGND") (pintype "bidirectional"))
      (node (ref "SLAVE_SENSOR") (pin "GND") (pinfunction "GND_GND") (pintype "bidirectional"))
      (node (ref "SLAVE_SENSOR") (pin "GND-1") (pinfunction "GND-1_GND-1") (pintype "bidirectional"))
      (node (ref "SLAVE_SENSOR") (pin "GND-2") (pinfunction "GND-2_GND-2") (pintype "bidirectional"))
      (node (ref "SLAVE_SENSOR") (pin "GND-3") (pinfunction "GND-3_GND-3") (pintype "bidirectional"))
      (node (ref "SLAVE_SENSOR") (pin "GND-4") (pinfunction "GND-4_GND-4") (pintype "bidirectional"))
      (node (ref "U$1") (pin "28") (pinfunction "GND_28") (pintype "power_in"))
      (node (ref "U$2") (pin "GND") (pinfunction "GND_GND") (pintype "bidirectional"))
      (node (ref "VREG-3.3") (pin "1") (pinfunction "GND_1") (pintype "passive"))
      (node (ref "VREG-5") (pin "2") (pinfunction "GND_2") (pintype "bidirectional"))
    )
    (net (code "14") (name "GYRO_CS1") (class "Default")
      (node (ref "MASTER") (pin "43") (pinfunction "43/CS2_43") (pintype "bidirectional"))
      (node (ref "U$2") (pin "CS1") (pinfunction "CS1_CS1") (pintype "bidirectional"))
    )
    (net (code "15") (name "GYRO_CS2") (class "Default")
      (node (ref "MASTER") (pin "55") (pinfunction "55_55") (pintype "bidirectional"))
      (node (ref "U$2") (pin "CS2") (pinfunction "CS2_CS2") (pintype "bidirectional"))
    )
    (net (code "16") (name "GYRO_CS3") (class "Default")
      (node (ref "MASTER") (pin "54") (pinfunction "54/CS2_54") (pintype "bidirectional"))
      (node (ref "U$2") (pin "CS3") (pinfunction "CS3_CS3") (pintype "bidirectional"))
    )
    (net (code "17") (name "GYRO_MISO") (class "Default")
      (node (ref "MASTER") (pin "45") (pinfunction "45/MISO2_45") (pintype "bidirectional"))
      (node (ref "U$2") (pin "MISO") (pinfunction "MISO_MISO") (pintype "bidirectional"))
    )
    (net (code "18") (name "GYRO_MOSI") (class "Default")
      (node (ref "MASTER") (pin "44") (pinfunction "44/MOSI2_44") (pintype "bidirectional"))
      (node (ref "U$2") (pin "MOSI") (pinfunction "MOSI_MOSI") (pintype "bidirectional"))
    )
    (net (code "19") (name "GYRO_SCLK") (class "Default")
      (node (ref "MASTER") (pin "46") (pinfunction "46/SCK2_46") (pintype "bidirectional"))
      (node (ref "U$2") (pin "SCLK") (pinfunction "SCLK_SCLK") (pintype "bidirectional"))
    )
    (net (code "20") (name "IR0") (class "Default")
      (node (ref "IR0") (pin "1") (pinfunction "OUT_1") (pintype "bidirectional"))
      (node (ref "SLAVE_SENSOR") (pin "0") (pinfunction "0/RX1/MOSI1_0") (pintype "bidirectional"))
    )
    (net (code "21") (name "IR1") (class "Default")
      (node (ref "IR1") (pin "1") (pinfunction "OUT_1") (pintype "bidirectional"))
      (node (ref "SLAVE_SENSOR") (pin "1") (pinfunction "1/TX1/MISO1_1") (pintype "bidirectional"))
    )
    (net (code "22") (name "IR2") (class "Default")
      (node (ref "IR2") (pin "1") (pinfunction "OUT_1") (pintype "bidirectional"))
      (node (ref "SLAVE_SENSOR") (pin "2") (pinfunction "2/PWM_2") (pintype "bidirectional"))
    )
    (net (code "23") (name "IR3") (class "Default")
      (node (ref "IR3") (pin "1") (pinfunction "OUT_1") (pintype "bidirectional"))
      (node (ref "SLAVE_SENSOR") (pin "3") (pinfunction "3/PWM/CAN0TX/SCL2_3") (pintype "bidirectional"))
    )
    (net (code "24") (name "IR4") (class "Default")
      (node (ref "IR4") (pin "1") (pinfunction "OUT_1") (pintype "bidirectional"))
      (node (ref "SLAVE_SENSOR") (pin "4") (pinfunction "4/PWM/CAN0RX/SDA2_4") (pintype "bidirectional"))
    )
    (net (code "25") (name "IR5") (class "Default")
      (node (ref "IR5") (pin "1") (pinfunction "OUT_1") (pintype "bidirectional"))
      (node (ref "SLAVE_SENSOR") (pin "5") (pinfunction "5/PWM_5") (pintype "bidirectional"))
    )
    (net (code "26") (name "IR6") (class "Default")
      (node (ref "IR6") (pin "1") (pinfunction "OUT_1") (pintype "bidirectional"))
      (node (ref "SLAVE_SENSOR") (pin "6") (pinfunction "6/PWM_6") (pintype "bidirectional"))
    )
    (net (code "27") (name "IR7") (class "Default")
      (node (ref "IR7") (pin "1") (pinfunction "OUT_1") (pintype "bidirectional"))
      (node (ref "SLAVE_SENSOR") (pin "7") (pinfunction "7/PWM/RX3_7") (pintype "bidirectional"))
    )
    (net (code "28") (name "IR8") (class "Default")
      (node (ref "IR8") (pin "1") (pinfunction "OUT_1") (pintype "bidirectional"))
      (node (ref "SLAVE_SENSOR") (pin "8") (pinfunction "8/PWM/TX3_8") (pintype "bidirectional"))
    )
    (net (code "29") (name "IR9") (class "Default")
      (node (ref "IR9") (pin "1") (pinfunction "OUT_1") (pintype "bidirectional"))
      (node (ref "SLAVE_SENSOR") (pin "9") (pinfunction "9/PWM/RX2/CS0_9") (pintype "bidirectional"))
    )
    (net (code "30") (name "IR10") (class "Default")
      (node (ref "IR10") (pin "1") (pinfunction "OUT_1") (pintype "bidirectional"))
      (node (ref "SLAVE_SENSOR") (pin "19") (pinfunction "19/A5/SCL0_19") (pintype "bidirectional"))
    )
    (net (code "31") (name "IR11") (class "Default")
      (node (ref "IR11") (pin "1") (pinfunction "OUT_1") (pintype "bidirectional"))
      (node (ref "SLAVE_SENSOR") (pin "20") (pinfunction "20/A6/PWM/CS0_20") (pintype "bidirectional"))
    )
    (net (code "32") (name "IR12") (class "Default")
      (node (ref "IR12") (pin "1") (pinfunction "OUT_1") (pintype "bidirectional"))
      (node (ref "SLAVE_SENSOR") (pin "21") (pinfunction "21/A7/PWM/CS0_21") (pintype "bidirectional"))
    )
    (net (code "33") (name "IR13") (class "Default")
      (node (ref "IR13") (pin "1") (pinfunction "OUT_1") (pintype "bidirectional"))
      (node (ref "SLAVE_SENSOR") (pin "22") (pinfunction "22/A8/PWM_22") (pintype "bidirectional"))
    )
    (net (code "34") (name "IR14") (class "Default")
      (node (ref "IR14") (pin "1") (pinfunction "OUT_1") (pintype "bidirectional"))
      (node (ref "SLAVE_SENSOR") (pin "23") (pinfunction "23/A9/PWM_23") (pintype "bidirectional"))
    )
    (net (code "35") (name "IR15") (class "Default")
      (node (ref "IR15") (pin "1") (pinfunction "OUT_1") (pintype "bidirectional"))
      (node (ref "SLAVE_SENSOR") (pin "24") (pinfunction "24_24") (pintype "bidirectional"))
    )
    (net (code "36") (name "IR16") (class "Default")
      (node (ref "IR16") (pin "1") (pinfunction "OUT_1") (pintype "bidirectional"))
      (node (ref "SLAVE_SENSOR") (pin "25") (pinfunction "25_25") (pintype "bidirectional"))
    )
    (net (code "37") (name "IR17") (class "Default")
      (node (ref "IR17") (pin "1") (pinfunction "OUT_1") (pintype "bidirectional"))
      (node (ref "SLAVE_SENSOR") (pin "26") (pinfunction "26_26") (pintype "bidirectional"))
    )
    (net (code "38") (name "IR18") (class "Default")
      (node (ref "IR18") (pin "1") (pinfunction "OUT_1") (pintype "bidirectional"))
      (node (ref "SLAVE_SENSOR") (pin "27") (pinfunction "27_27") (pintype "bidirectional"))
    )
    (net (code "39") (name "IR19") (class "Default")
      (node (ref "IR19") (pin "1") (pinfunction "OUT_1") (pintype "bidirectional"))
      (node (ref "SLAVE_SENSOR") (pin "28") (pinfunction "28_28") (pintype "bidirectional"))
    )
    (net (code "40") (name "IR20") (class "Default")
      (node (ref "IR20") (pin "1") (pinfunction "OUT_1") (pintype "bidirectional"))
      (node (ref "SLAVE_SENSOR") (pin "29") (pinfunction "29/PWM_29") (pintype "bidirectional"))
    )
    (net (code "41") (name "IR21") (class "Default")
      (node (ref "IR21") (pin "1") (pinfunction "OUT_1") (pintype "bidirectional"))
      (node (ref "SLAVE_SENSOR") (pin "30") (pinfunction "30/PWM_30") (pintype "bidirectional"))
    )
    (net (code "42") (name "IR22") (class "Default")
      (node (ref "IR22") (pin "1") (pinfunction "OUT_1") (pintype "bidirectional"))
      (node (ref "SLAVE_SENSOR") (pin "31") (pinfunction "31/A12/RX4/CS1_31") (pintype "bidirectional"))
    )
    (net (code "43") (name "IR23") (class "Default")
      (node (ref "IR23") (pin "1") (pinfunction "OUT_1") (pintype "bidirectional"))
      (node (ref "SLAVE_SENSOR") (pin "32") (pinfunction "32/A13/TX4/SCK1_32") (pintype "bidirectional"))
    )
    (net (code "44") (name "IR_PWR") (class "Default")
      (node (ref "C38") (pin "1") (pinfunction "1_1") (pintype "passive"))
      (node (ref "C39") (pin "1") (pinfunction "1_1") (pintype "passive"))
      (node (ref "C40") (pin "1") (pinfunction "1_1") (pintype "passive"))
      (node (ref "C41") (pin "1") (pinfunction "1_1") (pintype "passive"))
      (node (ref "C42") (pin "1") (pinfunction "1_1") (pintype "passive"))
      (node (ref "C43") (pin "1") (pinfunction "1_1") (pintype "passive"))
      (node (ref "C44") (pin "1") (pinfunction "1_1") (pintype "passive"))
      (node (ref "C45") (pin "1") (pinfunction "1_1") (pintype "passive"))
      (node (ref "C46") (pin "1") (pinfunction "1_1") (pintype "passive"))
      (node (ref "C47") (pin "1") (pinfunction "1_1") (pintype "passive"))
      (node (ref "C48") (pin "1") (pinfunction "1_1") (pintype "passive"))
      (node (ref "C49") (pin "1") (pinfunction "1_1") (pintype "passive"))
      (node (ref "C50") (pin "1") (pinfunction "1_1") (pintype "passive"))
      (node (ref "C51") (pin "1") (pinfunction "1_1") (pintype "passive"))
      (node (ref "C52") (pin "1") (pinfunction "1_1") (pintype "passive"))
      (node (ref "C53") (pin "1") (pinfunction "1_1") (pintype "passive"))
      (node (ref "C54") (pin "1") (pinfunction "1_1") (pintype "passive"))
      (node (ref "C55") (pin "1") (pinfunction "1_1") (pintype "passive"))
      (node (ref "C56") (pin "1") (pinfunction "1_1") (pintype "passive"))
      (node (ref "C57") (pin "1") (pinfunction "1_1") (pintype "passive"))
      (node (ref "C58") (pin "1") (pinfunction "1_1") (pintype "passive"))
      (node (ref "C59") (pin "1") (pinfunction "1_1") (pintype "passive"))
      (node (ref "C60") (pin "1") (pinfunction "1_1") (pintype "passive"))
      (node (ref "C61") (pin "1") (pinfunction "1_1") (pintype "passive"))
      (node (ref "IR0") (pin "3") (pinfunction "VS_3") (pintype "bidirectional"))
      (node (ref "IR1") (pin "3") (pinfunction "VS_3") (pintype "bidirectional"))
      (node (ref "IR10") (pin "3") (pinfunction "VS_3") (pintype "bidirectional"))
      (node (ref "IR11") (pin "3") (pinfunction "VS_3") (pintype "bidirectional"))
      (node (ref "IR12") (pin "3") (pinfunction "VS_3") (pintype "bidirectional"))
      (node (ref "IR13") (pin "3") (pinfunction "VS_3") (pintype "bidirectional"))
      (node (ref "IR14") (pin "3") (pinfunction "VS_3") (pintype "bidirectional"))
      (node (ref "IR15") (pin "3") (pinfunction "VS_3") (pintype "bidirectional"))
      (node (ref "IR16") (pin "3") (pinfunction "VS_3") (pintype "bidirectional"))
      (node (ref "IR17") (pin "3") (pinfunction "VS_3") (pintype "bidirectional"))
      (node (ref "IR18") (pin "3") (pinfunction "VS_3") (pintype "bidirectional"))
      (node (ref "IR19") (pin "3") (pinfunction "VS_3") (pintype "bidirectional"))
      (node (ref "IR2") (pin "3") (pinfunction "VS_3") (pintype "bidirectional"))
      (node (ref "IR20") (pin "3") (pinfunction "VS_3") (pintype "bidirectional"))
      (node (ref "IR21") (pin "3") (pinfunction "VS_3") (pintype "bidirectional"))
      (node (ref "IR22") (pin "3") (pinfunction "VS_3") (pintype "bidirectional"))
      (node (ref "IR23") (pin "3") (pinfunction "VS_3") (pintype "bidirectional"))
      (node (ref "IR3") (pin "3") (pinfunction "VS_3") (pintype "bidirectional"))
      (node (ref "IR4") (pin "3") (pinfunction "VS_3") (pintype "bidirectional"))
      (node (ref "IR5") (pin "3") (pinfunction "VS_3") (pintype "bidirectional"))
      (node (ref "IR6") (pin "3") (pinfunction "VS_3") (pintype "bidirectional"))
      (node (ref "IR7") (pin "3") (pinfunction "VS_3") (pintype "bidirectional"))
      (node (ref "IR8") (pin "3") (pinfunction "VS_3") (pintype "bidirectional"))
      (node (ref "IR9") (pin "3") (pinfunction "VS_3") (pintype "bidirectional"))
      (node (ref "SLAVE_SENSOR") (pin "43") (pinfunction "43/CS2_43") (pintype "bidirectional"))
      (node (ref "SLAVE_SENSOR") (pin "44") (pinfunction "44/MOSI2_44") (pintype "bidirectional"))
      (node (ref "SLAVE_SENSOR") (pin "45") (pinfunction "45/MISO2_45") (pintype "bidirectional"))
      (node (ref "SLAVE_SENSOR") (pin "47") (pinfunction "47/RX6_47") (pintype "bidirectional"))
      (node (ref "SLAVE_SENSOR") (pin "48") (pinfunction "48/TX6_48") (pintype "bidirectional"))
      (node (ref "SLAVE_SENSOR") (pin "49") (pinfunction "49/A23_49") (pintype "bidirectional"))
      (node (ref "SLAVE_SENSOR") (pin "50") (pinfunction "50/A24_50") (pintype "bidirectional"))
    )
    (net (code "45") (name "LED_A_CTRL") (class "Default")
      (node (ref "R61") (pin "1") (pinfunction "1_1") (pintype "passive"))
      (node (ref "SLAVE_DEBUG") (pin "2") (pinfunction "2/PWM_2") (pintype "bidirectional"))
    )
    (net (code "46") (name "LED_DEBUG1") (class "Default")
      (node (ref "R55") (pin "1") (pinfunction "1_1") (pintype "passive"))
      (node (ref "SLAVE_DEBUG") (pin "4") (pinfunction "4/PWM/CAN0RX/SDA2_4") (pintype "bidirectional"))
    )
    (net (code "47") (name "LED_DEBUG2") (class "Default")
      (node (ref "R56") (pin "1") (pinfunction "1_1") (pintype "passive"))
      (node (ref "SLAVE_DEBUG") (pin "5") (pinfunction "5/PWM_5") (pintype "bidirectional"))
    )
    (net (code "48") (name "LED_DEBUG3") (class "Default")
      (node (ref "R57") (pin "1") (pinfunction "1_1") (pintype "passive"))
      (node (ref "SLAVE_DEBUG") (pin "6") (pinfunction "6/PWM_6") (pintype "bidirectional"))
    )
    (net (code "49") (name "LED_DEBUG4") (class "Default")
      (node (ref "R58") (pin "1") (pinfunction "1_1") (pintype "passive"))
      (node (ref "SLAVE_DEBUG") (pin "7") (pinfunction "7/PWM/RX3_7") (pintype "bidirectional"))
    )
    (net (code "50") (name "LED_DEBUG5") (class "Default")
      (node (ref "R59") (pin "1") (pinfunction "1_1") (pintype "passive"))
      (node (ref "SLAVE_DEBUG") (pin "8") (pinfunction "8/PWM/TX3_8") (pintype "bidirectional"))
    )
    (net (code "51") (name "LED_DEBUG6") (class "Default")
      (node (ref "R60") (pin "1") (pinfunction "1_1") (pintype "passive"))
      (node (ref "SLAVE_DEBUG") (pin "9") (pinfunction "9/PWM/RX2/CS0_9") (pintype "bidirectional"))
    )
    (net (code "52") (name "LED_D_CTRL") (class "Default")
      (node (ref "R62") (pin "1") (pinfunction "1_1") (pintype "passive"))
      (node (ref "SLAVE_DEBUG") (pin "3") (pinfunction "3/PWM/CAN0TX/SCL2_3") (pintype "bidirectional"))
    )
    (net (code "53") (name "LIGHT_GATE_LASER") (class "Default")
      (node (ref "LIGHT_GATE") (pin "3") (pinfunction "3_3") (pintype "passive"))
      (node (ref "MASTER") (pin "21") (pinfunction "21/A7/PWM/CS0_21") (pintype "bidirectional"))
      (node (ref "MASTER") (pin "22") (pinfunction "22/A8/PWM_22") (pintype "bidirectional"))
      (node (ref "MASTER") (pin "23") (pinfunction "23/A9/PWM_23") (pintype "bidirectional"))
    )
    (net (code "54") (name "LIGHT_GATE_OUT") (class "Default")
      (node (ref "LIGHT_GATE") (pin "2") (pinfunction "2_2") (pintype "passive"))
      (node (ref "MASTER") (pin "20") (pinfunction "20/A6/PWM/CS0_20") (pintype "bidirectional"))
    )
    (net (code "55") (name "LS0") (class "Default")
      (node (ref "LS_CONNECTOR") (pin "7") (pinfunction "7_7") (pintype "passive"))
      (node (ref "SLAVE_SENSOR") (pin "DA1") (pinfunction "A22/DAC1_DA1") (pintype "bidirectional"))
    )
    (net (code "56") (name "LS1") (class "Default")
      (node (ref "LS_CONNECTOR") (pin "5") (pinfunction "5_5") (pintype "passive"))
      (node (ref "SLAVE_SENSOR") (pin "15") (pinfunction "15/A1/CS0_15") (pintype "bidirectional"))
    )
    (net (code "57") (name "LS2") (class "Default")
      (node (ref "LS_CONNECTOR") (pin "3") (pinfunction "3_3") (pintype "passive"))
      (node (ref "SLAVE_SENSOR") (pin "16") (pinfunction "16/A2_16") (pintype "bidirectional"))
    )
    (net (code "58") (name "LS3") (class "Default")
      (node (ref "LS_CONNECTOR") (pin "1") (pinfunction "1_1") (pintype "passive"))
      (node (ref "SLAVE_SENSOR") (pin "17") (pinfunction "17/A3_17") (pintype "bidirectional"))
    )
    (net (code "59") (name "LS_MUX") (class "Default")
      (node (ref "LS_CONNECTOR") (pin "15") (pinfunction "15_15") (pintype "passive"))
      (node (ref "SLAVE_SENSOR") (pin "18") (pinfunction "18/A4/SDA0_18") (pintype "bidirectional"))
    )
    (net (code "60") (name "MISO") (class "Default")
      (node (ref "MASTER") (pin "12") (pinfunction "12/MISO0_12") (pintype "bidirectional"))
      (node (ref "SLAVE_DEBUG") (pin "11") (pinfunction "11/MOSI0_11") (pintype "bidirectional"))
      (node (ref "SLAVE_MOTOR") (pin "11") (pinfunction "11/MOSI0_11") (pintype "bidirectional"))
      (node (ref "SLAVE_SENSOR") (pin "11") (pinfunction "11/MOSI0_11") (pintype "bidirectional"))
    )
    (net (code "61") (name "MOSI") (class "Default")
      (node (ref "MASTER") (pin "11") (pinfunction "11/MOSI0_11") (pintype "bidirectional"))
      (node (ref "SLAVE_DEBUG") (pin "12") (pinfunction "12/MISO0_12") (pintype "bidirectional"))
      (node (ref "SLAVE_MOTOR") (pin "12") (pinfunction "12/MISO0_12") (pintype "bidirectional"))
      (node (ref "SLAVE_SENSOR") (pin "12") (pinfunction "12/MISO0_12") (pintype "bidirectional"))
    )
    (net (code "62") (name "MOTOR1_CS") (class "Default")
      (node (ref "C6") (pin "1") (pinfunction "1_1") (pintype "passive"))
      (node (ref "R14") (pin "1") (pinfunction "1_1") (pintype "passive"))
      (node (ref "SLAVE_MOTOR") (pin "16") (pinfunction "16/A2_16") (pintype "bidirectional"))
    )
    (net (code "63") (name "MOTOR1_ENA") (class "Default")
      (node (ref "R10") (pin "2") (pinfunction "2_2") (pintype "passive"))
      (node (ref "SLAVE_MOTOR") (pin "24") (pinfunction "24_24") (pintype "bidirectional"))
    )
    (net (code "64") (name "MOTOR1_ENB") (class "Default")
      (node (ref "R12") (pin "2") (pinfunction "2_2") (pintype "passive"))
      (node (ref "SLAVE_MOTOR") (pin "28") (pinfunction "28_28") (pintype "bidirectional"))
    )
    (net (code "65") (name "MOTOR1_ENCA") (class "Default")
      (node (ref "ENC_L") (pin "3") (pinfunction "3_3") (pintype "passive"))
      (node (ref "SLAVE_MOTOR") (pin "32") (pinfunction "32/A13/TX4/SCK1_32") (pintype "bidirectional"))
    )
    (net (code "66") (name "MOTOR1_ENCB") (class "Default")
      (node (ref "ENC_L") (pin "2") (pinfunction "2_2") (pintype "passive"))
      (node (ref "SLAVE_MOTOR") (pin "33") (pinfunction "33/A14/TX5_33") (pintype "bidirectional"))
    )
    (net (code "67") (name "MOTOR1_INA") (class "Default")
      (node (ref "R7") (pin "1") (pinfunction "1_1") (pintype "passive"))
      (node (ref "SLAVE_MOTOR") (pin "6") (pinfunction "6/PWM_6") (pintype "bidirectional"))
    )
    (net (code "68") (name "MOTOR1_INB") (class "Default")
      (node (ref "R8") (pin "1") (pinfunction "1_1") (pintype "passive"))
      (node (ref "SLAVE_MOTOR") (pin "23") (pinfunction "23/A9/PWM_23") (pintype "bidirectional"))
    )
    (net (code "69") (name "MOTOR1_PWM") (class "Default")
      (node (ref "R9") (pin "1") (pinfunction "1_1") (pintype "passive"))
      (node (ref "SLAVE_MOTOR") (pin "2") (pinfunction "2/PWM_2") (pintype "bidirectional"))
    )
    (net (code "70") (name "MOTOR2_CS") (class "Default")
      (node (ref "C11") (pin "1") (pinfunction "1_1") (pintype "passive"))
      (node (ref "R23") (pin "1") (pinfunction "1_1") (pintype "passive"))
      (node (ref "SLAVE_MOTOR") (pin "17") (pinfunction "17/A3_17") (pintype "bidirectional"))
    )
    (net (code "71") (name "MOTOR2_ENA") (class "Default")
      (node (ref "R19") (pin "2") (pinfunction "2_2") (pintype "passive"))
      (node (ref "SLAVE_MOTOR") (pin "25") (pinfunction "25_25") (pintype "bidirectional"))
    )
    (net (code "72") (name "MOTOR2_ENB") (class "Default")
      (node (ref "R20") (pin "2") (pinfunction "2_2") (pintype "passive"))
      (node (ref "SLAVE_MOTOR") (pin "29") (pinfunction "29/PWM_29") (pintype "bidirectional"))
    )
    (net (code "73") (name "MOTOR2_ENCA") (class "Default")
      (node (ref "ENC_R") (pin "3") (pinfunction "3_3") (pintype "passive"))
      (node (ref "SLAVE_MOTOR") (pin "34") (pinfunction "34/A15/RX5_34") (pintype "bidirectional"))
    )
    (net (code "74") (name "MOTOR2_ENCB") (class "Default")
      (node (ref "ENC_R") (pin "2") (pinfunction "2_2") (pintype "passive"))
      (node (ref "SLAVE_MOTOR") (pin "35") (pinfunction "35/A16/PWM_35") (pintype "bidirectional"))
    )
    (net (code "75") (name "MOTOR2_INA") (class "Default")
      (node (ref "R16") (pin "1") (pinfunction "1_1") (pintype "passive"))
      (node (ref "SLAVE_MOTOR") (pin "7") (pinfunction "7/PWM/RX3_7") (pintype "bidirectional"))
    )
    (net (code "76") (name "MOTOR2_INB") (class "Default")
      (node (ref "R17") (pin "1") (pinfunction "1_1") (pintype "passive"))
      (node (ref "SLAVE_MOTOR") (pin "22") (pinfunction "22/A8/PWM_22") (pintype "bidirectional"))
    )
    (net (code "77") (name "MOTOR2_PWM") (class "Default")
      (node (ref "R18") (pin "1") (pinfunction "1_1") (pintype "passive"))
      (node (ref "SLAVE_MOTOR") (pin "3") (pinfunction "3/PWM/CAN0TX/SCL2_3") (pintype "bidirectional"))
    )
    (net (code "78") (name "MOTOR3_CS") (class "Default")
      (node (ref "C12") (pin "1") (pinfunction "1_1") (pintype "passive"))
      (node (ref "R32") (pin "1") (pinfunction "1_1") (pintype "passive"))
      (node (ref "SLAVE_MOTOR") (pin "18") (pinfunction "18/A4/SDA0_18") (pintype "bidirectional"))
    )
    (net (code "79") (name "MOTOR3_ENA") (class "Default")
      (node (ref "R28") (pin "2") (pinfunction "2_2") (pintype "passive"))
      (node (ref "SLAVE_MOTOR") (pin "26") (pinfunction "26_26") (pintype "bidirectional"))
    )
    (net (code "80") (name "MOTOR3_ENB") (class "Default")
      (node (ref "R29") (pin "2") (pinfunction "2_2") (pintype "passive"))
      (node (ref "SLAVE_MOTOR") (pin "30") (pinfunction "30/PWM_30") (pintype "bidirectional"))
    )
    (net (code "81") (name "MOTOR3_ENCA") (class "Default")
      (node (ref "ENC_BL") (pin "3") (pinfunction "3_3") (pintype "passive"))
      (node (ref "SLAVE_MOTOR") (pin "36") (pinfunction "36/A17/PWM_36") (pintype "bidirectional"))
    )
    (net (code "82") (name "MOTOR3_ENCB") (class "Default")
      (node (ref "ENC_BL") (pin "2") (pinfunction "2_2") (pintype "passive"))
      (node (ref "SLAVE_MOTOR") (pin "37") (pinfunction "37/A18/PWM/SCL1_37") (pintype "bidirectional"))
    )
    (net (code "83") (name "MOTOR3_INA") (class "Default")
      (node (ref "R25") (pin "1") (pinfunction "1_1") (pintype "passive"))
      (node (ref "SLAVE_MOTOR") (pin "8") (pinfunction "8/PWM/TX3_8") (pintype "bidirectional"))
    )
    (net (code "84") (name "MOTOR3_INB") (class "Default")
      (node (ref "R26") (pin "1") (pinfunction "1_1") (pintype "passive"))
      (node (ref "SLAVE_MOTOR") (pin "21") (pinfunction "21/A7/PWM/CS0_21") (pintype "bidirectional"))
    )
    (net (code "85") (name "MOTOR3_PWM") (class "Default")
      (node (ref "R27") (pin "1") (pinfunction "1_1") (pintype "passive"))
      (node (ref "SLAVE_MOTOR") (pin "4") (pinfunction "4/PWM/CAN0RX/SDA2_4") (pintype "bidirectional"))
    )
    (net (code "86") (name "MOTOR4_CS") (class "Default")
      (node (ref "C13") (pin "1") (pinfunction "1_1") (pintype "passive"))
      (node (ref "R41") (pin "1") (pinfunction "1_1") (pintype "passive"))
      (node (ref "SLAVE_MOTOR") (pin "19") (pinfunction "19/A5/SCL0_19") (pintype "bidirectional"))
    )
    (net (code "87") (name "MOTOR4_ENA") (class "Default")
      (node (ref "R37") (pin "2") (pinfunction "2_2") (pintype "passive"))
      (node (ref "SLAVE_MOTOR") (pin "27") (pinfunction "27_27") (pintype "bidirectional"))
    )
    (net (code "88") (name "MOTOR4_ENB") (class "Default")
      (node (ref "R38") (pin "2") (pinfunction "2_2") (pintype "passive"))
      (node (ref "SLAVE_MOTOR") (pin "31") (pinfunction "31/A12/RX4/CS1_31") (pintype "bidirectional"))
    )
    (net (code "89") (name "MOTOR4_ENCA") (class "Default")
      (node (ref "ENC_BR") (pin "3") (pinfunction "3_3") (pintype "passive"))
      (node (ref "SLAVE_MOTOR") (pin "38") (pinfunction "38/A19/PWM/SDA1_38") (pintype "bidirectional"))
    )
    (net (code "90") (name "MOTOR4_ENCB") (class "Default")
      (node (ref "ENC_BR") (pin "2") (pinfunction "2_2") (pintype "passive"))
      (node (ref "SLAVE_MOTOR") (pin "39") (pinfunction "39/A20_39") (pintype "bidirectional"))
    )
    (net (code "91") (name "MOTOR4_INA") (class "Default")
      (node (ref "R34") (pin "1") (pinfunction "1_1") (pintype "passive"))
      (node (ref "SLAVE_MOTOR") (pin "9") (pinfunction "9/PWM/RX2/CS0_9") (pintype "bidirectional"))
    )
    (net (code "92") (name "MOTOR4_INB") (class "Default")
      (node (ref "R35") (pin "1") (pinfunction "1_1") (pintype "passive"))
      (node (ref "SLAVE_MOTOR") (pin "20") (pinfunction "20/A6/PWM/CS0_20") (pintype "bidirectional"))
    )
    (net (code "93") (name "MOTOR4_PWM") (class "Default")
      (node (ref "R36") (pin "1") (pinfunction "1_1") (pintype "passive"))
      (node (ref "SLAVE_MOTOR") (pin "5") (pinfunction "5/PWM_5") (pintype "bidirectional"))
    )
    (net (code "94") (name "MOTOR_PWR") (class "Default")
      (node (ref "C10") (pin "+") (pinfunction "+_+") (pintype "passive"))
      (node (ref "C7") (pin "+") (pinfunction "+_+") (pintype "passive"))
      (node (ref "C8") (pin "+") (pinfunction "+_+") (pintype "passive"))
      (node (ref "C9") (pin "+") (pinfunction "+_+") (pintype "passive"))
      (node (ref "MOTOR_FUSE") (pin "3") (pinfunction "P2_3") (pintype "bidirectional"))
      (node (ref "MOTOR_FUSE") (pin "4") (pinfunction "P2_4") (pintype "bidirectional"))
      (node (ref "P1") (pin "13") (pinfunction "VCC-1_13") (pintype "bidirectional"))
      (node (ref "P1") (pin "24") (pinfunction "VCC-2_24") (pintype "bidirectional"))
      (node (ref "P1") (pin "SLUG1") (pinfunction "VCC-1_SLUG1") (pintype "bidirectional"))
      (node (ref "P2") (pin "13") (pinfunction "VCC-1_13") (pintype "bidirectional"))
      (node (ref "P2") (pin "24") (pinfunction "VCC-2_24") (pintype "bidirectional"))
      (node (ref "P2") (pin "SLUG1") (pinfunction "VCC-1_SLUG1") (pintype "bidirectional"))
      (node (ref "P3") (pin "13") (pinfunction "VCC-1_13") (pintype "bidirectional"))
      (node (ref "P3") (pin "24") (pinfunction "VCC-2_24") (pintype "bidirectional"))
      (node (ref "P3") (pin "SLUG1") (pinfunction "VCC-1_SLUG1") (pintype "bidirectional"))
      (node (ref "P4") (pin "13") (pinfunction "VCC-1_13") (pintype "bidirectional"))
      (node (ref "P4") (pin "24") (pinfunction "VCC-2_24") (pintype "bidirectional"))
      (node (ref "P4") (pin "SLUG1") (pinfunction "VCC-1_SLUG1") (pintype "bidirectional"))
    )
    (net (code "95") (name "MUX_A0") (class "Default")
      (node (ref "LS_CONNECTOR") (pin "4") (pinfunction "4_4") (pintype "passive"))
      (node (ref "SLAVE_SENSOR") (pin "33") (pinfunction "33/A14/TX5_33") (pintype "bidirectional"))
    )
    (net (code "96") (name "MUX_A1") (class "Default")
      (node (ref "LS_CONNECTOR") (pin "2") (pinfunction "2_2") (pintype "passive"))
      (node (ref "SLAVE_SENSOR") (pin "34") (pinfunction "34/A15/RX5_34") (pintype "bidirectional"))
    )
    (net (code "97") (name "MUX_A2") (class "Default")
      (node (ref "LS_CONNECTOR") (pin "6") (pinfunction "6_6") (pintype "passive"))
      (node (ref "SLAVE_SENSOR") (pin "35") (pinfunction "35/A16/PWM_35") (pintype "bidirectional"))
    )
    (net (code "98") (name "MUX_A3") (class "Default")
      (node (ref "LS_CONNECTOR") (pin "8") (pinfunction "8_8") (pintype "passive"))
      (node (ref "SLAVE_SENSOR") (pin "36") (pinfunction "36/A17/PWM_36") (pintype "bidirectional"))
    )
    (net (code "99") (name "MUX_A4") (class "Default")
      (node (ref "LS_CONNECTOR") (pin "10") (pinfunction "10_10") (pintype "passive"))
      (node (ref "SLAVE_SENSOR") (pin "37") (pinfunction "37/A18/PWM/SCL1_37") (pintype "bidirectional"))
    )
    (net (code "100") (name "MUX_CS") (class "Default")
      (node (ref "LS_CONNECTOR") (pin "12") (pinfunction "12_12") (pintype "passive"))
      (node (ref "SLAVE_SENSOR") (pin "38") (pinfunction "38/A19/PWM/SDA1_38") (pintype "bidirectional"))
    )
    (net (code "101") (name "MUX_EN") (class "Default")
      (node (ref "LS_CONNECTOR") (pin "16") (pinfunction "16_16") (pintype "passive"))
      (node (ref "SLAVE_SENSOR") (pin "46") (pinfunction "46/SCK2_46") (pintype "bidirectional"))
    )
    (net (code "102") (name "MUX_WR") (class "Default")
      (node (ref "LS_CONNECTOR") (pin "14") (pinfunction "14_14") (pintype "passive"))
      (node (ref "SLAVE_SENSOR") (pin "39") (pinfunction "39/A20_39") (pintype "bidirectional"))
    )
    (net (code "103") (name "Net-(3.3V_ON-PadA)") (class "Default")
      (node (ref "3.3V_ON") (pin "A") (pinfunction "A_A") (pintype "passive"))
      (node (ref "R4") (pin "2") (pinfunction "2_2") (pintype "passive"))
    )
    (net (code "104") (name "Net-(5V_ON-PadA)") (class "Default")
      (node (ref "5V_ON") (pin "A") (pinfunction "A_A") (pintype "passive"))
      (node (ref "R3") (pin "2") (pinfunction "2_2") (pintype "passive"))
    )
    (net (code "105") (name "Net-(BT_DEBUG-PadPIO1)") (class "Default")
      (node (ref "BT_DEBUG") (pin "PIO1") (pinfunction "PIO1_PIO1") (pintype "bidirectional"))
      (node (ref "R6") (pin "1") (pinfunction "1_1") (pintype "passive"))
    )
    (net (code "106") (name "Net-(BT_DEBUG_LED-PadA)") (class "Default")
      (node (ref "BT_DEBUG_LED") (pin "A") (pinfunction "A_A") (pintype "passive"))
      (node (ref "R6") (pin "2") (pinfunction "2_2") (pintype "passive"))
    )
    (net (code "107") (name "Net-(BT_IRC-PadPIO1)") (class "Default")
      (node (ref "BT_IRC") (pin "PIO1") (pinfunction "PIO1_PIO1") (pintype "bidirectional"))
      (node (ref "R5") (pin "1") (pinfunction "1_1") (pintype "passive"))
    )
    (net (code "108") (name "Net-(BT_IRC_LED-PadA)") (class "Default")
      (node (ref "BT_IRC_LED") (pin "A") (pinfunction "A_A") (pintype "passive"))
      (node (ref "R5") (pin "2") (pinfunction "2_2") (pintype "passive"))
    )
    (net (code "109") (name "Net-(D1-ANODE-PadA)") (class "Default")
      (node (ref "D1") (pin "A") (pinfunction "ANODE_A") (pintype "bidirectional"))
      (node (ref "D1") (pin "NOP") (pinfunction "ANODE_NOP") (pintype "bidirectional"))
      (node (ref "PWR_IN") (pin "2") (pinfunction "2_2") (pintype "passive"))
      (node (ref "R1") (pin "1") (pinfunction "1_1") (pintype "passive"))
    )
    (net (code "110") (name "Net-(D1-CATHODE)") (class "Default")
      (node (ref "C1") (pin "+") (pinfunction "+_+") (pintype "passive"))
      (node (ref "D1") (pin "C") (pinfunction "CATHODE_C") (pintype "bidirectional"))
      (node (ref "LOGIC_SWITCH") (pin "2") (pinfunction "2_2") (pintype "passive"))
      (node (ref "MOTOR_SWITCH") (pin "1") (pinfunction "1_1") (pintype "passive"))
    )
    (net (code "111") (name "Net-(D3-DIN)") (class "Default")
      (node (ref "D3") (pin "4") (pinfunction "DIN_4") (pintype "input"))
      (node (ref "R67") (pin "2") (pinfunction "2_2") (pintype "passive"))
    )
    (net (code "112") (name "Net-(D3-DOUT)") (class "Default")
      (node (ref "D3") (pin "2") (pinfunction "DOUT_2") (pintype "output"))
      (node (ref "D4") (pin "4") (pinfunction "DIN_4") (pintype "input"))
    )
    (net (code "113") (name "Net-(D4-DOUT)") (class "Default")
      (node (ref "D4") (pin "2") (pinfunction "DOUT_2") (pintype "output"))
      (node (ref "D5") (pin "4") (pinfunction "DIN_4") (pintype "input"))
    )
    (net (code "114") (name "Net-(D5-DOUT)") (class "Default")
      (node (ref "D5") (pin "2") (pinfunction "DOUT_2") (pintype "output"))
      (node (ref "D6") (pin "4") (pinfunction "DIN_4") (pintype "input"))
    )
    (net (code "115") (name "Net-(D6-DOUT)") (class "Default")
      (node (ref "D6") (pin "2") (pinfunction "DOUT_2") (pintype "output"))
      (node (ref "D7") (pin "4") (pinfunction "DIN_4") (pintype "input"))
    )
    (net (code "116") (name "Net-(D7-DOUT)") (class "Default")
      (node (ref "D7") (pin "2") (pinfunction "DOUT_2") (pintype "output"))
      (node (ref "D8") (pin "4") (pinfunction "DIN_4") (pintype "input"))
    )
    (net (code "117") (name "Net-(D8-DOUT)") (class "Default")
      (node (ref "D8") (pin "2") (pinfunction "DOUT_2") (pintype "output"))
      (node (ref "D9") (pin "4") (pinfunction "DIN_4") (pintype "input"))
    )
    (net (code "118") (name "Net-(D10-DIN)") (class "Default")
      (node (ref "D10") (pin "4") (pinfunction "DIN_4") (pintype "input"))
      (node (ref "D9") (pin "2") (pinfunction "DOUT_2") (pintype "output"))
    )
    (net (code "119") (name "Net-(D10-DOUT)") (class "Default")
      (node (ref "D10") (pin "2") (pinfunction "DOUT_2") (pintype "output"))
      (node (ref "D11") (pin "4") (pinfunction "DIN_4") (pintype "input"))
    )
    (net (code "120") (name "Net-(D11-DOUT)") (class "Default")
      (node (ref "D11") (pin "2") (pinfunction "DOUT_2") (pintype "output"))
      (node (ref "D12") (pin "4") (pinfunction "DIN_4") (pintype "input"))
    )
    (net (code "121") (name "Net-(D12-DOUT)") (class "Default")
      (node (ref "D12") (pin "2") (pinfunction "DOUT_2") (pintype "output"))
      (node (ref "D13") (pin "4") (pinfunction "DIN_4") (pintype "input"))
    )
    (net (code "122") (name "Net-(D13-DOUT)") (class "Default")
      (node (ref "D13") (pin "2") (pinfunction "DOUT_2") (pintype "output"))
      (node (ref "D14") (pin "4") (pinfunction "DIN_4") (pintype "input"))
    )
    (net (code "123") (name "Net-(LEDA1-PadA)") (class "Default")
      (node (ref "LEDA1") (pin "A") (pinfunction "A_A") (pintype "passive"))
      (node (ref "R43") (pin "2") (pinfunction "2_2") (pintype "passive"))
    )
    (net (code "124") (name "Net-(LEDA2-PadA)") (class "Default")
      (node (ref "LEDA2") (pin "A") (pinfunction "A_A") (pintype "passive"))
      (node (ref "R44") (pin "2") (pinfunction "2_2") (pintype "passive"))
    )
    (net (code "125") (name "Net-(LEDA3-PadA)") (class "Default")
      (node (ref "LEDA3") (pin "A") (pinfunction "A_A") (pintype "passive"))
      (node (ref "R45") (pin "2") (pinfunction "2_2") (pintype "passive"))
    )
    (net (code "126") (name "Net-(LEDA4-PadA)") (class "Default")
      (node (ref "LEDA4") (pin "A") (pinfunction "A_A") (pintype "passive"))
      (node (ref "R46") (pin "2") (pinfunction "2_2") (pintype "passive"))
    )
    (net (code "127") (name "Net-(LEDA5-PadA)") (class "Default")
      (node (ref "LEDA5") (pin "A") (pinfunction "A_A") (pintype "passive"))
      (node (ref "R47") (pin "2") (pinfunction "2_2") (pintype "passive"))
    )
    (net (code "128") (name "Net-(LEDA6-PadA)") (class "Default")
      (node (ref "LEDA6") (pin "A") (pinfunction "A_A") (pintype "passive"))
      (node (ref "R48") (pin "2") (pinfunction "2_2") (pintype "passive"))
    )
    (net (code "129") (name "Net-(LEDD1-PadA)") (class "Default")
      (node (ref "LEDD1") (pin "A") (pinfunction "A_A") (pintype "passive"))
      (node (ref "R49") (pin "2") (pinfunction "2_2") (pintype "passive"))
    )
    (net (code "130") (name "Net-(LEDD2-PadA)") (class "Default")
      (node (ref "LEDD2") (pin "A") (pinfunction "A_A") (pintype "passive"))
      (node (ref "R50") (pin "2") (pinfunction "2_2") (pintype "passive"))
    )
    (net (code "131") (name "Net-(LEDD3-PadA)") (class "Default")
      (node (ref "LEDD3") (pin "A") (pinfunction "A_A") (pintype "passive"))
      (node (ref "R51") (pin "2") (pinfunction "2_2") (pintype "passive"))
    )
    (net (code "132") (name "Net-(LEDD4-PadA)") (class "Default")
      (node (ref "LEDD4") (pin "A") (pinfunction "A_A") (pintype "passive"))
      (node (ref "R52") (pin "2") (pinfunction "2_2") (pintype "passive"))
    )
    (net (code "133") (name "Net-(LEDD5-PadA)") (class "Default")
      (node (ref "LEDD5") (pin "A") (pinfunction "A_A") (pintype "passive"))
      (node (ref "R53") (pin "2") (pinfunction "2_2") (pintype "passive"))
    )
    (net (code "134") (name "Net-(LEDD6-PadA)") (class "Default")
      (node (ref "LEDD6") (pin "A") (pinfunction "A_A") (pintype "passive"))
      (node (ref "R54") (pin "2") (pinfunction "2_2") (pintype "passive"))
    )
    (net (code "135") (name "Net-(LED_DEBUG1-PadA)") (class "Default")
      (node (ref "LED_DEBUG1") (pin "A") (pinfunction "A_A") (pintype "passive"))
      (node (ref "R55") (pin "2") (pinfunction "2_2") (pintype "passive"))
    )
    (net (code "136") (name "Net-(LED_DEBUG2-PadA)") (class "Default")
      (node (ref "LED_DEBUG2") (pin "A") (pinfunction "A_A") (pintype "passive"))
      (node (ref "R56") (pin "2") (pinfunction "2_2") (pintype "passive"))
    )
    (net (code "137") (name "Net-(LED_DEBUG3-PadA)") (class "Default")
      (node (ref "LED_DEBUG3") (pin "A") (pinfunction "A_A") (pintype "passive"))
      (node (ref "R57") (pin "2") (pinfunction "2_2") (pintype "passive"))
    )
    (net (code "138") (name "Net-(LED_DEBUG4-PadA)") (class "Default")
      (node (ref "LED_DEBUG4") (pin "A") (pinfunction "A_A") (pintype "passive"))
      (node (ref "R58") (pin "2") (pinfunction "2_2") (pintype "passive"))
    )
    (net (code "139") (name "Net-(LED_DEBUG5-PadA)") (class "Default")
      (node (ref "LED_DEBUG5") (pin "A") (pinfunction "A_A") (pintype "passive"))
      (node (ref "R59") (pin "2") (pinfunction "2_2") (pintype "passive"))
    )
    (net (code "140") (name "Net-(LED_DEBUG6-PadA)") (class "Default")
      (node (ref "LED_DEBUG6") (pin "A") (pinfunction "A_A") (pintype "passive"))
      (node (ref "R60") (pin "2") (pinfunction "2_2") (pintype "passive"))
    )
    (net (code "141") (name "Net-(LOGIC_FUSE-P1-Pad1)") (class "Default")
      (node (ref "LOGIC_FUSE") (pin "1") (pinfunction "P1_1") (pintype "bidirectional"))
      (node (ref "LOGIC_FUSE") (pin "2") (pinfunction "P1_2") (pintype "bidirectional"))
      (node (ref "LOGIC_SWITCH") (pin "1") (pinfunction "1_1") (pintype "passive"))
    )
    (net (code "142") (name "Net-(MOTOR_FUSE-P1-Pad1)") (class "Default")
      (node (ref "MOTOR_FUSE") (pin "1") (pinfunction "P1_1") (pintype "bidirectional"))
      (node (ref "MOTOR_FUSE") (pin "2") (pinfunction "P1_2") (pintype "bidirectional"))
      (node (ref "MOTOR_SWITCH") (pin "2") (pinfunction "2_2") (pintype "passive"))
    )
    (net (code "143") (name "Net-(P1-CS)") (class "Default")
      (node (ref "P1") (pin "19") (pinfunction "CS_19") (pintype "bidirectional"))
      (node (ref "R14") (pin "2") (pinfunction "2_2") (pintype "passive"))
      (node (ref "R15") (pin "1") (pinfunction "1_1") (pintype "passive"))
    )
    (net (code "144") (name "Net-(P1-EN-A)") (class "Default")
      (node (ref "P1") (pin "16") (pinfunction "EN-A_16") (pintype "bidirectional"))
      (node (ref "R10") (pin "1") (pinfunction "1_1") (pintype "passive"))
      (node (ref "R13") (pin "1") (pinfunction "1_1") (pintype "passive"))
    )
    (net (code "145") (name "Net-(P1-EN-B)") (class "Default")
      (node (ref "P1") (pin "21") (pinfunction "EN-B_21") (pintype "bidirectional"))
      (node (ref "R11") (pin "1") (pinfunction "1_1") (pintype "passive"))
      (node (ref "R12") (pin "1") (pinfunction "1_1") (pintype "passive"))
    )
    (net (code "146") (name "Net-(P1-INA)") (class "Default")
      (node (ref "P1") (pin "15") (pinfunction "INA_15") (pintype "bidirectional"))
      (node (ref "R7") (pin "2") (pinfunction "2_2") (pintype "passive"))
    )
    (net (code "147") (name "Net-(P1-INB)") (class "Default")
      (node (ref "P1") (pin "22") (pinfunction "INB_22") (pintype "bidirectional"))
      (node (ref "R8") (pin "2") (pinfunction "2_2") (pintype "passive"))
    )
    (net (code "148") (name "Net-(P1-OUT.A-2)") (class "Default")
      (node (ref "C20") (pin "1") (pinfunction "1_1") (pintype "passive"))
      (node (ref "M_LEFT") (pin "1") (pinfunction "1_1") (pintype "passive"))
      (node (ref "P1") (pin "10") (pinfunction "OUT.A-4_10") (pintype "bidirectional"))
      (node (ref "P1") (pin "11") (pinfunction "OUT.A-5_11") (pintype "bidirectional"))
      (node (ref "P1") (pin "12") (pinfunction "OUT.A-6_12") (pintype "bidirectional"))
      (node (ref "P1") (pin "14") (pinfunction "OUT.A-7_14") (pintype "bidirectional"))
      (node (ref "P1") (pin "2") (pinfunction "OUT.A-1_2") (pintype "bidirectional"))
      (node (ref "P1") (pin "8") (pinfunction "OUT.A-2_8") (pintype "bidirectional"))
      (node (ref "P1") (pin "9") (pinfunction "OUT.A-3_9") (pintype "bidirectional"))
      (node (ref "P1") (pin "SLUG2") (pinfunction "OUT.A-1_SLUG2") (pintype "bidirectional"))
    )
    (net (code "149") (name "Net-(P1-OUT.B-1)") (class "Default")
      (node (ref "C20") (pin "2") (pinfunction "2_2") (pintype "passive"))
      (node (ref "M_LEFT") (pin "2") (pinfunction "2_2") (pintype "passive"))
      (node (ref "P1") (pin "23") (pinfunction "OUT.B-1_23") (pintype "bidirectional"))
      (node (ref "P1") (pin "25") (pinfunction "OUT.B-2_25") (pintype "bidirectional"))
      (node (ref "P1") (pin "26") (pinfunction "OUT.B-3_26") (pintype "bidirectional"))
      (node (ref "P1") (pin "27") (pinfunction "OUT.B-4_27") (pintype "bidirectional"))
      (node (ref "P1") (pin "28") (pinfunction "OUT.B-5_28") (pintype "bidirectional"))
      (node (ref "P1") (pin "29") (pinfunction "OUT.B-6_29") (pintype "bidirectional"))
      (node (ref "P1") (pin "35") (pinfunction "OUT.B-7_35") (pintype "bidirectional"))
      (node (ref "P1") (pin "SLUG3") (pinfunction "OUT.B-7_SLUG3") (pintype "bidirectional"))
    )
    (net (code "150") (name "Net-(P1-PWM)") (class "Default")
      (node (ref "P1") (pin "17") (pinfunction "PWM_17") (pintype "bidirectional"))
      (node (ref "R9") (pin "2") (pinfunction "2_2") (pintype "passive"))
    )
    (net (code "151") (name "Net-(P2-CS)") (class "Default")
      (node (ref "P2") (pin "19") (pinfunction "CS_19") (pintype "bidirectional"))
      (node (ref "R23") (pin "2") (pinfunction "2_2") (pintype "passive"))
      (node (ref "R24") (pin "1") (pinfunction "1_1") (pintype "passive"))
    )
    (net (code "152") (name "Net-(P2-EN-A)") (class "Default")
      (node (ref "P2") (pin "16") (pinfunction "EN-A_16") (pintype "bidirectional"))
      (node (ref "R19") (pin "1") (pinfunction "1_1") (pintype "passive"))
      (node (ref "R22") (pin "1") (pinfunction "1_1") (pintype "passive"))
    )
    (net (code "153") (name "Net-(P2-EN-B)") (class "Default")
      (node (ref "P2") (pin "21") (pinfunction "EN-B_21") (pintype "bidirectional"))
      (node (ref "R20") (pin "1") (pinfunction "1_1") (pintype "passive"))
      (node (ref "R21") (pin "1") (pinfunction "1_1") (pintype "passive"))
    )
    (net (code "154") (name "Net-(P2-INA)") (class "Default")
      (node (ref "P2") (pin "15") (pinfunction "INA_15") (pintype "bidirectional"))
      (node (ref "R16") (pin "2") (pinfunction "2_2") (pintype "passive"))
    )
    (net (code "155") (name "Net-(P2-INB)") (class "Default")
      (node (ref "P2") (pin "22") (pinfunction "INB_22") (pintype "bidirectional"))
      (node (ref "R17") (pin "2") (pinfunction "2_2") (pintype "passive"))
    )
    (net (code "156") (name "Net-(P2-OUT.A-2)") (class "Default")
      (node (ref "C21") (pin "1") (pinfunction "1_1") (pintype "passive"))
      (node (ref "M_RIGHT") (pin "1") (pinfunction "1_1") (pintype "passive"))
      (node (ref "P2") (pin "10") (pinfunction "OUT.A-4_10") (pintype "bidirectional"))
      (node (ref "P2") (pin "11") (pinfunction "OUT.A-5_11") (pintype "bidirectional"))
      (node (ref "P2") (pin "12") (pinfunction "OUT.A-6_12") (pintype "bidirectional"))
      (node (ref "P2") (pin "14") (pinfunction "OUT.A-7_14") (pintype "bidirectional"))
      (node (ref "P2") (pin "2") (pinfunction "OUT.A-1_2") (pintype "bidirectional"))
      (node (ref "P2") (pin "8") (pinfunction "OUT.A-2_8") (pintype "bidirectional"))
      (node (ref "P2") (pin "9") (pinfunction "OUT.A-3_9") (pintype "bidirectional"))
      (node (ref "P2") (pin "SLUG2") (pinfunction "OUT.A-1_SLUG2") (pintype "bidirectional"))
    )
    (net (code "157") (name "Net-(P2-OUT.B-1)") (class "Default")
      (node (ref "C21") (pin "2") (pinfunction "2_2") (pintype "passive"))
      (node (ref "M_RIGHT") (pin "2") (pinfunction "2_2") (pintype "passive"))
      (node (ref "P2") (pin "23") (pinfunction "OUT.B-1_23") (pintype "bidirectional"))
      (node (ref "P2") (pin "25") (pinfunction "OUT.B-2_25") (pintype "bidirectional"))
      (node (ref "P2") (pin "26") (pinfunction "OUT.B-3_26") (pintype "bidirectional"))
      (node (ref "P2") (pin "27") (pinfunction "OUT.B-4_27") (pintype "bidirectional"))
      (node (ref "P2") (pin "28") (pinfunction "OUT.B-5_28") (pintype "bidirectional"))
      (node (ref "P2") (pin "29") (pinfunction "OUT.B-6_29") (pintype "bidirectional"))
      (node (ref "P2") (pin "35") (pinfunction "OUT.B-7_35") (pintype "bidirectional"))
      (node (ref "P2") (pin "SLUG3") (pinfunction "OUT.B-7_SLUG3") (pintype "bidirectional"))
    )
    (net (code "158") (name "Net-(P2-PWM)") (class "Default")
      (node (ref "P2") (pin "17") (pinfunction "PWM_17") (pintype "bidirectional"))
      (node (ref "R18") (pin "2") (pinfunction "2_2") (pintype "passive"))
    )
    (net (code "159") (name "Net-(P3-CS)") (class "Default")
      (node (ref "P3") (pin "19") (pinfunction "CS_19") (pintype "bidirectional"))
      (node (ref "R32") (pin "2") (pinfunction "2_2") (pintype "passive"))
      (node (ref "R33") (pin "1") (pinfunction "1_1") (pintype "passive"))
    )
    (net (code "160") (name "Net-(P3-EN-A)") (class "Default")
      (node (ref "P3") (pin "16") (pinfunction "EN-A_16") (pintype "bidirectional"))
      (node (ref "R28") (pin "1") (pinfunction "1_1") (pintype "passive"))
      (node (ref "R31") (pin "1") (pinfunction "1_1") (pintype "passive"))
    )
    (net (code "161") (name "Net-(P3-EN-B)") (class "Default")
      (node (ref "P3") (pin "21") (pinfunction "EN-B_21") (pintype "bidirectional"))
      (node (ref "R29") (pin "1") (pinfunction "1_1") (pintype "passive"))
      (node (ref "R30") (pin "1") (pinfunction "1_1") (pintype "passive"))
    )
    (net (code "162") (name "Net-(P3-INA)") (class "Default")
      (node (ref "P3") (pin "15") (pinfunction "INA_15") (pintype "bidirectional"))
      (node (ref "R25") (pin "2") (pinfunction "2_2") (pintype "passive"))
    )
    (net (code "163") (name "Net-(P3-INB)") (class "Default")
      (node (ref "P3") (pin "22") (pinfunction "INB_22") (pintype "bidirectional"))
      (node (ref "R26") (pin "2") (pinfunction "2_2") (pintype "passive"))
    )
    (net (code "164") (name "Net-(P3-OUT.A-2)") (class "Default")
      (node (ref "C23") (pin "1") (pinfunction "1_1") (pintype "passive"))
      (node (ref "M_BACK_LEFT") (pin "1") (pinfunction "1_1") (pintype "passive"))
      (node (ref "P3") (pin "10") (pinfunction "OUT.A-4_10") (pintype "bidirectional"))
      (node (ref "P3") (pin "11") (pinfunction "OUT.A-5_11") (pintype "bidirectional"))
      (node (ref "P3") (pin "12") (pinfunction "OUT.A-6_12") (pintype "bidirectional"))
      (node (ref "P3") (pin "14") (pinfunction "OUT.A-7_14") (pintype "bidirectional"))
      (node (ref "P3") (pin "2") (pinfunction "OUT.A-1_2") (pintype "bidirectional"))
      (node (ref "P3") (pin "8") (pinfunction "OUT.A-2_8") (pintype "bidirectional"))
      (node (ref "P3") (pin "9") (pinfunction "OUT.A-3_9") (pintype "bidirectional"))
      (node (ref "P3") (pin "SLUG2") (pinfunction "OUT.A-1_SLUG2") (pintype "bidirectional"))
    )
    (net (code "165") (name "Net-(P3-OUT.B-1)") (class "Default")
      (node (ref "C23") (pin "2") (pinfunction "2_2") (pintype "passive"))
      (node (ref "M_BACK_LEFT") (pin "2") (pinfunction "2_2") (pintype "passive"))
      (node (ref "P3") (pin "23") (pinfunction "OUT.B-1_23") (pintype "bidirectional"))
      (node (ref "P3") (pin "25") (pinfunction "OUT.B-2_25") (pintype "bidirectional"))
      (node (ref "P3") (pin "26") (pinfunction "OUT.B-3_26") (pintype "bidirectional"))
      (node (ref "P3") (pin "27") (pinfunction "OUT.B-4_27") (pintype "bidirectional"))
      (node (ref "P3") (pin "28") (pinfunction "OUT.B-5_28") (pintype "bidirectional"))
      (node (ref "P3") (pin "29") (pinfunction "OUT.B-6_29") (pintype "bidirectional"))
      (node (ref "P3") (pin "35") (pinfunction "OUT.B-7_35") (pintype "bidirectional"))
      (node (ref "P3") (pin "SLUG3") (pinfunction "OUT.B-7_SLUG3") (pintype "bidirectional"))
    )
    (net (code "166") (name "Net-(P3-PWM)") (class "Default")
      (node (ref "P3") (pin "17") (pinfunction "PWM_17") (pintype "bidirectional"))
      (node (ref "R27") (pin "2") (pinfunction "2_2") (pintype "passive"))
    )
    (net (code "167") (name "Net-(P4-CS)") (class "Default")
      (node (ref "P4") (pin "19") (pinfunction "CS_19") (pintype "bidirectional"))
      (node (ref "R41") (pin "2") (pinfunction "2_2") (pintype "passive"))
      (node (ref "R42") (pin "1") (pinfunction "1_1") (pintype "passive"))
    )
    (net (code "168") (name "Net-(P4-EN-A)") (class "Default")
      (node (ref "P4") (pin "16") (pinfunction "EN-A_16") (pintype "bidirectional"))
      (node (ref "R37") (pin "1") (pinfunction "1_1") (pintype "passive"))
      (node (ref "R40") (pin "1") (pinfunction "1_1") (pintype "passive"))
    )
    (net (code "169") (name "Net-(P4-EN-B)") (class "Default")
      (node (ref "P4") (pin "21") (pinfunction "EN-B_21") (pintype "bidirectional"))
      (node (ref "R38") (pin "1") (pinfunction "1_1") (pintype "passive"))
      (node (ref "R39") (pin "1") (pinfunction "1_1") (pintype "passive"))
    )
    (net (code "170") (name "Net-(P4-INA)") (class "Default")
      (node (ref "P4") (pin "15") (pinfunction "INA_15") (pintype "bidirectional"))
      (node (ref "R34") (pin "2") (pinfunction "2_2") (pintype "passive"))
    )
    (net (code "171") (name "Net-(P4-INB)") (class "Default")
      (node (ref "P4") (pin "22") (pinfunction "INB_22") (pintype "bidirectional"))
      (node (ref "R35") (pin "2") (pinfunction "2_2") (pintype "passive"))
    )
    (net (code "172") (name "Net-(P4-OUT.A-2)") (class "Default")
      (node (ref "C22") (pin "1") (pinfunction "1_1") (pintype "passive"))
      (node (ref "M_BACK_RIGHT") (pin "1") (pinfunction "1_1") (pintype "passive"))
      (node (ref "P4") (pin "10") (pinfunction "OUT.A-4_10") (pintype "bidirectional"))
      (node (ref "P4") (pin "11") (pinfunction "OUT.A-5_11") (pintype "bidirectional"))
      (node (ref "P4") (pin "12") (pinfunction "OUT.A-6_12") (pintype "bidirectional"))
      (node (ref "P4") (pin "14") (pinfunction "OUT.A-7_14") (pintype "bidirectional"))
      (node (ref "P4") (pin "2") (pinfunction "OUT.A-1_2") (pintype "bidirectional"))
      (node (ref "P4") (pin "8") (pinfunction "OUT.A-2_8") (pintype "bidirectional"))
      (node (ref "P4") (pin "9") (pinfunction "OUT.A-3_9") (pintype "bidirectional"))
      (node (ref "P4") (pin "SLUG2") (pinfunction "OUT.A-1_SLUG2") (pintype "bidirectional"))
    )
    (net (code "173") (name "Net-(P4-OUT.B-1)") (class "Default")
      (node (ref "C22") (pin "2") (pinfunction "2_2") (pintype "passive"))
      (node (ref "M_BACK_RIGHT") (pin "2") (pinfunction "2_2") (pintype "passive"))
      (node (ref "P4") (pin "23") (pinfunction "OUT.B-1_23") (pintype "bidirectional"))
      (node (ref "P4") (pin "25") (pinfunction "OUT.B-2_25") (pintype "bidirectional"))
      (node (ref "P4") (pin "26") (pinfunction "OUT.B-3_26") (pintype "bidirectional"))
      (node (ref "P4") (pin "27") (pinfunction "OUT.B-4_27") (pintype "bidirectional"))
      (node (ref "P4") (pin "28") (pinfunction "OUT.B-5_28") (pintype "bidirectional"))
      (node (ref "P4") (pin "29") (pinfunction "OUT.B-6_29") (pintype "bidirectional"))
      (node (ref "P4") (pin "35") (pinfunction "OUT.B-7_35") (pintype "bidirectional"))
      (node (ref "P4") (pin "SLUG3") (pinfunction "OUT.B-7_SLUG3") (pintype "bidirectional"))
    )
    (net (code "174") (name "Net-(P4-PWM)") (class "Default")
      (node (ref "P4") (pin "17") (pinfunction "PWM_17") (pintype "bidirectional"))
      (node (ref "R36") (pin "2") (pinfunction "2_2") (pintype "passive"))
    )
    (net (code "175") (name "Net-(Q1-D)") (class "Default")
      (node (ref "Q1") (pin "3") (pinfunction "D_3") (pintype "passive"))
      (node (ref "R67") (pin "1") (pinfunction "1_1") (pintype "passive"))
      (node (ref "R68") (pin "2") (pinfunction "2_2") (pintype "passive"))
    )
    (net (code "176") (name "Net-(Q2-B)") (class "Default")
      (node (ref "Q2") (pin "1") (pinfunction "B_1") (pintype "passive"))
      (node (ref "R61") (pin "2") (pinfunction "2_2") (pintype "passive"))
    )
    (net (code "177") (name "Net-(Q2-C)") (class "Default")
      (node (ref "LEDA1") (pin "C") (pinfunction "C_C") (pintype "passive"))
      (node (ref "LEDA2") (pin "C") (pinfunction "C_C") (pintype "passive"))
      (node (ref "LEDA3") (pin "C") (pinfunction "C_C") (pintype "passive"))
      (node (ref "LEDA4") (pin "C") (pinfunction "C_C") (pintype "passive"))
      (node (ref "LEDA5") (pin "C") (pinfunction "C_C") (pintype "passive"))
      (node (ref "LEDA6") (pin "C") (pinfunction "C_C") (pintype "passive"))
      (node (ref "Q2") (pin "3") (pinfunction "C_3") (pintype "passive"))
    )
    (net (code "178") (name "Net-(Q3-B)") (class "Default")
      (node (ref "Q3") (pin "1") (pinfunction "B_1") (pintype "passive"))
      (node (ref "R62") (pin "2") (pinfunction "2_2") (pintype "passive"))
    )
    (net (code "179") (name "Net-(Q3-C)") (class "Default")
      (node (ref "LEDD1") (pin "C") (pinfunction "C_C") (pintype "passive"))
      (node (ref "LEDD2") (pin "C") (pinfunction "C_C") (pintype "passive"))
      (node (ref "LEDD3") (pin "C") (pinfunction "C_C") (pintype "passive"))
      (node (ref "LEDD4") (pin "C") (pinfunction "C_C") (pintype "passive"))
      (node (ref "LEDD5") (pin "C") (pinfunction "C_C") (pintype "passive"))
      (node (ref "LEDD6") (pin "C") (pinfunction "C_C") (pintype "passive"))
      (node (ref "Q3") (pin "3") (pinfunction "C_3") (pintype "passive"))
    )
    (net (code "180") (name "Net-(VREG-3.3-VI)") (class "Default")
      (node (ref "C4") (pin "1") (pinfunction "1_1") (pintype "passive"))
      (node (ref "D2") (pin "C") (pinfunction "C_C") (pintype "passive"))
      (node (ref "VREG-3.3") (pin "3") (pinfunction "VI_3") (pintype "input"))
    )
    (net (code "181") (name "Net-(VREG-5-VIN)") (class "Default")
      (node (ref "C2") (pin "1") (pinfunction "1_1") (pintype "passive"))
      (node (ref "LOGIC_FUSE") (pin "3") (pinfunction "P2_3") (pintype "bidirectional"))
      (node (ref "LOGIC_FUSE") (pin "4") (pinfunction "P2_4") (pintype "bidirectional"))
      (node (ref "VREG-5") (pin "1") (pinfunction "VIN_1") (pintype "bidirectional"))
    )
    (net (code "182") (name "RGB_LED_DATA") (class "Default")
      (node (ref "Q1") (pin "2") (pinfunction "S_2") (pintype "passive"))
      (node (ref "R69") (pin "2") (pinfunction "2_2") (pintype "passive"))
      (node (ref "SLAVE_DEBUG") (pin "23") (pinfunction "23/A9/PWM_23") (pintype "bidirectional"))
    )
    (net (code "183") (name "SCK") (class "Default")
      (node (ref "MASTER") (pin "14") (pinfunction "14/A0/PWM_14") (pintype "bidirectional"))
      (node (ref "SLAVE_DEBUG") (pin "14") (pinfunction "14/A0/PWM_14") (pintype "bidirectional"))
      (node (ref "SLAVE_MOTOR") (pin "14") (pinfunction "14/A0/PWM_14") (pintype "bidirectional"))
      (node (ref "SLAVE_SENSOR") (pin "14") (pinfunction "14/A0/PWM_14") (pintype "bidirectional"))
    )
    (net (code "184") (name "SCREEN_CS") (class "Default")
      (node (ref "SCREEN") (pin "CS_2") (pinfunction "CS_2_CS_2") (pintype "bidirectional"))
      (node (ref "SLAVE_DEBUG") (pin "22") (pinfunction "22/A8/PWM_22") (pintype "bidirectional"))
    )
    (net (code "185") (name "SCREEN_C{slash}D") (class "Default")
      (node (ref "SCREEN") (pin "C/D") (pinfunction "C/D_C/D") (pintype "bidirectional"))
      (node (ref "SLAVE_DEBUG") (pin "21") (pinfunction "21/A7/PWM/CS0_21") (pintype "bidirectional"))
    )
    (net (code "186") (name "SCREEN_D0") (class "Default")
      (node (ref "SCREEN") (pin "D0") (pinfunction "D0_D0") (pintype "bidirectional"))
      (node (ref "SLAVE_DEBUG") (pin "24") (pinfunction "24_24") (pintype "bidirectional"))
    )
    (net (code "187") (name "SCREEN_D1") (class "Default")
      (node (ref "SCREEN") (pin "D1") (pinfunction "D1_D1") (pintype "bidirectional"))
      (node (ref "SLAVE_DEBUG") (pin "25") (pinfunction "25_25") (pintype "bidirectional"))
    )
    (net (code "188") (name "SCREEN_D2") (class "Default")
      (node (ref "SCREEN") (pin "D2") (pinfunction "D2_D2") (pintype "bidirectional"))
      (node (ref "SLAVE_DEBUG") (pin "26") (pinfunction "26_26") (pintype "bidirectional"))
    )
    (net (code "189") (name "SCREEN_D3") (class "Default")
      (node (ref "SCREEN") (pin "D3") (pinfunction "D3_D3") (pintype "bidirectional"))
      (node (ref "SLAVE_DEBUG") (pin "27") (pinfunction "27_27") (pintype "bidirectional"))
    )
    (net (code "190") (name "SCREEN_D4") (class "Default")
      (node (ref "SCREEN") (pin "D4") (pinfunction "D4_D4") (pintype "bidirectional"))
      (node (ref "SLAVE_DEBUG") (pin "28") (pinfunction "28_28") (pintype "bidirectional"))
    )
    (net (code "191") (name "SCREEN_D5") (class "Default")
      (node (ref "SCREEN") (pin "D5") (pinfunction "D5_D5") (pintype "bidirectional"))
      (node (ref "SLAVE_DEBUG") (pin "29") (pinfunction "29/PWM_29") (pintype "bidirectional"))
    )
    (net (code "192") (name "SCREEN_D6") (class "Default")
      (node (ref "SCREEN") (pin "D6") (pinfunction "D6_D6") (pintype "bidirectional"))
      (node (ref "SLAVE_DEBUG") (pin "30") (pinfunction "30/PWM_30") (pintype "bidirectional"))
    )
    (net (code "193") (name "SCREEN_D7") (class "Default")
      (node (ref "SCREEN") (pin "D7") (pinfunction "D7_D7") (pintype "bidirectional"))
      (node (ref "SLAVE_DEBUG") (pin "31") (pinfunction "31/A12/RX4/CS1_31") (pintype "bidirectional"))
    )
    (net (code "194") (name "SCREEN_RD") (class "Default")
      (node (ref "SCREEN") (pin "RD") (pinfunction "RD_RD") (pintype "bidirectional"))
      (node (ref "SLAVE_DEBUG") (pin "19") (pinfunction "19/A5/SCL0_19") (pintype "bidirectional"))
    )
    (net (code "195") (name "SCREEN_WR") (class "Default")
      (node (ref "SCREEN") (pin "WR") (pinfunction "WR_WR") (pintype "bidirectional"))
      (node (ref "SLAVE_DEBUG") (pin "20") (pinfunction "20/A6/PWM/CS0_20") (pintype "bidirectional"))
    )
    (net (code "196") (name "SCREEN_X+") (class "Default")
      (node (ref "SCREEN") (pin "X+_2") (pinfunction "X+_2_X+_2") (pintype "bidirectional"))
      (node (ref "SLAVE_DEBUG") (pin "15") (pinfunction "15/A1/CS0_15") (pintype "bidirectional"))
    )
    (net (code "197") (name "SCREEN_X-") (class "Default")
      (node (ref "SCREEN") (pin "X-_2") (pinfunction "X-_2_X-_2") (pintype "bidirectional"))
      (node (ref "SLAVE_DEBUG") (pin "16") (pinfunction "16/A2_16") (pintype "bidirectional"))
    )
    (net (code "198") (name "SCREEN_Y+") (class "Default")
      (node (ref "SCREEN") (pin "Y+_2") (pinfunction "Y+_2_Y+_2") (pintype "bidirectional"))
      (node (ref "SLAVE_DEBUG") (pin "17") (pinfunction "17/A3_17") (pintype "bidirectional"))
    )
    (net (code "199") (name "SCREEN_Y-") (class "Default")
      (node (ref "SCREEN") (pin "Y-_2") (pinfunction "Y-_2_Y-_2") (pintype "bidirectional"))
      (node (ref "SLAVE_DEBUG") (pin "18") (pinfunction "18/A4/SDA0_18") (pintype "bidirectional"))
    )
    (net (code "200") (name "V_BAT") (class "Default")
      (node (ref "R1") (pin "2") (pinfunction "2_2") (pintype "passive"))
      (node (ref "R2") (pin "1") (pinfunction "1_1") (pintype "passive"))
      (node (ref "SLAVE_DEBUG") (pin "DA1") (pinfunction "A22/DAC1_DA1") (pintype "bidirectional"))
    )
    (net (code "201") (name "unconnected-(BT_DEBUG-PadNC1)") (class "Default")
      (node (ref "BT_DEBUG") (pin "NC1") (pinfunction "NC1_NC1") (pintype "bidirectional"))
    )
    (net (code "202") (name "unconnected-(BT_DEBUG-PadNC2)") (class "Default")
      (node (ref "BT_DEBUG") (pin "NC2") (pinfunction "NC2_NC2") (pintype "bidirectional"))
    )
    (net (code "203") (name "unconnected-(BT_DEBUG-PadNC3)") (class "Default")
      (node (ref "BT_DEBUG") (pin "NC3") (pinfunction "NC3_NC3") (pintype "bidirectional"))
    )
    (net (code "204") (name "unconnected-(BT_DEBUG-PadNV1)") (class "Default")
      (node (ref "BT_DEBUG") (pin "NV1") (pinfunction "NV1_NV1") (pintype "bidirectional"))
    )
    (net (code "205") (name "unconnected-(BT_DEBUG-PadNV2)") (class "Default")
      (node (ref "BT_DEBUG") (pin "NV2") (pinfunction "NV2_NV2") (pintype "bidirectional"))
    )
    (net (code "206") (name "unconnected-(BT_DEBUG-PadPIO0)") (class "Default")
      (node (ref "BT_DEBUG") (pin "PIO0") (pinfunction "PIO0_PIO0") (pintype "bidirectional"))
    )
    (net (code "207") (name "unconnected-(BT_DEBUG-PadPIO2)") (class "Default")
      (node (ref "BT_DEBUG") (pin "PIO2") (pinfunction "PIO2_PIO2") (pintype "bidirectional"))
    )
    (net (code "208") (name "unconnected-(BT_DEBUG-PadPIO3)") (class "Default")
      (node (ref "BT_DEBUG") (pin "PIO3") (pinfunction "PIO3_PIO3") (pintype "bidirectional"))
    )
    (net (code "209") (name "unconnected-(BT_DEBUG-PadRESETB)") (class "Default")
      (node (ref "BT_DEBUG") (pin "RESETB") (pinfunction "RESETB_RESETB") (pintype "bidirectional"))
    )
    (net (code "210") (name "unconnected-(BT_DEBUG-PadUART_CTS)") (class "Default")
      (node (ref "BT_DEBUG") (pin "UART_CTS") (pinfunction "UART_CTS_UART_CTS") (pintype "bidirectional"))
    )
    (net (code "211") (name "unconnected-(BT_DEBUG-PadUART_RTS)") (class "Default")
      (node (ref "BT_DEBUG") (pin "UART_RTS") (pinfunction "UART_RTS_UART_RTS") (pintype "bidirectional"))
    )
    (net (code "212") (name "unconnected-(BT_IRC-PadNC1)") (class "Default")
      (node (ref "BT_IRC") (pin "NC1") (pinfunction "NC1_NC1") (pintype "bidirectional"))
    )
    (net (code "213") (name "unconnected-(BT_IRC-PadNC2)") (class "Default")
      (node (ref "BT_IRC") (pin "NC2") (pinfunction "NC2_NC2") (pintype "bidirectional"))
    )
    (net (code "214") (name "unconnected-(BT_IRC-PadNC3)") (class "Default")
      (node (ref "BT_IRC") (pin "NC3") (pinfunction "NC3_NC3") (pintype "bidirectional"))
    )
    (net (code "215") (name "unconnected-(BT_IRC-PadNV1)") (class "Default")
      (node (ref "BT_IRC") (pin "NV1") (pinfunction "NV1_NV1") (pintype "bidirectional"))
    )
    (net (code "216") (name "unconnected-(BT_IRC-PadNV2)") (class "Default")
      (node (ref "BT_IRC") (pin "NV2") (pinfunction "NV2_NV2") (pintype "bidirectional"))
    )
    (net (code "217") (name "unconnected-(BT_IRC-PadPIO0)") (class "Default")
      (node (ref "BT_IRC") (pin "PIO0") (pinfunction "PIO0_PIO0") (pintype "bidirectional"))
    )
    (net (code "218") (name "unconnected-(BT_IRC-PadPIO2)") (class "Default")
      (node (ref "BT_IRC") (pin "PIO2") (pinfunction "PIO2_PIO2") (pintype "bidirectional"))
    )
    (net (code "219") (name "unconnected-(BT_IRC-PadPIO3)") (class "Default")
      (node (ref "BT_IRC") (pin "PIO3") (pinfunction "PIO3_PIO3") (pintype "bidirectional"))
    )
    (net (code "220") (name "unconnected-(BT_IRC-PadRESETB)") (class "Default")
      (node (ref "BT_IRC") (pin "RESETB") (pinfunction "RESETB_RESETB") (pintype "bidirectional"))
    )
    (net (code "221") (name "unconnected-(BT_IRC-PadUART_CTS)") (class "Default")
      (node (ref "BT_IRC") (pin "UART_CTS") (pinfunction "UART_CTS_UART_CTS") (pintype "bidirectional"))
    )
    (net (code "222") (name "unconnected-(BT_IRC-PadUART_RTS)") (class "Default")
      (node (ref "BT_IRC") (pin "UART_RTS") (pinfunction "UART_RTS_UART_RTS") (pintype "bidirectional"))
    )
    (net (code "223") (name "unconnected-(D14-DOUT-Pad2)") (class "Default")
      (node (ref "D14") (pin "2") (pinfunction "DOUT_2") (pintype "output"))
    )
    (net (code "224") (name "unconnected-(MASTER-0{slash}RX1{slash}MOSI1-Pad0)") (class "Default")
      (node (ref "MASTER") (pin "0") (pinfunction "0/RX1/MOSI1_0") (pintype "bidirectional"))
    )
    (net (code "225") (name "unconnected-(MASTER-1{slash}TX1{slash}MISO1-Pad1)") (class "Default")
      (node (ref "MASTER") (pin "1") (pinfunction "1/TX1/MISO1_1") (pintype "bidirectional"))
    )
    (net (code "226") (name "unconnected-(MASTER-2{slash}PWM-Pad2)") (class "Default")
      (node (ref "MASTER") (pin "2") (pinfunction "2/PWM_2") (pintype "bidirectional"))
    )
    (net (code "227") (name "unconnected-(MASTER-3{slash}PWM{slash}CAN0TX{slash}SCL2-Pad3)") (class "Default")
      (node (ref "MASTER") (pin "3") (pinfunction "3/PWM/CAN0TX/SCL2_3") (pintype "bidirectional"))
    )
    (net (code "228") (name "unconnected-(MASTER-4{slash}PWM{slash}CAN0RX{slash}SDA2-Pad4)") (class "Default")
      (node (ref "MASTER") (pin "4") (pinfunction "4/PWM/CAN0RX/SDA2_4") (pintype "bidirectional"))
    )
    (net (code "229") (name "unconnected-(MASTER-5{slash}PWM-Pad5)") (class "Default")
      (node (ref "MASTER") (pin "5") (pinfunction "5/PWM_5") (pintype "bidirectional"))
    )
    (net (code "230") (name "unconnected-(MASTER-6{slash}PWM-Pad6)") (class "Default")
      (node (ref "MASTER") (pin "6") (pinfunction "6/PWM_6") (pintype "bidirectional"))
    )
    (net (code "231") (name "unconnected-(MASTER-13{slash}SCK0-Pad13)") (class "Default")
      (node (ref "MASTER") (pin "13") (pinfunction "13/SCK0_13") (pintype "bidirectional"))
    )
    (net (code "232") (name "unconnected-(MASTER-16{slash}A2-Pad16)") (class "Default")
      (node (ref "MASTER") (pin "16") (pinfunction "16/A2_16") (pintype "bidirectional"))
    )
    (net (code "233") (name "unconnected-(MASTER-17{slash}A3-Pad17)") (class "Default")
      (node (ref "MASTER") (pin "17") (pinfunction "17/A3_17") (pintype "bidirectional"))
    )
    (net (code "234") (name "unconnected-(MASTER-18{slash}A4{slash}SDA0-Pad18)") (class "Default")
      (node (ref "MASTER") (pin "18") (pinfunction "18/A4/SDA0_18") (pintype "bidirectional"))
    )
    (net (code "235") (name "unconnected-(MASTER-19{slash}A5{slash}SCL0-Pad19)") (class "Default")
      (node (ref "MASTER") (pin "19") (pinfunction "19/A5/SCL0_19") (pintype "bidirectional"))
    )
    (net (code "236") (name "unconnected-(MASTER-29{slash}PWM-Pad29)") (class "Default")
      (node (ref "MASTER") (pin "29") (pinfunction "29/PWM_29") (pintype "bidirectional"))
    )
    (net (code "237") (name "unconnected-(MASTER-30{slash}PWM-Pad30)") (class "Default")
      (node (ref "MASTER") (pin "30") (pinfunction "30/PWM_30") (pintype "bidirectional"))
    )
    (net (code "238") (name "unconnected-(MASTER-31{slash}A12{slash}RX4{slash}CS1-Pad31)") (class "Default")
      (node (ref "MASTER") (pin "31") (pinfunction "31/A12/RX4/CS1_31") (pintype "bidirectional"))
    )
    (net (code "239") (name "unconnected-(MASTER-32{slash}A13{slash}TX4{slash}SCK1-Pad32)") (class "Default")
      (node (ref "MASTER") (pin "32") (pinfunction "32/A13/TX4/SCK1_32") (pintype "bidirectional"))
    )
    (net (code "240") (name "unconnected-(MASTER-35{slash}A16{slash}PWM-Pad35)") (class "Default")
      (node (ref "MASTER") (pin "35") (pinfunction "35/A16/PWM_35") (pintype "bidirectional"))
    )
    (net (code "241") (name "unconnected-(MASTER-36{slash}A17{slash}PWM-Pad36)") (class "Default")
      (node (ref "MASTER") (pin "36") (pinfunction "36/A17/PWM_36") (pintype "bidirectional"))
    )
    (net (code "242") (name "unconnected-(MASTER-37{slash}A18{slash}PWM{slash}SCL1-Pad37)") (class "Default")
      (node (ref "MASTER") (pin "37") (pinfunction "37/A18/PWM/SCL1_37") (pintype "bidirectional"))
    )
    (net (code "243") (name "unconnected-(MASTER-38{slash}A19{slash}PWM{slash}SDA1-Pad38)") (class "Default")
      (node (ref "MASTER") (pin "38") (pinfunction "38/A19/PWM/SDA1_38") (pintype "bidirectional"))
    )
    (net (code "244") (name "unconnected-(MASTER-39{slash}A20-Pad39)") (class "Default")
      (node (ref "MASTER") (pin "39") (pinfunction "39/A20_39") (pintype "bidirectional"))
    )
    (net (code "245") (name "unconnected-(MASTER-47{slash}RX6-Pad47)") (class "Default")
      (node (ref "MASTER") (pin "47") (pinfunction "47/RX6_47") (pintype "bidirectional"))
    )
    (net (code "246") (name "unconnected-(MASTER-48{slash}TX6-Pad48)") (class "Default")
      (node (ref "MASTER") (pin "48") (pinfunction "48/TX6_48") (pintype "bidirectional"))
    )
    (net (code "247") (name "unconnected-(MASTER-49{slash}A23-Pad49)") (class "Default")
      (node (ref "MASTER") (pin "49") (pinfunction "49/A23_49") (pintype "bidirectional"))
    )
    (net (code "248") (name "unconnected-(MASTER-50{slash}A24-Pad50)") (class "Default")
      (node (ref "MASTER") (pin "50") (pinfunction "50/A24_50") (pintype "bidirectional"))
    )
    (net (code "249") (name "unconnected-(MASTER-A21{slash}DAC0-PadDA0)") (class "Default")
      (node (ref "MASTER") (pin "DA0") (pinfunction "A21/DAC0_DA0") (pintype "bidirectional"))
    )
    (net (code "250") (name "unconnected-(MASTER-A22{slash}DAC1-PadDA1)") (class "Default")
      (node (ref "MASTER") (pin "DA1") (pinfunction "A22/DAC1_DA1") (pintype "bidirectional"))
    )
    (net (code "251") (name "unconnected-(MASTER-DEBUG-1-PadDD)") (class "Default")
      (node (ref "MASTER") (pin "DD") (pinfunction "DEBUG-1_DD") (pintype "bidirectional"))
    )
    (net (code "252") (name "unconnected-(MASTER-DEBUG-2-PadDE)") (class "Default")
      (node (ref "MASTER") (pin "DE") (pinfunction "DEBUG-2_DE") (pintype "bidirectional"))
    )
    (net (code "253") (name "unconnected-(MASTER-DEBUG-PadDC)") (class "Default")
      (node (ref "MASTER") (pin "DC") (pinfunction "DEBUG_DC") (pintype "bidirectional"))
    )
    (net (code "254") (name "unconnected-(MASTER-Pad3.3V)") (class "Default")
      (node (ref "MASTER") (pin "3.3V") (pinfunction "3.3V_3.3V") (pintype "bidirectional"))
    )
    (net (code "255") (name "unconnected-(MASTER-Pad3.3V-2)") (class "Default")
      (node (ref "MASTER") (pin "3.3V-2") (pinfunction "3.3V-2_3.3V-2") (pintype "bidirectional"))
    )
    (net (code "256") (name "unconnected-(MASTER-Pad3.3V-3)") (class "Default")
      (node (ref "MASTER") (pin "3.3V-3") (pinfunction "3.3V-3_3.3V-3") (pintype "bidirectional"))
    )
    (net (code "257") (name "unconnected-(MASTER-Pad24)") (class "Default")
      (node (ref "MASTER") (pin "24") (pinfunction "24_24") (pintype "bidirectional"))
    )
    (net (code "258") (name "unconnected-(MASTER-Pad25)") (class "Default")
      (node (ref "MASTER") (pin "25") (pinfunction "25_25") (pintype "bidirectional"))
    )
    (net (code "259") (name "unconnected-(MASTER-Pad26)") (class "Default")
      (node (ref "MASTER") (pin "26") (pinfunction "26_26") (pintype "bidirectional"))
    )
    (net (code "260") (name "unconnected-(MASTER-Pad27)") (class "Default")
      (node (ref "MASTER") (pin "27") (pinfunction "27_27") (pintype "bidirectional"))
    )
    (net (code "261") (name "unconnected-(MASTER-Pad28)") (class "Default")
      (node (ref "MASTER") (pin "28") (pinfunction "28_28") (pintype "bidirectional"))
    )
    (net (code "262") (name "unconnected-(MASTER-Pad40)") (class "Default")
      (node (ref "MASTER") (pin "40") (pinfunction "40_40") (pintype "bidirectional"))
    )
    (net (code "263") (name "unconnected-(MASTER-Pad41)") (class "Default")
      (node (ref "MASTER") (pin "41") (pinfunction "41_41") (pintype "bidirectional"))
    )
    (net (code "264") (name "unconnected-(MASTER-Pad42)") (class "Default")
      (node (ref "MASTER") (pin "42") (pinfunction "42_42") (pintype "bidirectional"))
    )
    (net (code "265") (name "unconnected-(MASTER-Pad51)") (class "Default")
      (node (ref "MASTER") (pin "51") (pinfunction "51_51") (pintype "bidirectional"))
    )
    (net (code "266") (name "unconnected-(MASTER-Pad52)") (class "Default")
      (node (ref "MASTER") (pin "52") (pinfunction "52_52") (pintype "bidirectional"))
    )
    (net (code "267") (name "unconnected-(MASTER-Pad53)") (class "Default")
      (node (ref "MASTER") (pin "53") (pinfunction "53_53") (pintype "bidirectional"))
    )
    (net (code "268") (name "unconnected-(MASTER-Pad56)") (class "Default")
      (node (ref "MASTER") (pin "56") (pinfunction "56_56") (pintype "bidirectional"))
    )
    (net (code "269") (name "unconnected-(MASTER-Pad57)") (class "Default")
      (node (ref "MASTER") (pin "57") (pinfunction "57_57") (pintype "bidirectional"))
    )
    (net (code "270") (name "unconnected-(MASTER-PadA10)") (class "Default")
      (node (ref "MASTER") (pin "A10") (pinfunction "A10_A10") (pintype "bidirectional"))
    )
    (net (code "271") (name "unconnected-(MASTER-PadA11)") (class "Default")
      (node (ref "MASTER") (pin "A11") (pinfunction "A11_A11") (pintype "bidirectional"))
    )
    (net (code "272") (name "unconnected-(MASTER-PadAREF)") (class "Default")
      (node (ref "MASTER") (pin "AREF") (pinfunction "AREF_AREF") (pintype "bidirectional"))
    )
    (net (code "273") (name "unconnected-(MASTER-PadPRGRM)") (class "Default")
      (node (ref "MASTER") (pin "PRGRM") (pinfunction "PRGRM_PRGRM") (pintype "bidirectional"))
    )
    (net (code "274") (name "unconnected-(MASTER-PadRESET)") (class "Default")
      (node (ref "MASTER") (pin "RESET") (pinfunction "RESET_RESET") (pintype "bidirectional"))
    )
    (net (code "275") (name "unconnected-(MASTER-PadVBAT)") (class "Default")
      (node (ref "MASTER") (pin "VBAT") (pinfunction "VBAT_VBAT") (pintype "bidirectional"))
    )
    (net (code "276") (name "unconnected-(MASTER-PadVIN)") (class "Default")
      (node (ref "MASTER") (pin "VIN") (pinfunction "VIN_VIN") (pintype "bidirectional"))
    )
    (net (code "277") (name "unconnected-(MASTER-PadVUSB)") (class "Default")
      (node (ref "MASTER") (pin "VUSB") (pinfunction "VUSB_VUSB") (pintype "bidirectional"))
    )
    (net (code "278") (name "unconnected-(P1-CS_DIS-Pad20)") (class "Default")
      (node (ref "P1") (pin "20") (pinfunction "CS_DIS_20") (pintype "bidirectional"))
    )
    (net (code "279") (name "unconnected-(P2-CS_DIS-Pad20)") (class "Default")
      (node (ref "P2") (pin "20") (pinfunction "CS_DIS_20") (pintype "bidirectional"))
    )
    (net (code "280") (name "unconnected-(P3-CS_DIS-Pad20)") (class "Default")
      (node (ref "P3") (pin "20") (pinfunction "CS_DIS_20") (pintype "bidirectional"))
    )
    (net (code "281") (name "unconnected-(P4-CS_DIS-Pad20)") (class "Default")
      (node (ref "P4") (pin "20") (pinfunction "CS_DIS_20") (pintype "bidirectional"))
    )
    (net (code "282") (name "unconnected-(SCREEN-Pad3VO)") (class "Default")
      (node (ref "SCREEN") (pin "3VO") (pinfunction "3VO_3VO") (pintype "bidirectional"))
    )
    (net (code "283") (name "unconnected-(SCREEN-PadCCS)") (class "Default")
      (node (ref "SCREEN") (pin "CCS") (pinfunction "CCS_CCS") (pintype "bidirectional"))
    )
    (net (code "284") (name "unconnected-(SCREEN-PadCD)") (class "Default")
      (node (ref "SCREEN") (pin "CD") (pinfunction "CD_CD") (pintype "bidirectional"))
    )
    (net (code "285") (name "unconnected-(SCREEN-PadCLK)") (class "Default")
      (node (ref "SCREEN") (pin "CLK") (pinfunction "CLK_CLK") (pintype "bidirectional"))
    )
    (net (code "286") (name "unconnected-(SCREEN-PadCS)") (class "Default")
      (node (ref "SCREEN") (pin "CS") (pinfunction "CS_CS") (pintype "bidirectional"))
    )
    (net (code "287") (name "unconnected-(SCREEN-PadD{slash}C)") (class "Default")
      (node (ref "SCREEN") (pin "D/C") (pinfunction "D/C_D/C") (pintype "bidirectional"))
    )
    (net (code "288") (name "unconnected-(SCREEN-PadIM0)") (class "Default")
      (node (ref "SCREEN") (pin "IM0") (pinfunction "IM0_IM0") (pintype "bidirectional"))
    )
    (net (code "289") (name "unconnected-(SCREEN-PadIM1)") (class "Default")
      (node (ref "SCREEN") (pin "IM1") (pinfunction "IM1_IM1") (pintype "bidirectional"))
    )
    (net (code "290") (name "unconnected-(SCREEN-PadIM2)") (class "Default")
      (node (ref "SCREEN") (pin "IM2") (pinfunction "IM2_IM2") (pintype "bidirectional"))
    )
    (net (code "291") (name "unconnected-(SCREEN-PadIM3)") (class "Default")
      (node (ref "SCREEN") (pin "IM3") (pinfunction "IM3_IM3") (pintype "bidirectional"))
    )
    (net (code "292") (name "unconnected-(SCREEN-PadLITE_2)") (class "Default")
      (node (ref "SCREEN") (pin "LITE_2") (pinfunction "LITE_2_LITE_2") (pintype "bidirectional"))
    )
    (net (code "293") (name "unconnected-(SCREEN-PadMISO)") (class "Default")
      (node (ref "SCREEN") (pin "MISO") (pinfunction "MISO_MISO") (pintype "bidirectional"))
    )
    (net (code "294") (name "unconnected-(SCREEN-PadMOSI)") (class "Default")
      (node (ref "SCREEN") (pin "MOSI") (pinfunction "MOSI_MOSI") (pintype "bidirectional"))
    )
    (net (code "295") (name "unconnected-(SCREEN-PadRST_2)") (class "Default")
      (node (ref "SCREEN") (pin "RST_2") (pinfunction "RST_2_RST_2") (pintype "bidirectional"))
    )
    (net (code "296") (name "unconnected-(SCREEN-PadVIN)") (class "Default")
      (node (ref "SCREEN") (pin "VIN") (pinfunction "VIN_VIN") (pintype "bidirectional"))
    )
    (net (code "297") (name "unconnected-(SLAVE_DEBUG-0{slash}RX1{slash}MOSI1-Pad0)") (class "Default")
      (node (ref "SLAVE_DEBUG") (pin "0") (pinfunction "0/RX1/MOSI1_0") (pintype "bidirectional"))
    )
    (net (code "298") (name "unconnected-(SLAVE_DEBUG-1{slash}TX1{slash}MISO1-Pad1)") (class "Default")
      (node (ref "SLAVE_DEBUG") (pin "1") (pinfunction "1/TX1/MISO1_1") (pintype "bidirectional"))
    )
    (net (code "299") (name "unconnected-(SLAVE_DEBUG-13{slash}SCK0-Pad13)") (class "Default")
      (node (ref "SLAVE_DEBUG") (pin "13") (pinfunction "13/SCK0_13") (pintype "bidirectional"))
    )
    (net (code "300") (name "unconnected-(SLAVE_DEBUG-32{slash}A13{slash}TX4{slash}SCK1-Pad32)") (class "Default")
      (node (ref "SLAVE_DEBUG") (pin "32") (pinfunction "32/A13/TX4/SCK1_32") (pintype "bidirectional"))
    )
    (net (code "301") (name "unconnected-(SLAVE_DEBUG-35{slash}A16{slash}PWM-Pad35)") (class "Default")
      (node (ref "SLAVE_DEBUG") (pin "35") (pinfunction "35/A16/PWM_35") (pintype "bidirectional"))
    )
    (net (code "302") (name "unconnected-(SLAVE_DEBUG-36{slash}A17{slash}PWM-Pad36)") (class "Default")
      (node (ref "SLAVE_DEBUG") (pin "36") (pinfunction "36/A17/PWM_36") (pintype "bidirectional"))
    )
    (net (code "303") (name "unconnected-(SLAVE_DEBUG-37{slash}A18{slash}PWM{slash}SCL1-Pad37)") (class "Default")
      (node (ref "SLAVE_DEBUG") (pin "37") (pinfunction "37/A18/PWM/SCL1_37") (pintype "bidirectional"))
    )
    (net (code "304") (name "unconnected-(SLAVE_DEBUG-38{slash}A19{slash}PWM{slash}SDA1-Pad38)") (class "Default")
      (node (ref "SLAVE_DEBUG") (pin "38") (pinfunction "38/A19/PWM/SDA1_38") (pintype "bidirectional"))
    )
    (net (code "305") (name "unconnected-(SLAVE_DEBUG-39{slash}A20-Pad39)") (class "Default")
      (node (ref "SLAVE_DEBUG") (pin "39") (pinfunction "39/A20_39") (pintype "bidirectional"))
    )
    (net (code "306") (name "unconnected-(SLAVE_DEBUG-43{slash}CS2-Pad43)") (class "Default")
      (node (ref "SLAVE_DEBUG") (pin "43") (pinfunction "43/CS2_43") (pintype "bidirectional"))
    )
    (net (code "307") (name "unconnected-(SLAVE_DEBUG-44{slash}MOSI2-Pad44)") (class "Default")
      (node (ref "SLAVE_DEBUG") (pin "44") (pinfunction "44/MOSI2_44") (pintype "bidirectional"))
    )
    (net (code "308") (name "unconnected-(SLAVE_DEBUG-45{slash}MISO2-Pad45)") (class "Default")
      (node (ref "SLAVE_DEBUG") (pin "45") (pinfunction "45/MISO2_45") (pintype "bidirectional"))
    )
    (net (code "309") (name "unconnected-(SLAVE_DEBUG-46{slash}SCK2-Pad46)") (class "Default")
      (node (ref "SLAVE_DEBUG") (pin "46") (pinfunction "46/SCK2_46") (pintype "bidirectional"))
    )
    (net (code "310") (name "unconnected-(SLAVE_DEBUG-47{slash}RX6-Pad47)") (class "Default")
      (node (ref "SLAVE_DEBUG") (pin "47") (pinfunction "47/RX6_47") (pintype "bidirectional"))
    )
    (net (code "311") (name "unconnected-(SLAVE_DEBUG-48{slash}TX6-Pad48)") (class "Default")
      (node (ref "SLAVE_DEBUG") (pin "48") (pinfunction "48/TX6_48") (pintype "bidirectional"))
    )
    (net (code "312") (name "unconnected-(SLAVE_DEBUG-49{slash}A23-Pad49)") (class "Default")
      (node (ref "SLAVE_DEBUG") (pin "49") (pinfunction "49/A23_49") (pintype "bidirectional"))
    )
    (net (code "313") (name "unconnected-(SLAVE_DEBUG-50{slash}A24-Pad50)") (class "Default")
      (node (ref "SLAVE_DEBUG") (pin "50") (pinfunction "50/A24_50") (pintype "bidirectional"))
    )
    (net (code "314") (name "unconnected-(SLAVE_DEBUG-54{slash}CS2-Pad54)") (class "Default")
      (node (ref "SLAVE_DEBUG") (pin "54") (pinfunction "54/CS2_54") (pintype "bidirectional"))
    )
    (net (code "315") (name "unconnected-(SLAVE_DEBUG-A21{slash}DAC0-PadDA0)") (class "Default")
      (node (ref "SLAVE_DEBUG") (pin "DA0") (pinfunction "A21/DAC0_DA0") (pintype "bidirectional"))
    )
    (net (code "316") (name "unconnected-(SLAVE_DEBUG-DEBUG-1-PadDD)") (class "Default")
      (node (ref "SLAVE_DEBUG") (pin "DD") (pinfunction "DEBUG-1_DD") (pintype "bidirectional"))
    )
    (net (code "317") (name "unconnected-(SLAVE_DEBUG-DEBUG-2-PadDE)") (class "Default")
      (node (ref "SLAVE_DEBUG") (pin "DE") (pinfunction "DEBUG-2_DE") (pintype "bidirectional"))
    )
    (net (code "318") (name "unconnected-(SLAVE_DEBUG-DEBUG-PadDC)") (class "Default")
      (node (ref "SLAVE_DEBUG") (pin "DC") (pinfunction "DEBUG_DC") (pintype "bidirectional"))
    )
    (net (code "319") (name "unconnected-(SLAVE_DEBUG-Pad3.3V)") (class "Default")
      (node (ref "SLAVE_DEBUG") (pin "3.3V") (pinfunction "3.3V_3.3V") (pintype "bidirectional"))
    )
    (net (code "320") (name "unconnected-(SLAVE_DEBUG-Pad3.3V-2)") (class "Default")
      (node (ref "SLAVE_DEBUG") (pin "3.3V-2") (pinfunction "3.3V-2_3.3V-2") (pintype "bidirectional"))
    )
    (net (code "321") (name "unconnected-(SLAVE_DEBUG-Pad3.3V-3)") (class "Default")
      (node (ref "SLAVE_DEBUG") (pin "3.3V-3") (pinfunction "3.3V-3_3.3V-3") (pintype "bidirectional"))
    )
    (net (code "322") (name "unconnected-(SLAVE_DEBUG-Pad40)") (class "Default")
      (node (ref "SLAVE_DEBUG") (pin "40") (pinfunction "40_40") (pintype "bidirectional"))
    )
    (net (code "323") (name "unconnected-(SLAVE_DEBUG-Pad41)") (class "Default")
      (node (ref "SLAVE_DEBUG") (pin "41") (pinfunction "41_41") (pintype "bidirectional"))
    )
    (net (code "324") (name "unconnected-(SLAVE_DEBUG-Pad42)") (class "Default")
      (node (ref "SLAVE_DEBUG") (pin "42") (pinfunction "42_42") (pintype "bidirectional"))
    )
    (net (code "325") (name "unconnected-(SLAVE_DEBUG-Pad51)") (class "Default")
      (node (ref "SLAVE_DEBUG") (pin "51") (pinfunction "51_51") (pintype "bidirectional"))
    )
    (net (code "326") (name "unconnected-(SLAVE_DEBUG-Pad52)") (class "Default")
      (node (ref "SLAVE_DEBUG") (pin "52") (pinfunction "52_52") (pintype "bidirectional"))
    )
    (net (code "327") (name "unconnected-(SLAVE_DEBUG-Pad53)") (class "Default")
      (node (ref "SLAVE_DEBUG") (pin "53") (pinfunction "53_53") (pintype "bidirectional"))
    )
    (net (code "328") (name "unconnected-(SLAVE_DEBUG-Pad55)") (class "Default")
      (node (ref "SLAVE_DEBUG") (pin "55") (pinfunction "55_55") (pintype "bidirectional"))
    )
    (net (code "329") (name "unconnected-(SLAVE_DEBUG-Pad56)") (class "Default")
      (node (ref "SLAVE_DEBUG") (pin "56") (pinfunction "56_56") (pintype "bidirectional"))
    )
    (net (code "330") (name "unconnected-(SLAVE_DEBUG-Pad57)") (class "Default")
      (node (ref "SLAVE_DEBUG") (pin "57") (pinfunction "57_57") (pintype "bidirectional"))
    )
    (net (code "331") (name "unconnected-(SLAVE_DEBUG-PadA10)") (class "Default")
      (node (ref "SLAVE_DEBUG") (pin "A10") (pinfunction "A10_A10") (pintype "bidirectional"))
    )
    (net (code "332") (name "unconnected-(SLAVE_DEBUG-PadA11)") (class "Default")
      (node (ref "SLAVE_DEBUG") (pin "A11") (pinfunction "A11_A11") (pintype "bidirectional"))
    )
    (net (code "333") (name "unconnected-(SLAVE_DEBUG-PadAREF)") (class "Default")
      (node (ref "SLAVE_DEBUG") (pin "AREF") (pinfunction "AREF_AREF") (pintype "bidirectional"))
    )
    (net (code "334") (name "unconnected-(SLAVE_DEBUG-PadPRGRM)") (class "Default")
      (node (ref "SLAVE_DEBUG") (pin "PRGRM") (pinfunction "PRGRM_PRGRM") (pintype "bidirectional"))
    )
    (net (code "335") (name "unconnected-(SLAVE_DEBUG-PadRESET)") (class "Default")
      (node (ref "SLAVE_DEBUG") (pin "RESET") (pinfunction "RESET_RESET") (pintype "bidirectional"))
    )
    (net (code "336") (name "unconnected-(SLAVE_DEBUG-PadVBAT)") (class "Default")
      (node (ref "SLAVE_DEBUG") (pin "VBAT") (pinfunction "VBAT_VBAT") (pintype "bidirectional"))
    )
    (net (code "337") (name "unconnected-(SLAVE_DEBUG-PadVIN)") (class "Default")
      (node (ref "SLAVE_DEBUG") (pin "VIN") (pinfunction "VIN_VIN") (pintype "bidirectional"))
    )
    (net (code "338") (name "unconnected-(SLAVE_DEBUG-PadVUSB)") (class "Default")
      (node (ref "SLAVE_DEBUG") (pin "VUSB") (pinfunction "VUSB_VUSB") (pintype "bidirectional"))
    )
    (net (code "339") (name "unconnected-(SLAVE_MOTOR-0{slash}RX1{slash}MOSI1-Pad0)") (class "Default")
      (node (ref "SLAVE_MOTOR") (pin "0") (pinfunction "0/RX1/MOSI1_0") (pintype "bidirectional"))
    )
    (net (code "340") (name "unconnected-(SLAVE_MOTOR-1{slash}TX1{slash}MISO1-Pad1)") (class "Default")
      (node (ref "SLAVE_MOTOR") (pin "1") (pinfunction "1/TX1/MISO1_1") (pintype "bidirectional"))
    )
    (net (code "341") (name "unconnected-(SLAVE_MOTOR-13{slash}SCK0-Pad13)") (class "Default")
      (node (ref "SLAVE_MOTOR") (pin "13") (pinfunction "13/SCK0_13") (pintype "bidirectional"))
    )
    (net (code "342") (name "unconnected-(SLAVE_MOTOR-15{slash}A1{slash}CS0-Pad15)") (class "Default")
      (node (ref "SLAVE_MOTOR") (pin "15") (pinfunction "15/A1/CS0_15") (pintype "bidirectional"))
    )
    (net (code "343") (name "unconnected-(SLAVE_MOTOR-43{slash}CS2-Pad43)") (class "Default")
      (node (ref "SLAVE_MOTOR") (pin "43") (pinfunction "43/CS2_43") (pintype "bidirectional"))
    )
    (net (code "344") (name "unconnected-(SLAVE_MOTOR-44{slash}MOSI2-Pad44)") (class "Default")
      (node (ref "SLAVE_MOTOR") (pin "44") (pinfunction "44/MOSI2_44") (pintype "bidirectional"))
    )
    (net (code "345") (name "unconnected-(SLAVE_MOTOR-45{slash}MISO2-Pad45)") (class "Default")
      (node (ref "SLAVE_MOTOR") (pin "45") (pinfunction "45/MISO2_45") (pintype "bidirectional"))
    )
    (net (code "346") (name "unconnected-(SLAVE_MOTOR-46{slash}SCK2-Pad46)") (class "Default")
      (node (ref "SLAVE_MOTOR") (pin "46") (pinfunction "46/SCK2_46") (pintype "bidirectional"))
    )
    (net (code "347") (name "unconnected-(SLAVE_MOTOR-47{slash}RX6-Pad47)") (class "Default")
      (node (ref "SLAVE_MOTOR") (pin "47") (pinfunction "47/RX6_47") (pintype "bidirectional"))
    )
    (net (code "348") (name "unconnected-(SLAVE_MOTOR-48{slash}TX6-Pad48)") (class "Default")
      (node (ref "SLAVE_MOTOR") (pin "48") (pinfunction "48/TX6_48") (pintype "bidirectional"))
    )
    (net (code "349") (name "unconnected-(SLAVE_MOTOR-49{slash}A23-Pad49)") (class "Default")
      (node (ref "SLAVE_MOTOR") (pin "49") (pinfunction "49/A23_49") (pintype "bidirectional"))
    )
    (net (code "350") (name "unconnected-(SLAVE_MOTOR-50{slash}A24-Pad50)") (class "Default")
      (node (ref "SLAVE_MOTOR") (pin "50") (pinfunction "50/A24_50") (pintype "bidirectional"))
    )
    (net (code "351") (name "unconnected-(SLAVE_MOTOR-54{slash}CS2-Pad54)") (class "Default")
      (node (ref "SLAVE_MOTOR") (pin "54") (pinfunction "54/CS2_54") (pintype "bidirectional"))
    )
    (net (code "352") (name "unconnected-(SLAVE_MOTOR-A21{slash}DAC0-PadDA0)") (class "Default")
      (node (ref "SLAVE_MOTOR") (pin "DA0") (pinfunction "A21/DAC0_DA0") (pintype "bidirectional"))
    )
    (net (code "353") (name "unconnected-(SLAVE_MOTOR-A22{slash}DAC1-PadDA1)") (class "Default")
      (node (ref "SLAVE_MOTOR") (pin "DA1") (pinfunction "A22/DAC1_DA1") (pintype "bidirectional"))
    )
    (net (code "354") (name "unconnected-(SLAVE_MOTOR-DEBUG-1-PadDD)") (class "Default")
      (node (ref "SLAVE_MOTOR") (pin "DD") (pinfunction "DEBUG-1_DD") (pintype "bidirectional"))
    )
    (net (code "355") (name "unconnected-(SLAVE_MOTOR-DEBUG-2-PadDE)") (class "Default")
      (node (ref "SLAVE_MOTOR") (pin "DE") (pinfunction "DEBUG-2_DE") (pintype "bidirectional"))
    )
    (net (code "356") (name "unconnected-(SLAVE_MOTOR-DEBUG-PadDC)") (class "Default")
      (node (ref "SLAVE_MOTOR") (pin "DC") (pinfunction "DEBUG_DC") (pintype "bidirectional"))
    )
    (net (code "357") (name "unconnected-(SLAVE_MOTOR-Pad3.3V)") (class "Default")
      (node (ref "SLAVE_MOTOR") (pin "3.3V") (pinfunction "3.3V_3.3V") (pintype "bidirectional"))
    )
    (net (code "358") (name "unconnected-(SLAVE_MOTOR-Pad3.3V-2)") (class "Default")
      (node (ref "SLAVE_MOTOR") (pin "3.3V-2") (pinfunction "3.3V-2_3.3V-2") (pintype "bidirectional"))
    )
    (net (code "359") (name "unconnected-(SLAVE_MOTOR-Pad3.3V-3)") (class "Default")
      (node (ref "SLAVE_MOTOR") (pin "3.3V-3") (pinfunction "3.3V-3_3.3V-3") (pintype "bidirectional"))
    )
    (net (code "360") (name "unconnected-(SLAVE_MOTOR-Pad40)") (class "Default")
      (node (ref "SLAVE_MOTOR") (pin "40") (pinfunction "40_40") (pintype "bidirectional"))
    )
    (net (code "361") (name "unconnected-(SLAVE_MOTOR-Pad41)") (class "Default")
      (node (ref "SLAVE_MOTOR") (pin "41") (pinfunction "41_41") (pintype "bidirectional"))
    )
    (net (code "362") (name "unconnected-(SLAVE_MOTOR-Pad42)") (class "Default")
      (node (ref "SLAVE_MOTOR") (pin "42") (pinfunction "42_42") (pintype "bidirectional"))
    )
    (net (code "363") (name "unconnected-(SLAVE_MOTOR-Pad51)") (class "Default")
      (node (ref "SLAVE_MOTOR") (pin "51") (pinfunction "51_51") (pintype "bidirectional"))
    )
    (net (code "364") (name "unconnected-(SLAVE_MOTOR-Pad52)") (class "Default")
      (node (ref "SLAVE_MOTOR") (pin "52") (pinfunction "52_52") (pintype "bidirectional"))
    )
    (net (code "365") (name "unconnected-(SLAVE_MOTOR-Pad53)") (class "Default")
      (node (ref "SLAVE_MOTOR") (pin "53") (pinfunction "53_53") (pintype "bidirectional"))
    )
    (net (code "366") (name "unconnected-(SLAVE_MOTOR-Pad55)") (class "Default")
      (node (ref "SLAVE_MOTOR") (pin "55") (pinfunction "55_55") (pintype "bidirectional"))
    )
    (net (code "367") (name "unconnected-(SLAVE_MOTOR-Pad56)") (class "Default")
      (node (ref "SLAVE_MOTOR") (pin "56") (pinfunction "56_56") (pintype "bidirectional"))
    )
    (net (code "368") (name "unconnected-(SLAVE_MOTOR-Pad57)") (class "Default")
      (node (ref "SLAVE_MOTOR") (pin "57") (pinfunction "57_57") (pintype "bidirectional"))
    )
    (net (code "369") (name "unconnected-(SLAVE_MOTOR-PadA10)") (class "Default")
      (node (ref "SLAVE_MOTOR") (pin "A10") (pinfunction "A10_A10") (pintype "bidirectional"))
    )
    (net (code "370") (name "unconnected-(SLAVE_MOTOR-PadA11)") (class "Default")
      (node (ref "SLAVE_MOTOR") (pin "A11") (pinfunction "A11_A11") (pintype "bidirectional"))
    )
    (net (code "371") (name "unconnected-(SLAVE_MOTOR-PadAREF)") (class "Default")
      (node (ref "SLAVE_MOTOR") (pin "AREF") (pinfunction "AREF_AREF") (pintype "bidirectional"))
    )
    (net (code "372") (name "unconnected-(SLAVE_MOTOR-PadPRGRM)") (class "Default")
      (node (ref "SLAVE_MOTOR") (pin "PRGRM") (pinfunction "PRGRM_PRGRM") (pintype "bidirectional"))
    )
    (net (code "373") (name "unconnected-(SLAVE_MOTOR-PadRESET)") (class "Default")
      (node (ref "SLAVE_MOTOR") (pin "RESET") (pinfunction "RESET_RESET") (pintype "bidirectional"))
    )
    (net (code "374") (name "unconnected-(SLAVE_MOTOR-PadVBAT)") (class "Default")
      (node (ref "SLAVE_MOTOR") (pin "VBAT") (pinfunction "VBAT_VBAT") (pintype "bidirectional"))
    )
    (net (code "375") (name "unconnected-(SLAVE_MOTOR-PadVIN)") (class "Default")
      (node (ref "SLAVE_MOTOR") (pin "VIN") (pinfunction "VIN_VIN") (pintype "bidirectional"))
    )
    (net (code "376") (name "unconnected-(SLAVE_MOTOR-PadVUSB)") (class "Default")
      (node (ref "SLAVE_MOTOR") (pin "VUSB") (pinfunction "VUSB_VUSB") (pintype "bidirectional"))
    )
    (net (code "377") (name "unconnected-(SLAVE_SENSOR-13{slash}SCK0-Pad13)") (class "Default")
      (node (ref "SLAVE_SENSOR") (pin "13") (pinfunction "13/SCK0_13") (pintype "bidirectional"))
    )
    (net (code "378") (name "unconnected-(SLAVE_SENSOR-54{slash}CS2-Pad54)") (class "Default")
      (node (ref "SLAVE_SENSOR") (pin "54") (pinfunction "54/CS2_54") (pintype "bidirectional"))
    )
    (net (code "379") (name "unconnected-(SLAVE_SENSOR-A21{slash}DAC0-PadDA0)") (class "Default")
      (node (ref "SLAVE_SENSOR") (pin "DA0") (pinfunction "A21/DAC0_DA0") (pintype "bidirectional"))
    )
    (net (code "380") (name "unconnected-(SLAVE_SENSOR-DEBUG-1-PadDD)") (class "Default")
      (node (ref "SLAVE_SENSOR") (pin "DD") (pinfunction "DEBUG-1_DD") (pintype "bidirectional"))
    )
    (net (code "381") (name "unconnected-(SLAVE_SENSOR-DEBUG-2-PadDE)") (class "Default")
      (node (ref "SLAVE_SENSOR") (pin "DE") (pinfunction "DEBUG-2_DE") (pintype "bidirectional"))
    )
    (net (code "382") (name "unconnected-(SLAVE_SENSOR-DEBUG-PadDC)") (class "Default")
      (node (ref "SLAVE_SENSOR") (pin "DC") (pinfunction "DEBUG_DC") (pintype "bidirectional"))
    )
    (net (code "383") (name "unconnected-(SLAVE_SENSOR-Pad3.3V)") (class "Default")
      (node (ref "SLAVE_SENSOR") (pin "3.3V") (pinfunction "3.3V_3.3V") (pintype "bidirectional"))
    )
    (net (code "384") (name "unconnected-(SLAVE_SENSOR-Pad3.3V-2)") (class "Default")
      (node (ref "SLAVE_SENSOR") (pin "3.3V-2") (pinfunction "3.3V-2_3.3V-2") (pintype "bidirectional"))
    )
    (net (code "385") (name "unconnected-(SLAVE_SENSOR-Pad3.3V-3)") (class "Default")
      (node (ref "SLAVE_SENSOR") (pin "3.3V-3") (pinfunction "3.3V-3_3.3V-3") (pintype "bidirectional"))
    )
    (net (code "386") (name "unconnected-(SLAVE_SENSOR-Pad40)") (class "Default")
      (node (ref "SLAVE_SENSOR") (pin "40") (pinfunction "40_40") (pintype "bidirectional"))
    )
    (net (code "387") (name "unconnected-(SLAVE_SENSOR-Pad41)") (class "Default")
      (node (ref "SLAVE_SENSOR") (pin "41") (pinfunction "41_41") (pintype "bidirectional"))
    )
    (net (code "388") (name "unconnected-(SLAVE_SENSOR-Pad42)") (class "Default")
      (node (ref "SLAVE_SENSOR") (pin "42") (pinfunction "42_42") (pintype "bidirectional"))
    )
    (net (code "389") (name "unconnected-(SLAVE_SENSOR-Pad51)") (class "Default")
      (node (ref "SLAVE_SENSOR") (pin "51") (pinfunction "51_51") (pintype "bidirectional"))
    )
    (net (code "390") (name "unconnected-(SLAVE_SENSOR-Pad52)") (class "Default")
      (node (ref "SLAVE_SENSOR") (pin "52") (pinfunction "52_52") (pintype "bidirectional"))
    )
    (net (code "391") (name "unconnected-(SLAVE_SENSOR-Pad53)") (class "Default")
      (node (ref "SLAVE_SENSOR") (pin "53") (pinfunction "53_53") (pintype "bidirectional"))
    )
    (net (code "392") (name "unconnected-(SLAVE_SENSOR-Pad55)") (class "Default")
      (node (ref "SLAVE_SENSOR") (pin "55") (pinfunction "55_55") (pintype "bidirectional"))
    )
    (net (code "393") (name "unconnected-(SLAVE_SENSOR-Pad56)") (class "Default")
      (node (ref "SLAVE_SENSOR") (pin "56") (pinfunction "56_56") (pintype "bidirectional"))
    )
    (net (code "394") (name "unconnected-(SLAVE_SENSOR-Pad57)") (class "Default")
      (node (ref "SLAVE_SENSOR") (pin "57") (pinfunction "57_57") (pintype "bidirectional"))
    )
    (net (code "395") (name "unconnected-(SLAVE_SENSOR-PadA10)") (class "Default")
      (node (ref "SLAVE_SENSOR") (pin "A10") (pinfunction "A10_A10") (pintype "bidirectional"))
    )
    (net (code "396") (name "unconnected-(SLAVE_SENSOR-PadA11)") (class "Default")
      (node (ref "SLAVE_SENSOR") (pin "A11") (pinfunction "A11_A11") (pintype "bidirectional"))
    )
    (net (code "397") (name "unconnected-(SLAVE_SENSOR-PadAREF)") (class "Default")
      (node (ref "SLAVE_SENSOR") (pin "AREF") (pinfunction "AREF_AREF") (pintype "bidirectional"))
    )
    (net (code "398") (name "unconnected-(SLAVE_SENSOR-PadPRGRM)") (class "Default")
      (node (ref "SLAVE_SENSOR") (pin "PRGRM") (pinfunction "PRGRM_PRGRM") (pintype "bidirectional"))
    )
    (net (code "399") (name "unconnected-(SLAVE_SENSOR-PadRESET)") (class "Default")
      (node (ref "SLAVE_SENSOR") (pin "RESET") (pinfunction "RESET_RESET") (pintype "bidirectional"))
    )
    (net (code "400") (name "unconnected-(SLAVE_SENSOR-PadVBAT)") (class "Default")
      (node (ref "SLAVE_SENSOR") (pin "VBAT") (pinfunction "VBAT_VBAT") (pintype "bidirectional"))
    )
    (net (code "401") (name "unconnected-(SLAVE_SENSOR-PadVIN)") (class "Default")
      (node (ref "SLAVE_SENSOR") (pin "VIN") (pinfunction "VIN_VIN") (pintype "bidirectional"))
    )
    (net (code "402") (name "unconnected-(SLAVE_SENSOR-PadVUSB)") (class "Default")
      (node (ref "SLAVE_SENSOR") (pin "VUSB") (pinfunction "VUSB_VUSB") (pintype "bidirectional"))
    )
    (net (code "403") (name "unconnected-(U$1-ADC{slash}DAC-Pad17)") (class "Default")
      (node (ref "U$1") (pin "17") (pinfunction "ADC/DAC_17") (pintype "bidirectional"))
    )
    (net (code "404") (name "unconnected-(U$1-BOOT-Pad23)") (class "Default")
      (node (ref "U$1") (pin "23") (pinfunction "BOOT_23") (pintype "bidirectional"))
    )
    (net (code "405") (name "unconnected-(U$1-MISO-Pad12)") (class "Default")
      (node (ref "U$1") (pin "12") (pinfunction "MISO_12") (pintype "bidirectional"))
    )
    (net (code "406") (name "unconnected-(U$1-MOSI-Pad11)") (class "Default")
      (node (ref "U$1") (pin "11") (pinfunction "MOSI_11") (pintype "bidirectional"))
    )
    (net (code "407") (name "unconnected-(U$1-PWM1-Pad26)") (class "Default")
      (node (ref "U$1") (pin "26") (pinfunction "PWM1_26") (pintype "bidirectional"))
    )
    (net (code "408") (name "unconnected-(U$1-PWM2-Pad25)") (class "Default")
      (node (ref "U$1") (pin "25") (pinfunction "PWM2_25") (pintype "bidirectional"))
    )
    (net (code "409") (name "unconnected-(U$1-RESET-Pad24)") (class "Default")
      (node (ref "U$1") (pin "24") (pinfunction "RESET_24") (pintype "bidirectional"))
    )
    (net (code "410") (name "unconnected-(U$1-SCLK-Pad13)") (class "Default")
      (node (ref "U$1") (pin "13") (pinfunction "SCLK_13") (pintype "bidirectional"))
    )
    (net (code "411") (name "unconnected-(U$1-SSEL-Pad14)") (class "Default")
      (node (ref "U$1") (pin "14") (pinfunction "SSEL_14") (pintype "bidirectional"))
    )
    (net (code "412") (name "unconnected-(U$1-SWC-Pad21)") (class "Default")
      (node (ref "U$1") (pin "21") (pinfunction "SWC_21") (pintype "bidirectional"))
    )
    (net (code "413") (name "unconnected-(U$1-SWD-Pad22)") (class "Default")
      (node (ref "U$1") (pin "22") (pinfunction "SWD_22") (pintype "bidirectional"))
    )
  )
)
